# Aqua_D_CTRL.net
KiCad netlist of a schematic drawn in EAGLE
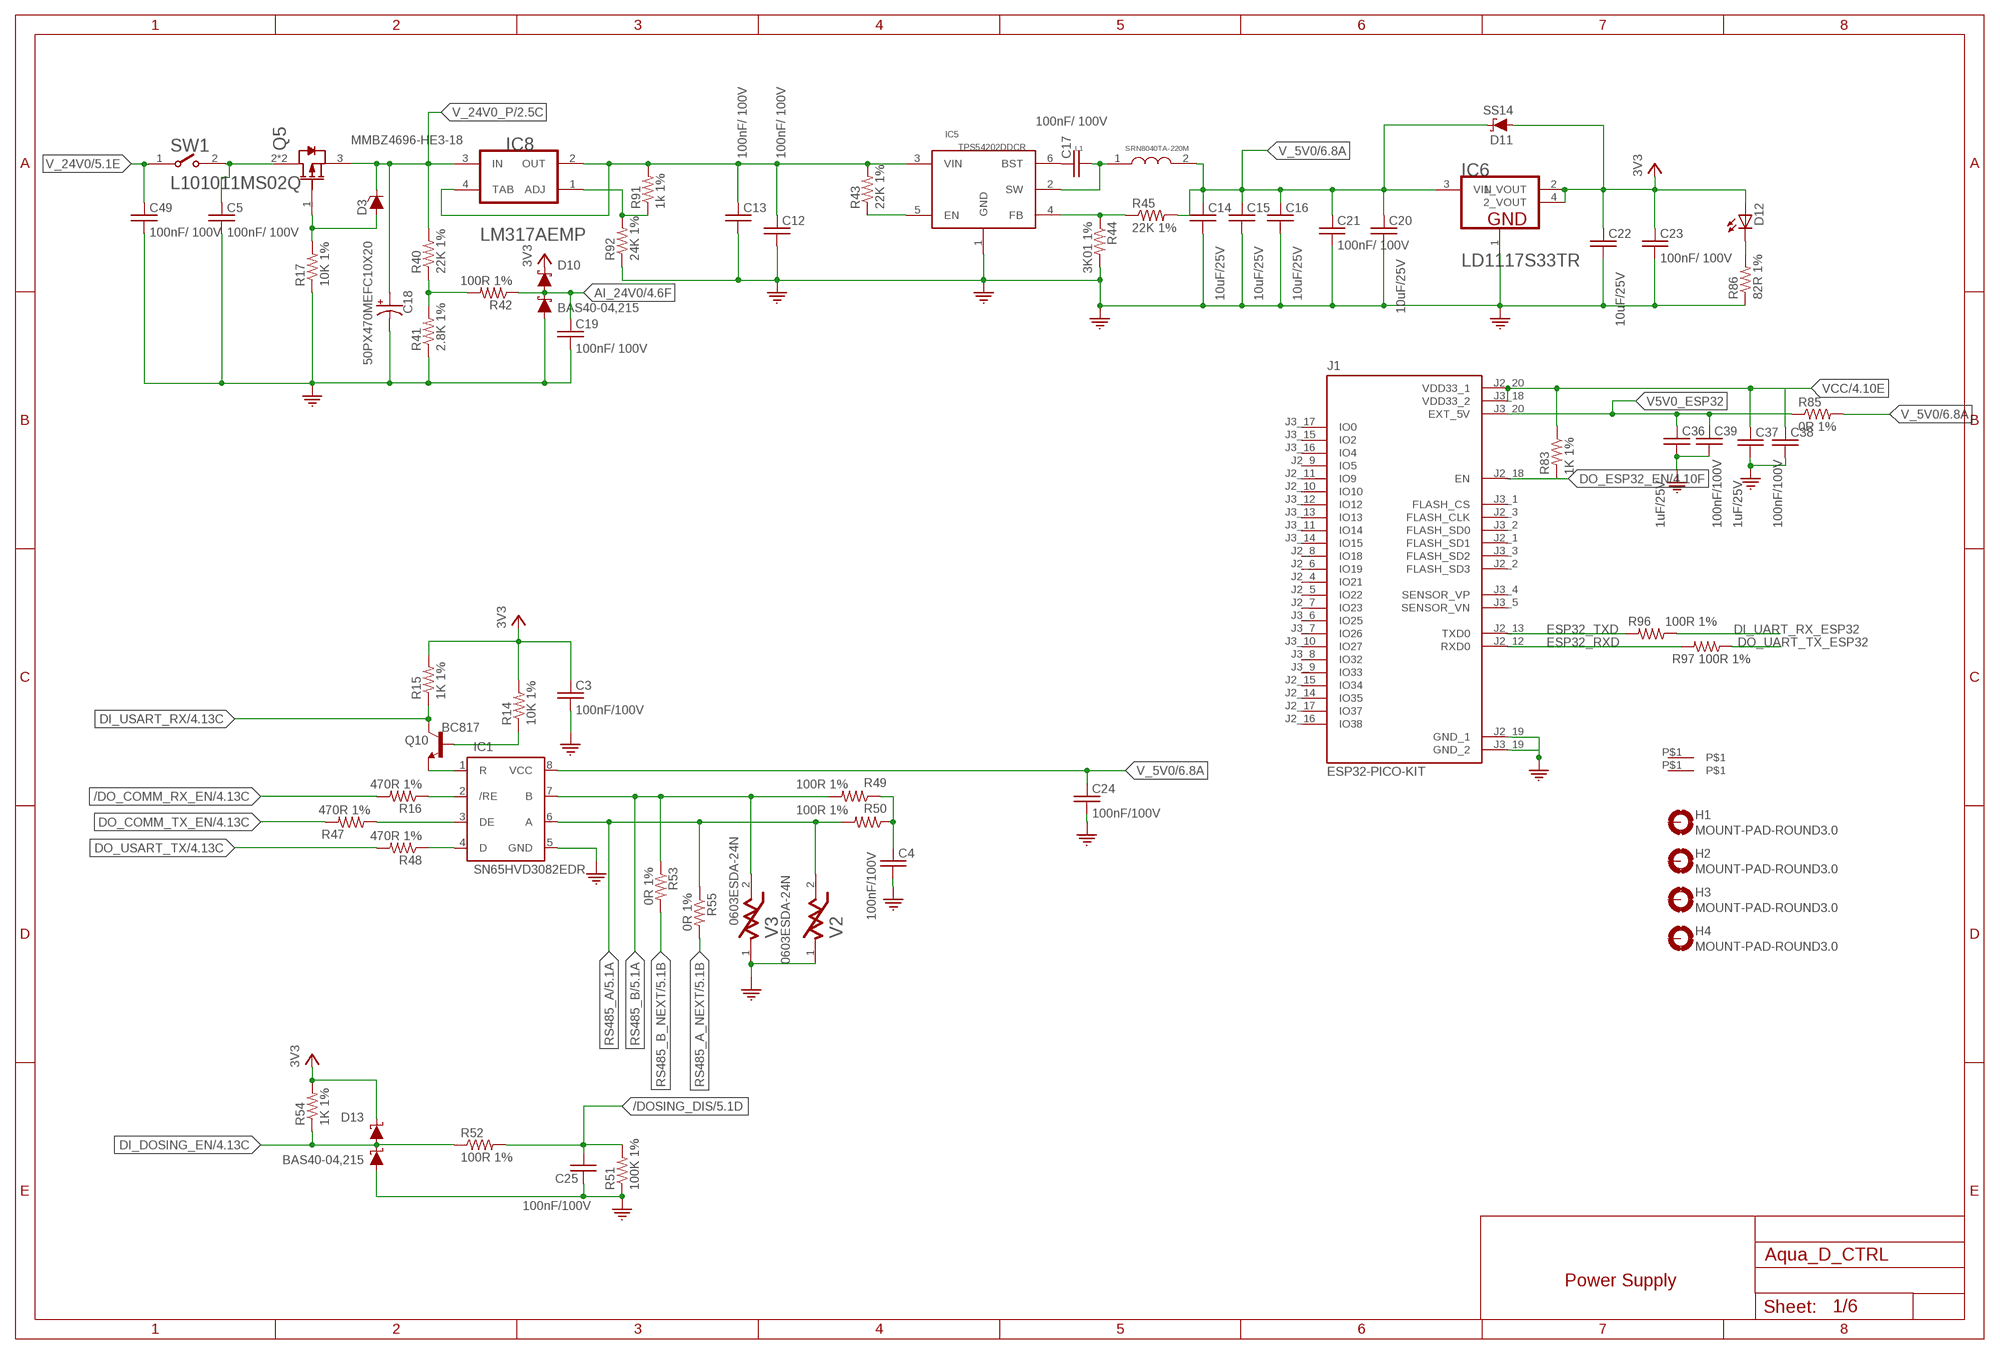
[diagram p0: schematic, sheet 1]
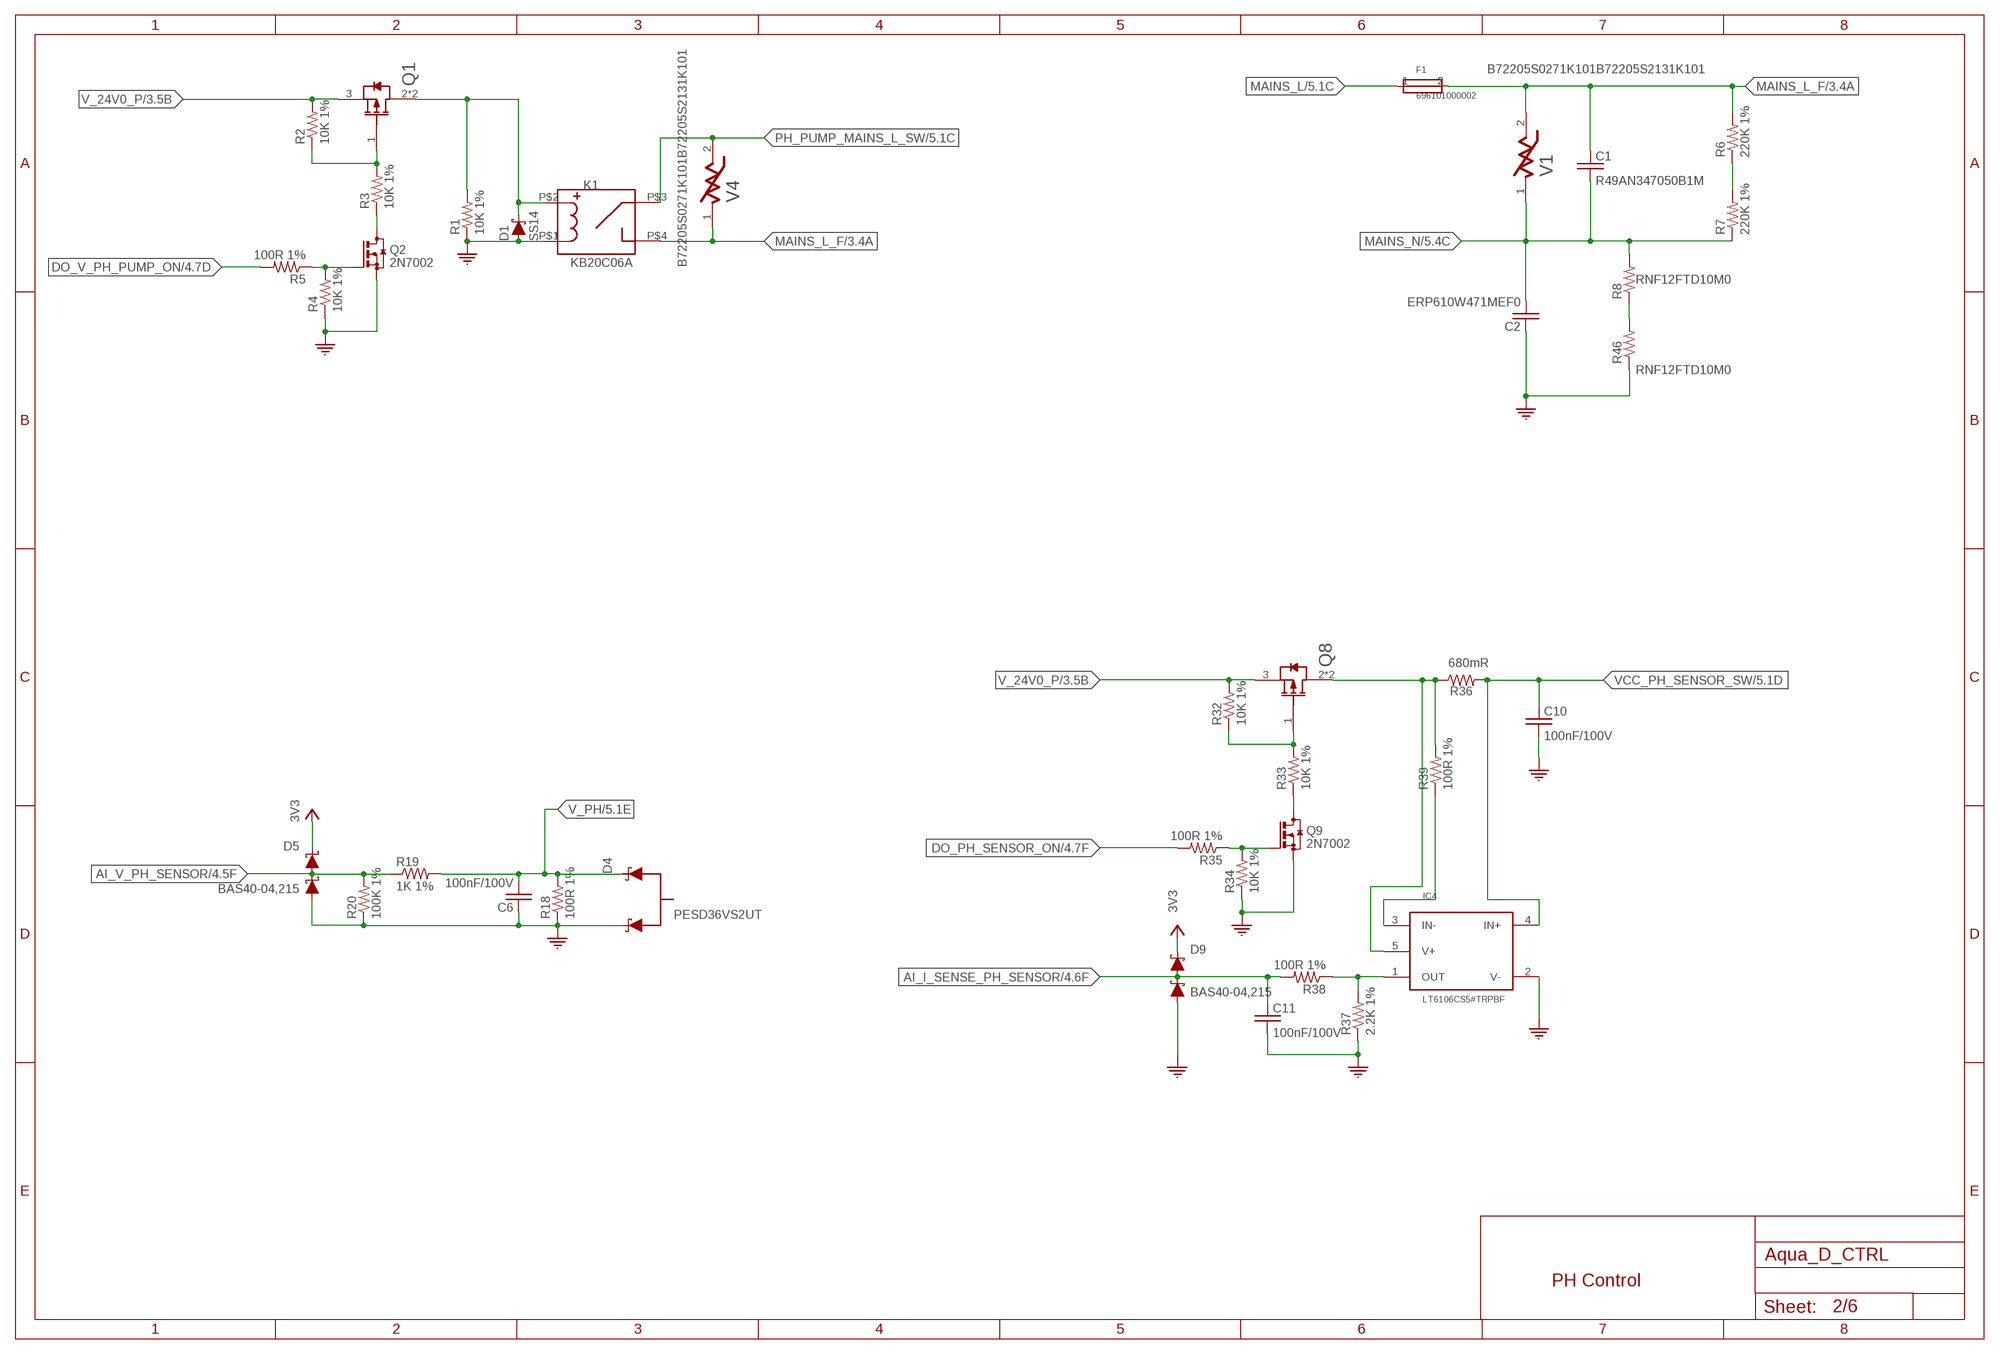
[diagram p1: schematic, sheet 2]
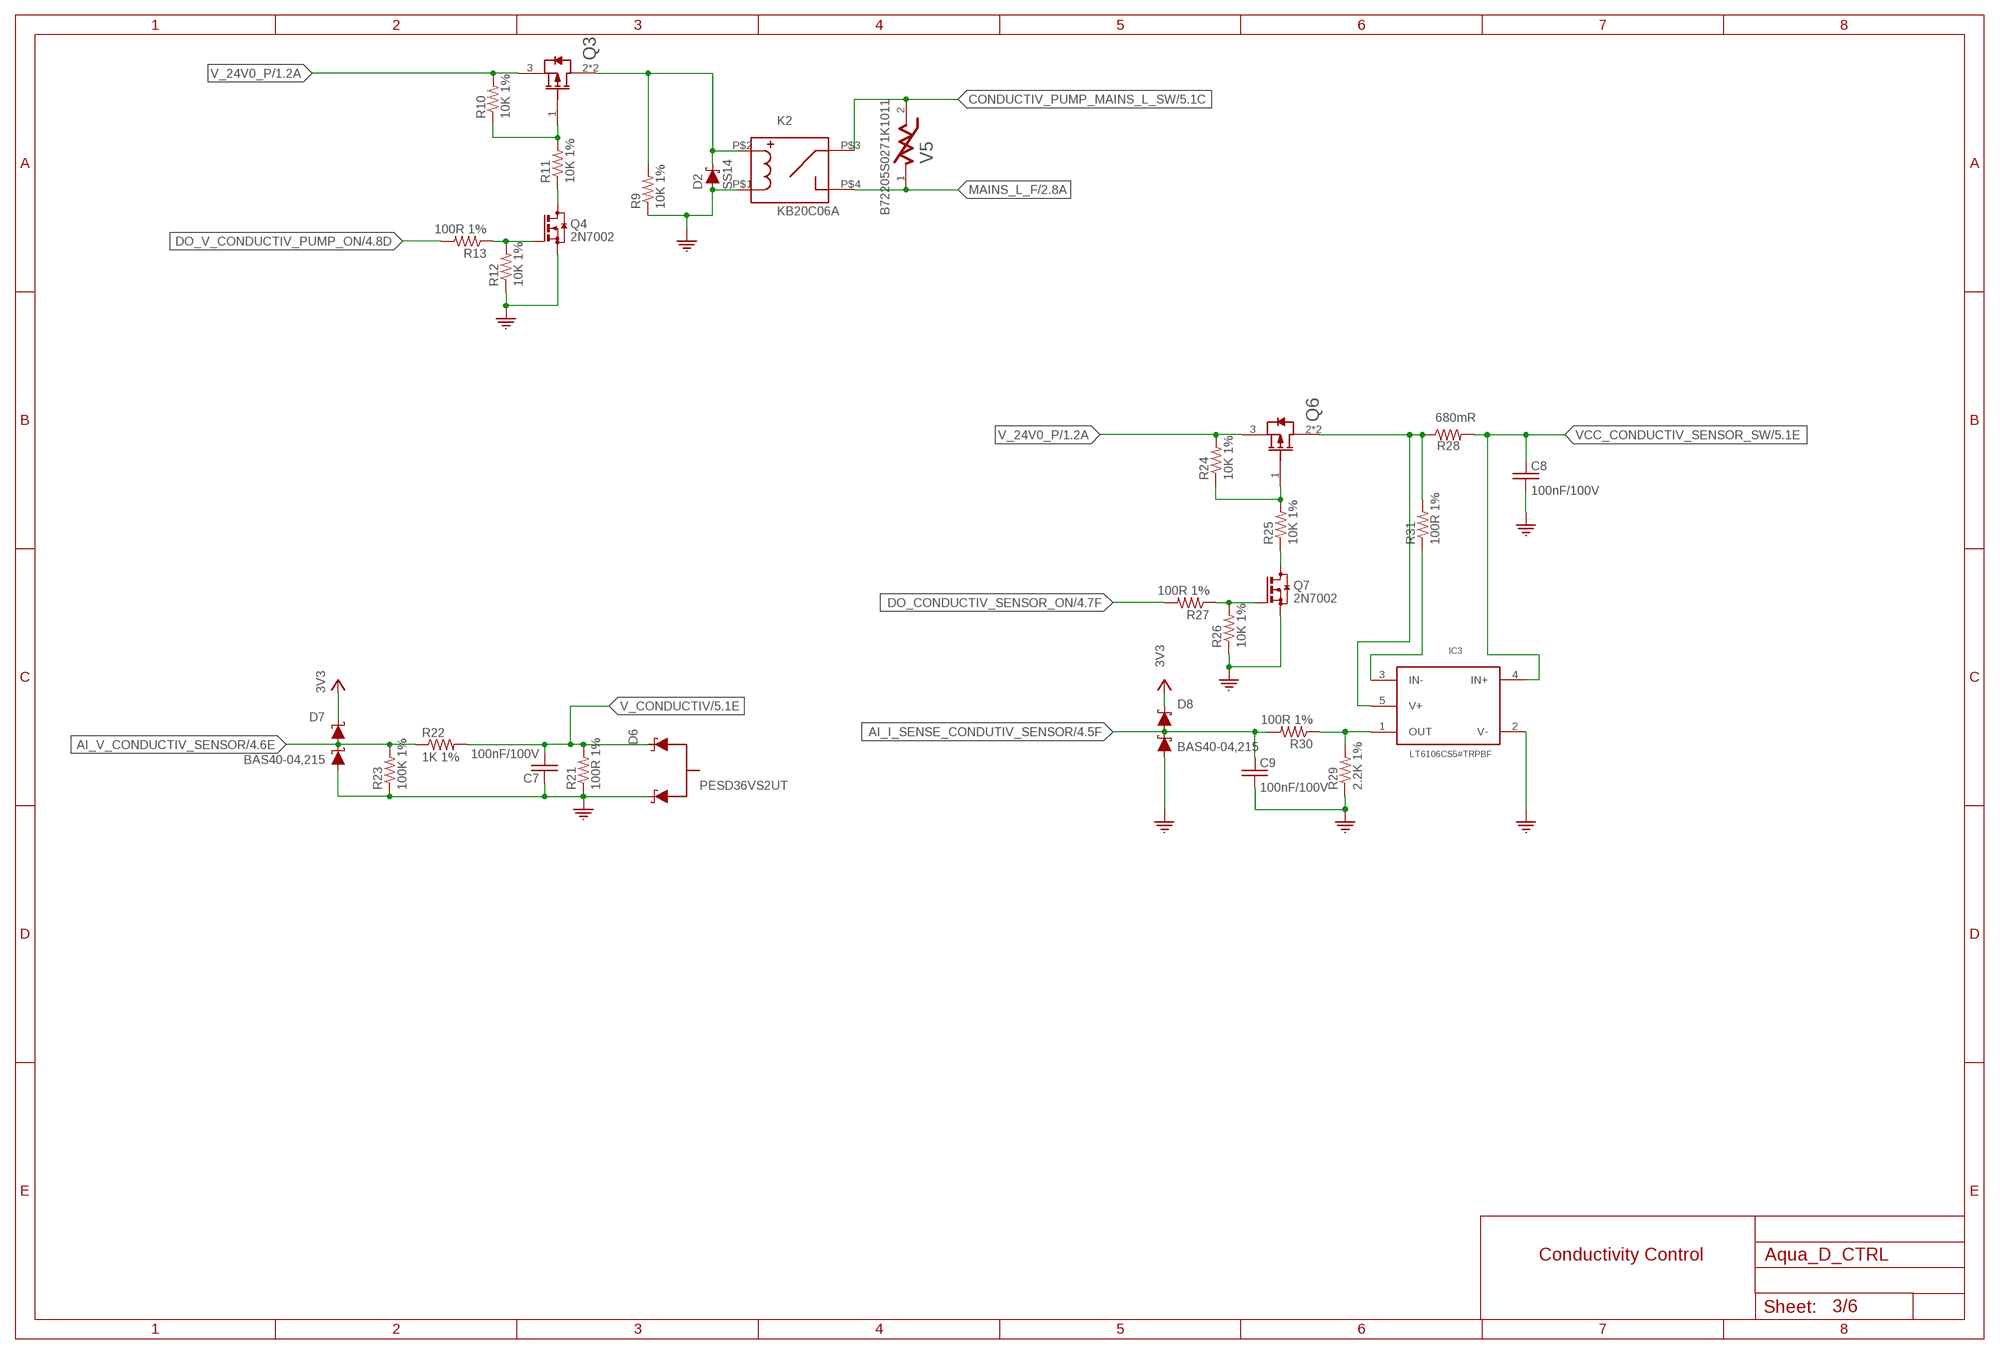
[diagram p2: schematic, sheet 3]
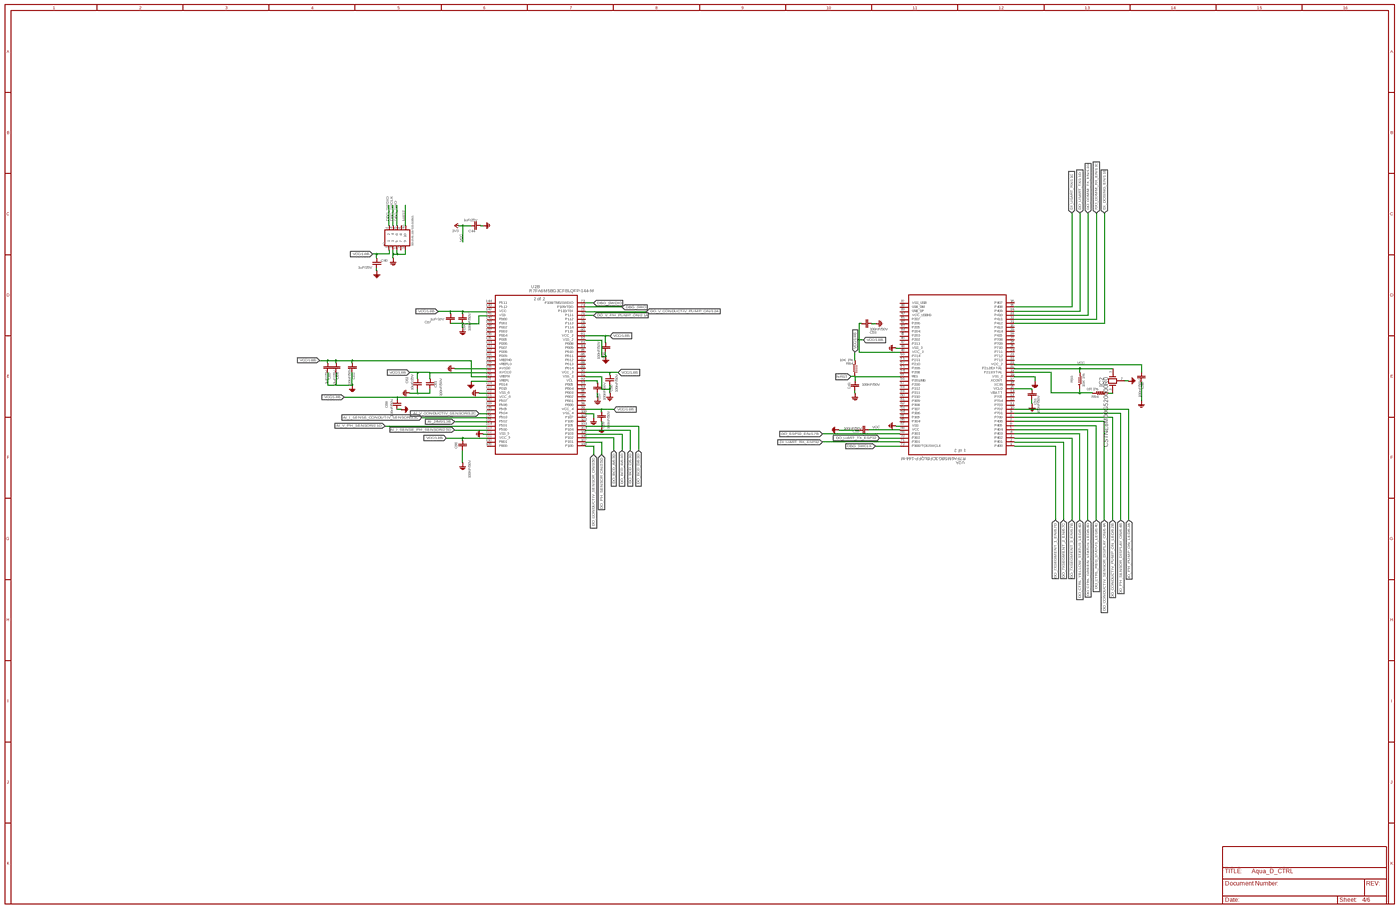
[diagram p3: schematic, sheet 4, overview]
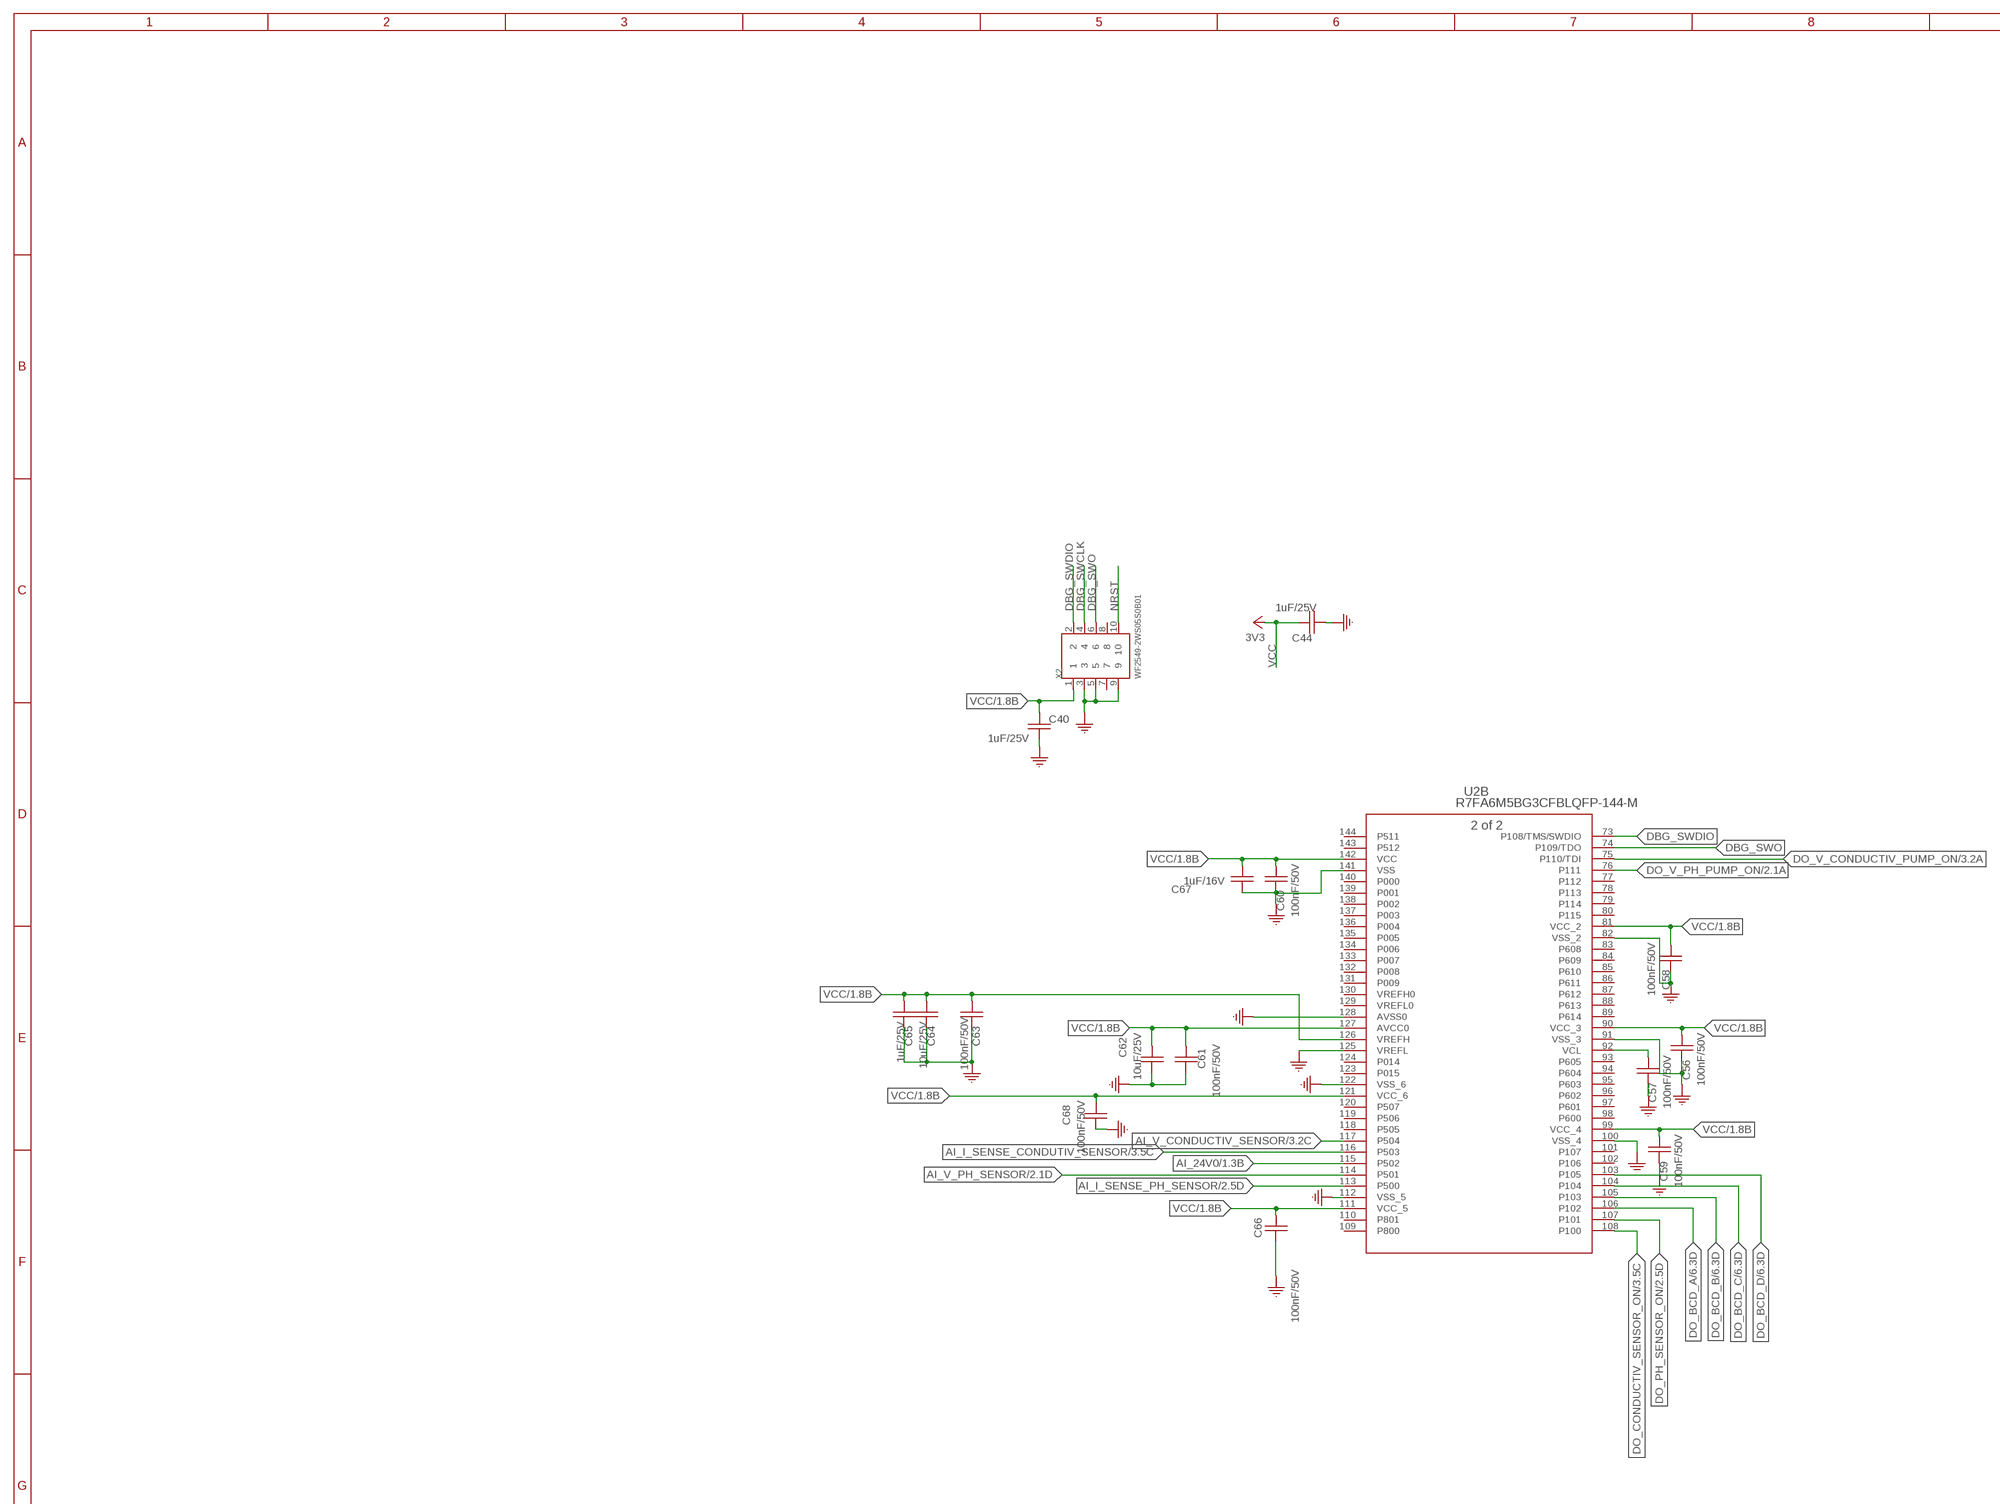
[diagram p4: schematic, sheet 4, part 1 of 4]
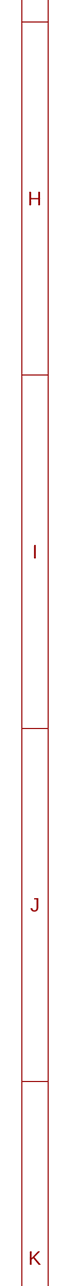
[diagram p5: schematic, sheet 4, part 2 of 4]
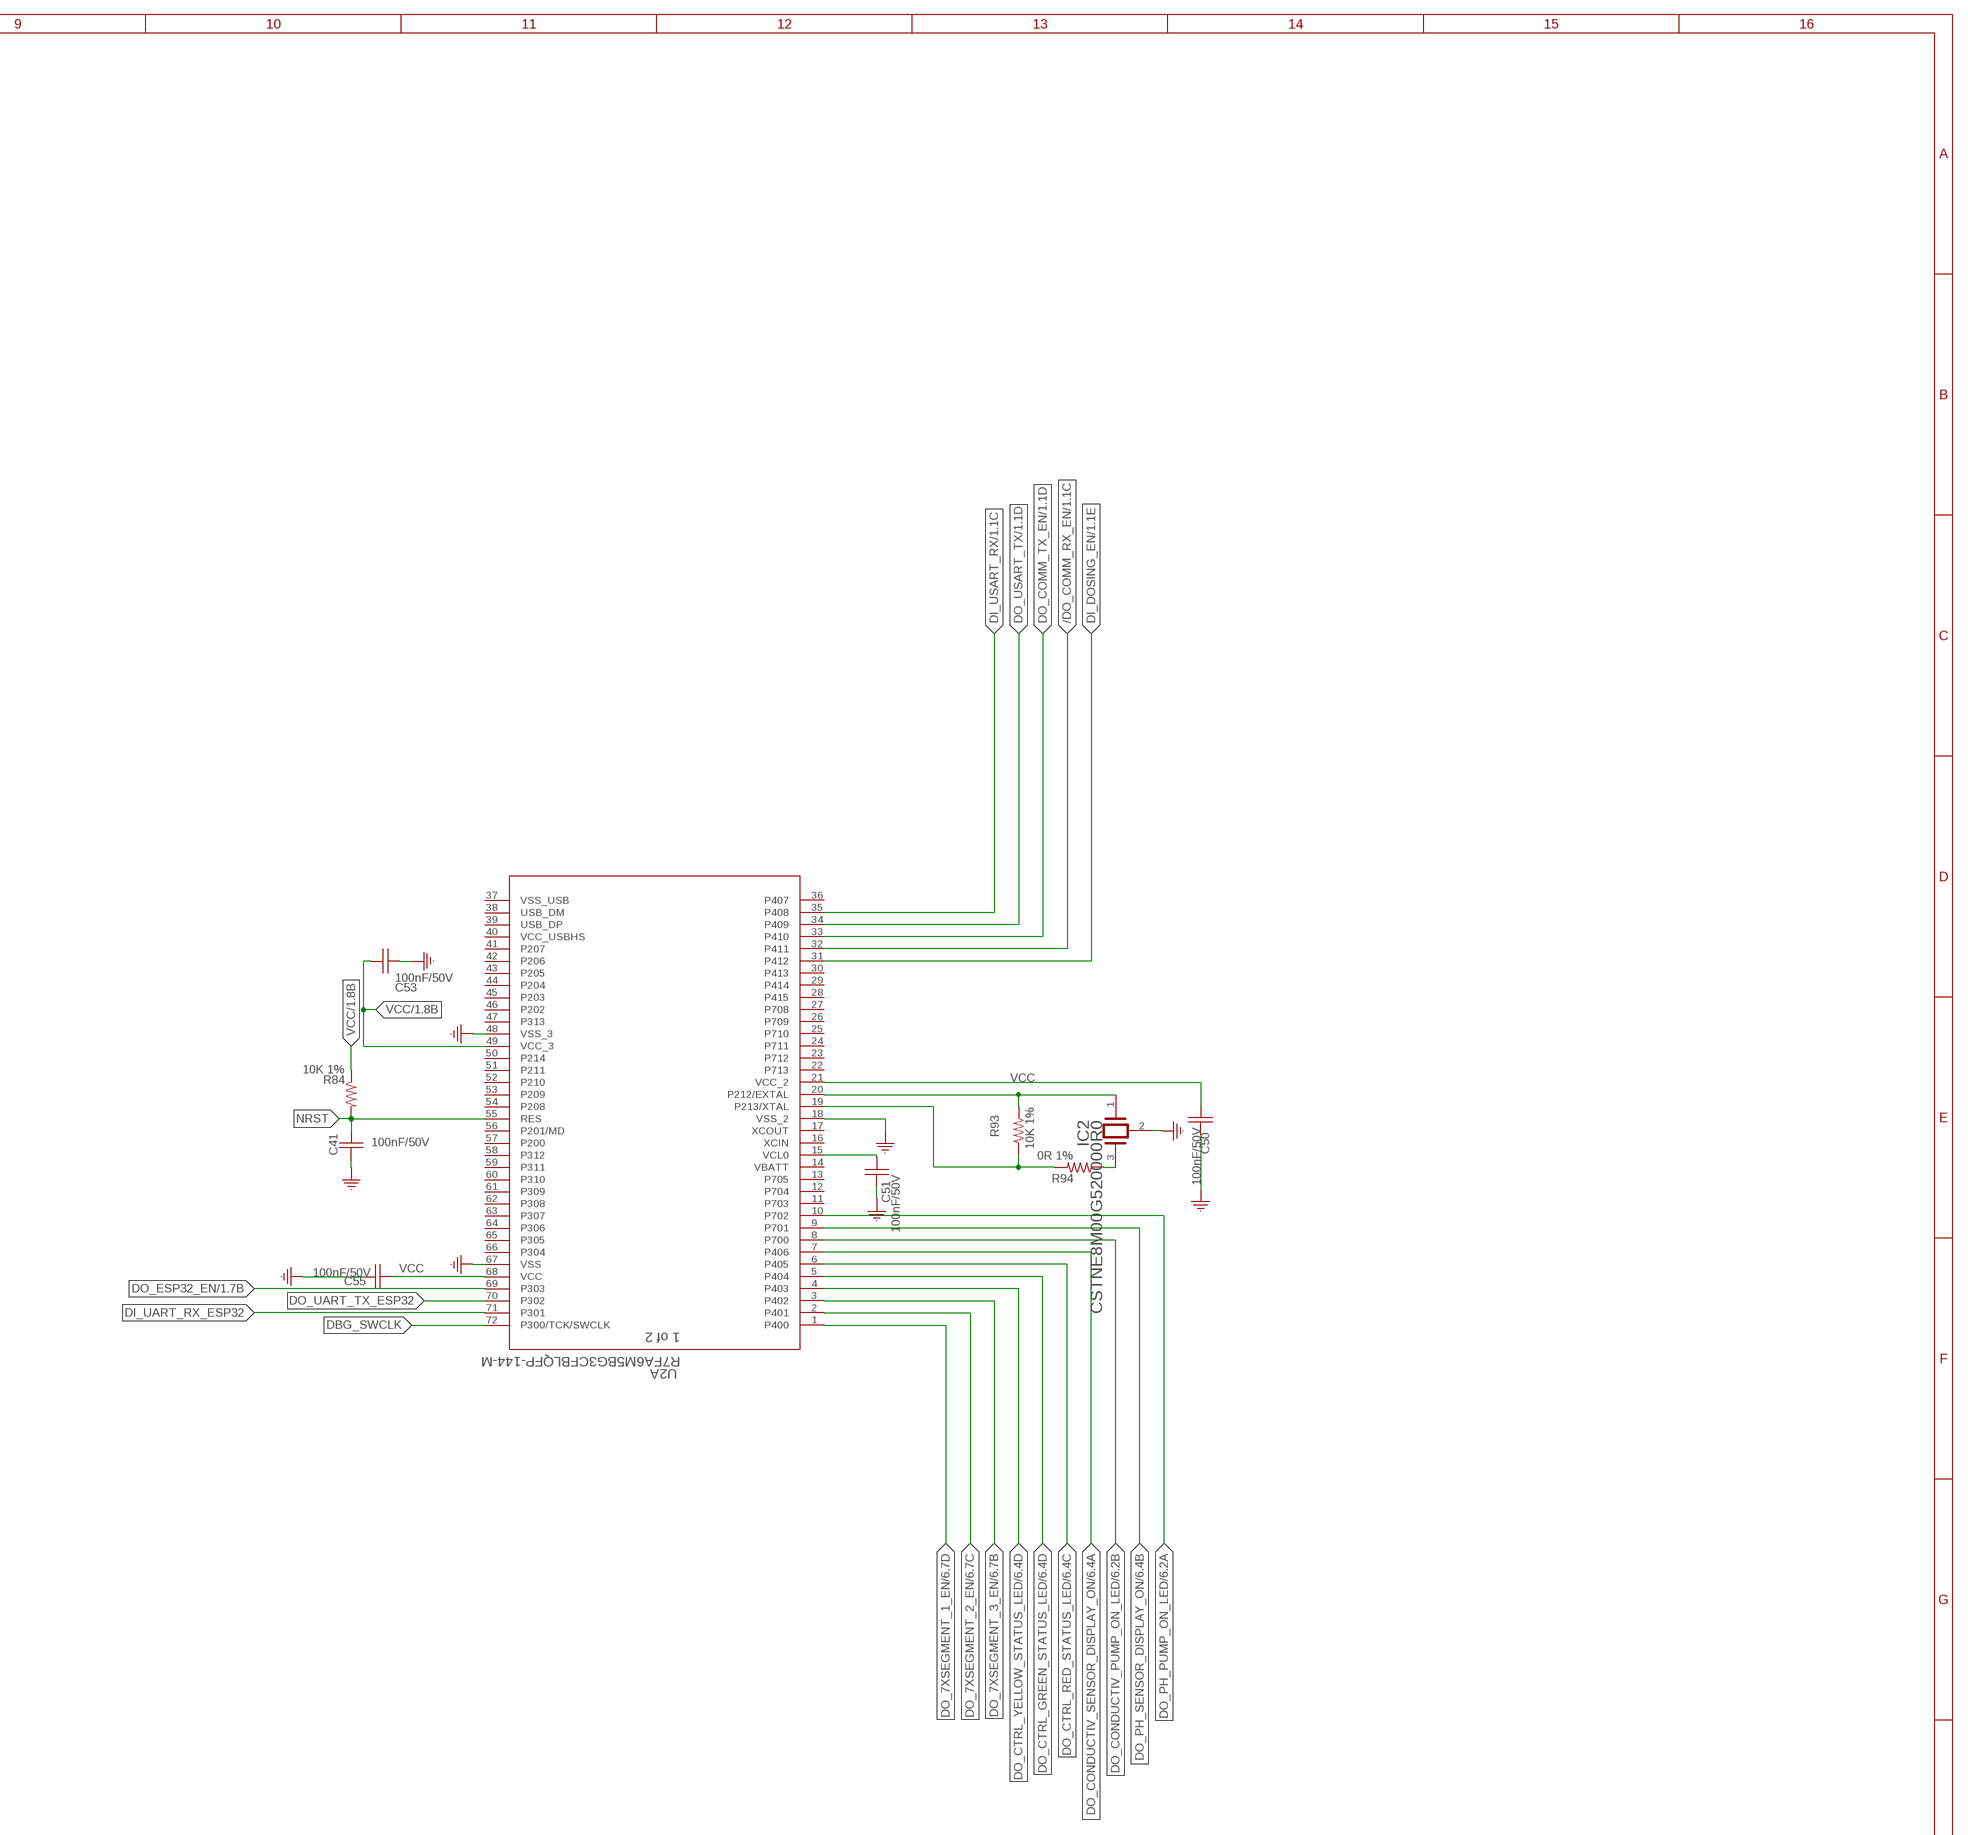
[diagram p6: schematic, sheet 4, part 3 of 4]
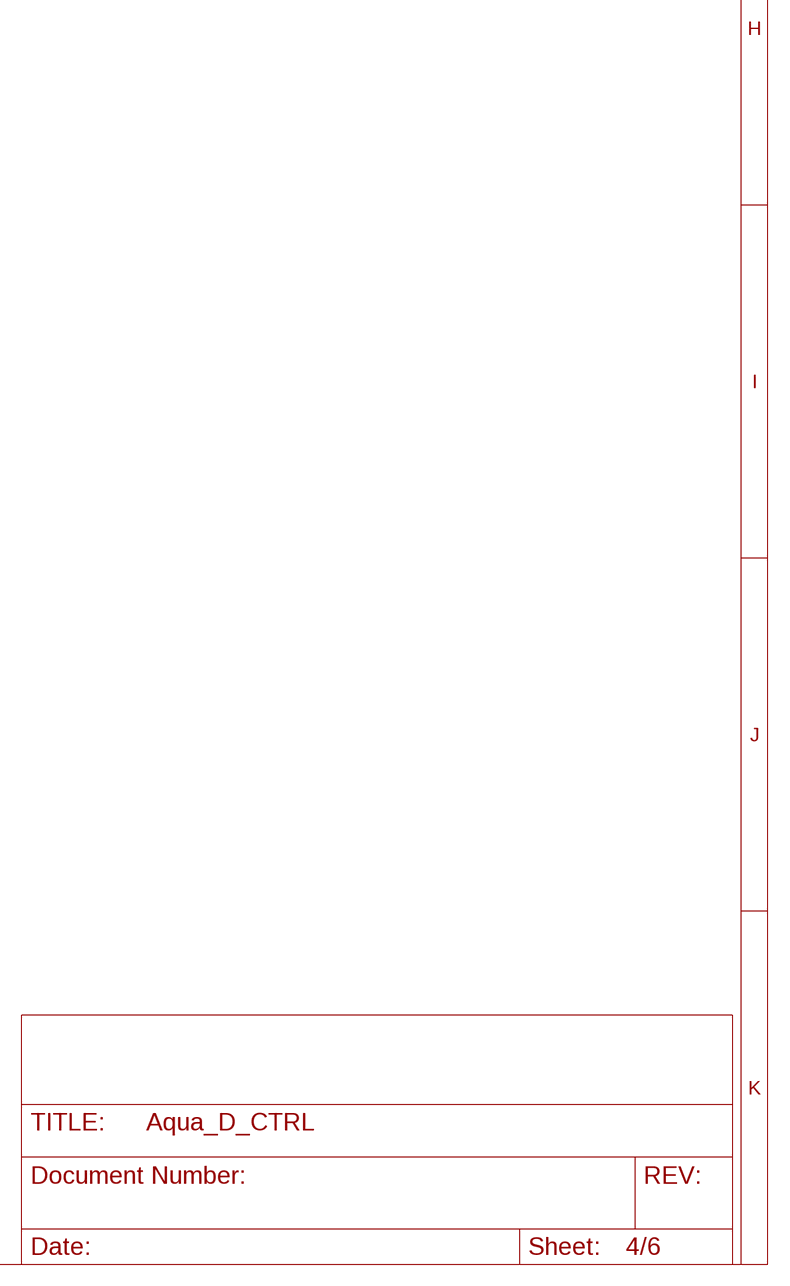
[diagram p7: schematic, sheet 4, part 4 of 4]
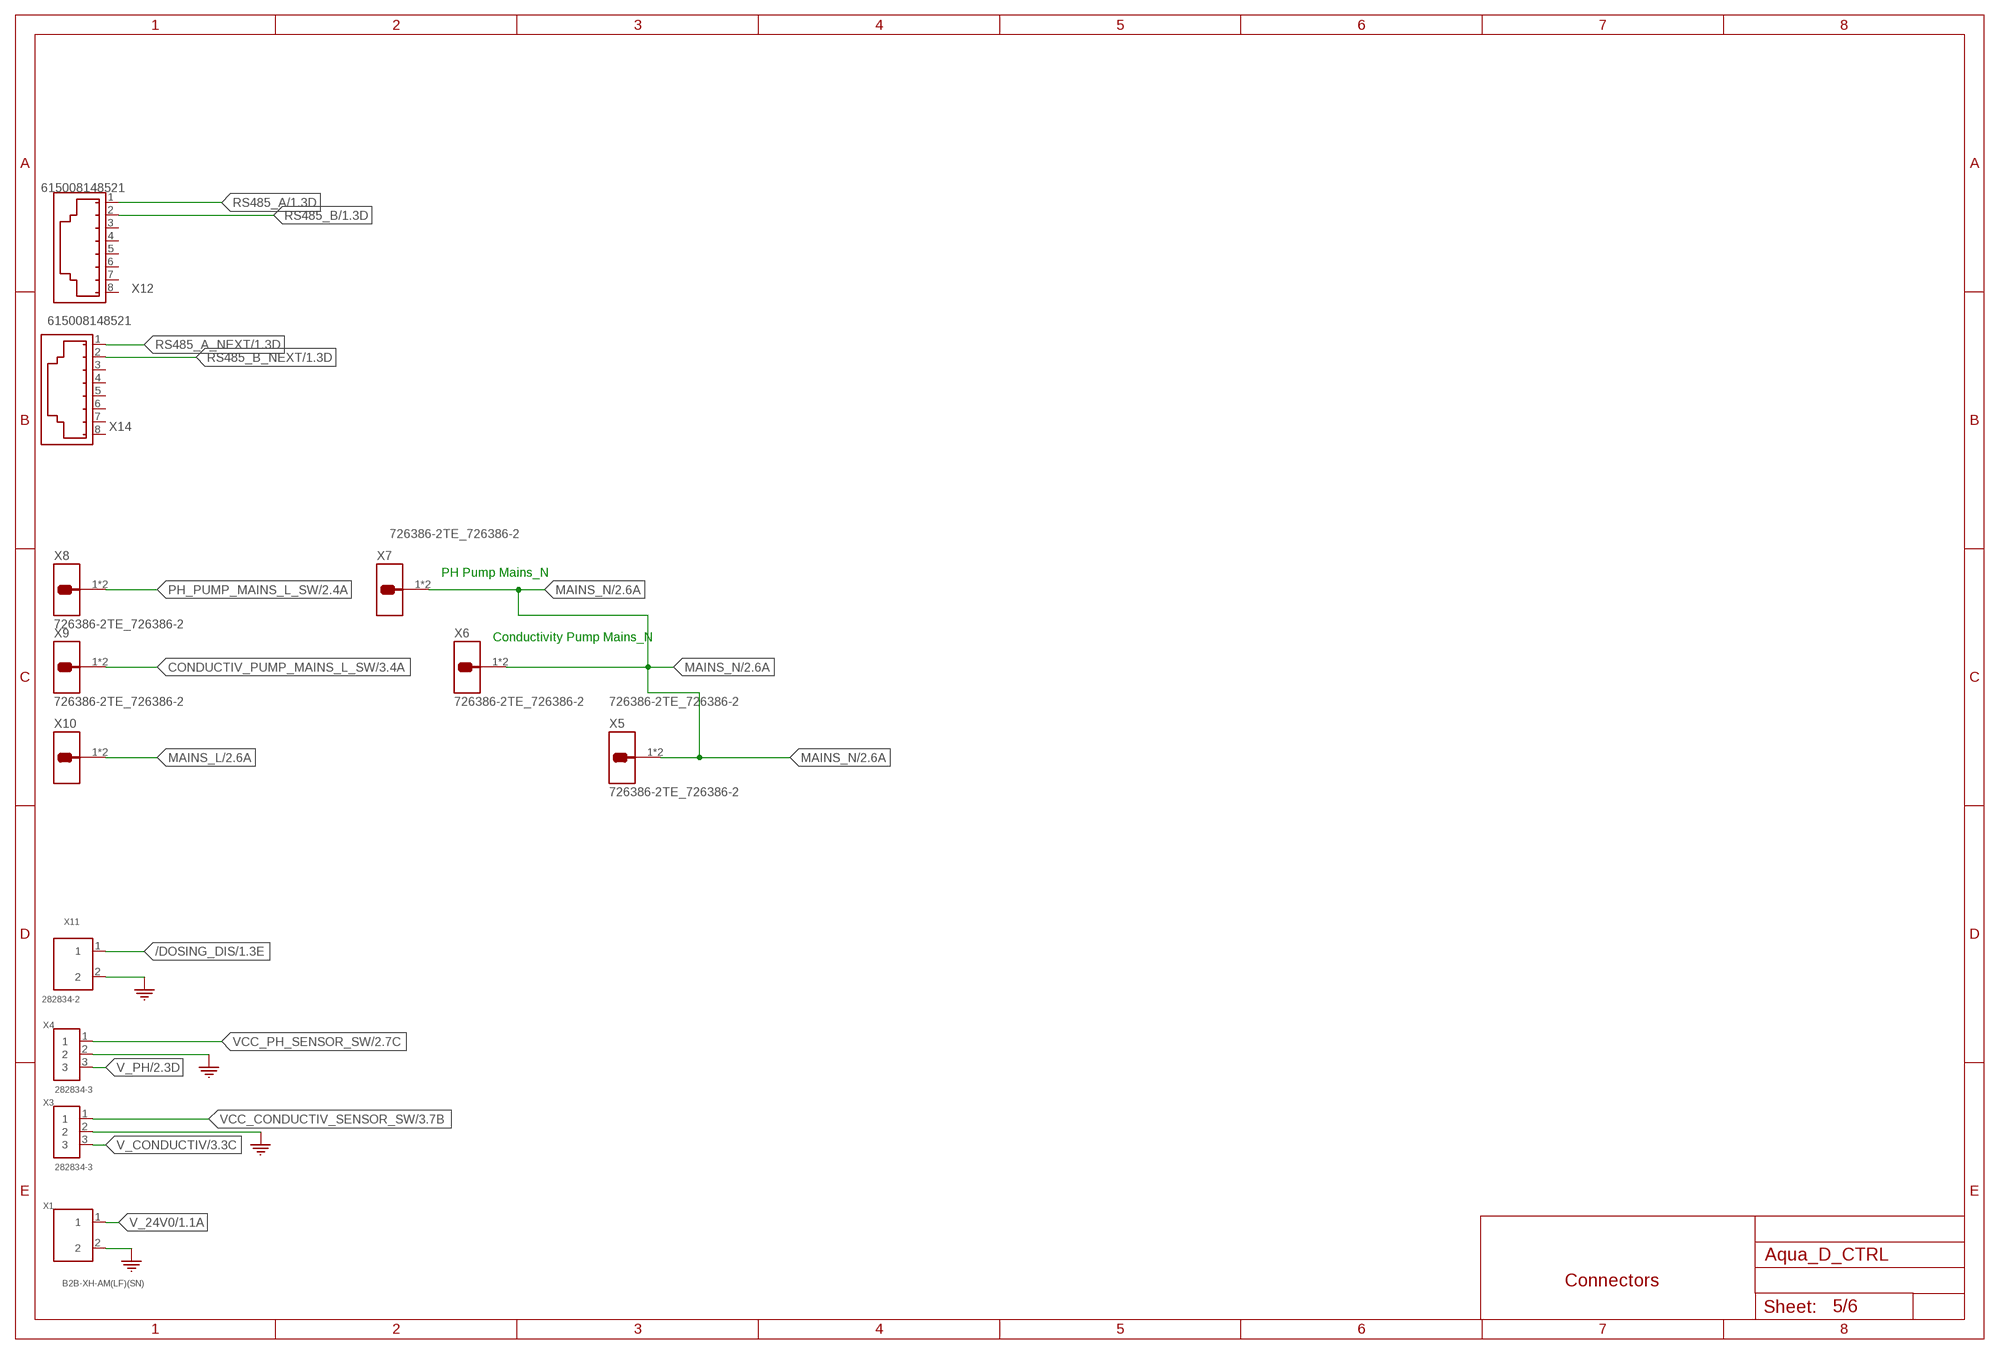
[diagram p8: schematic, sheet 5]
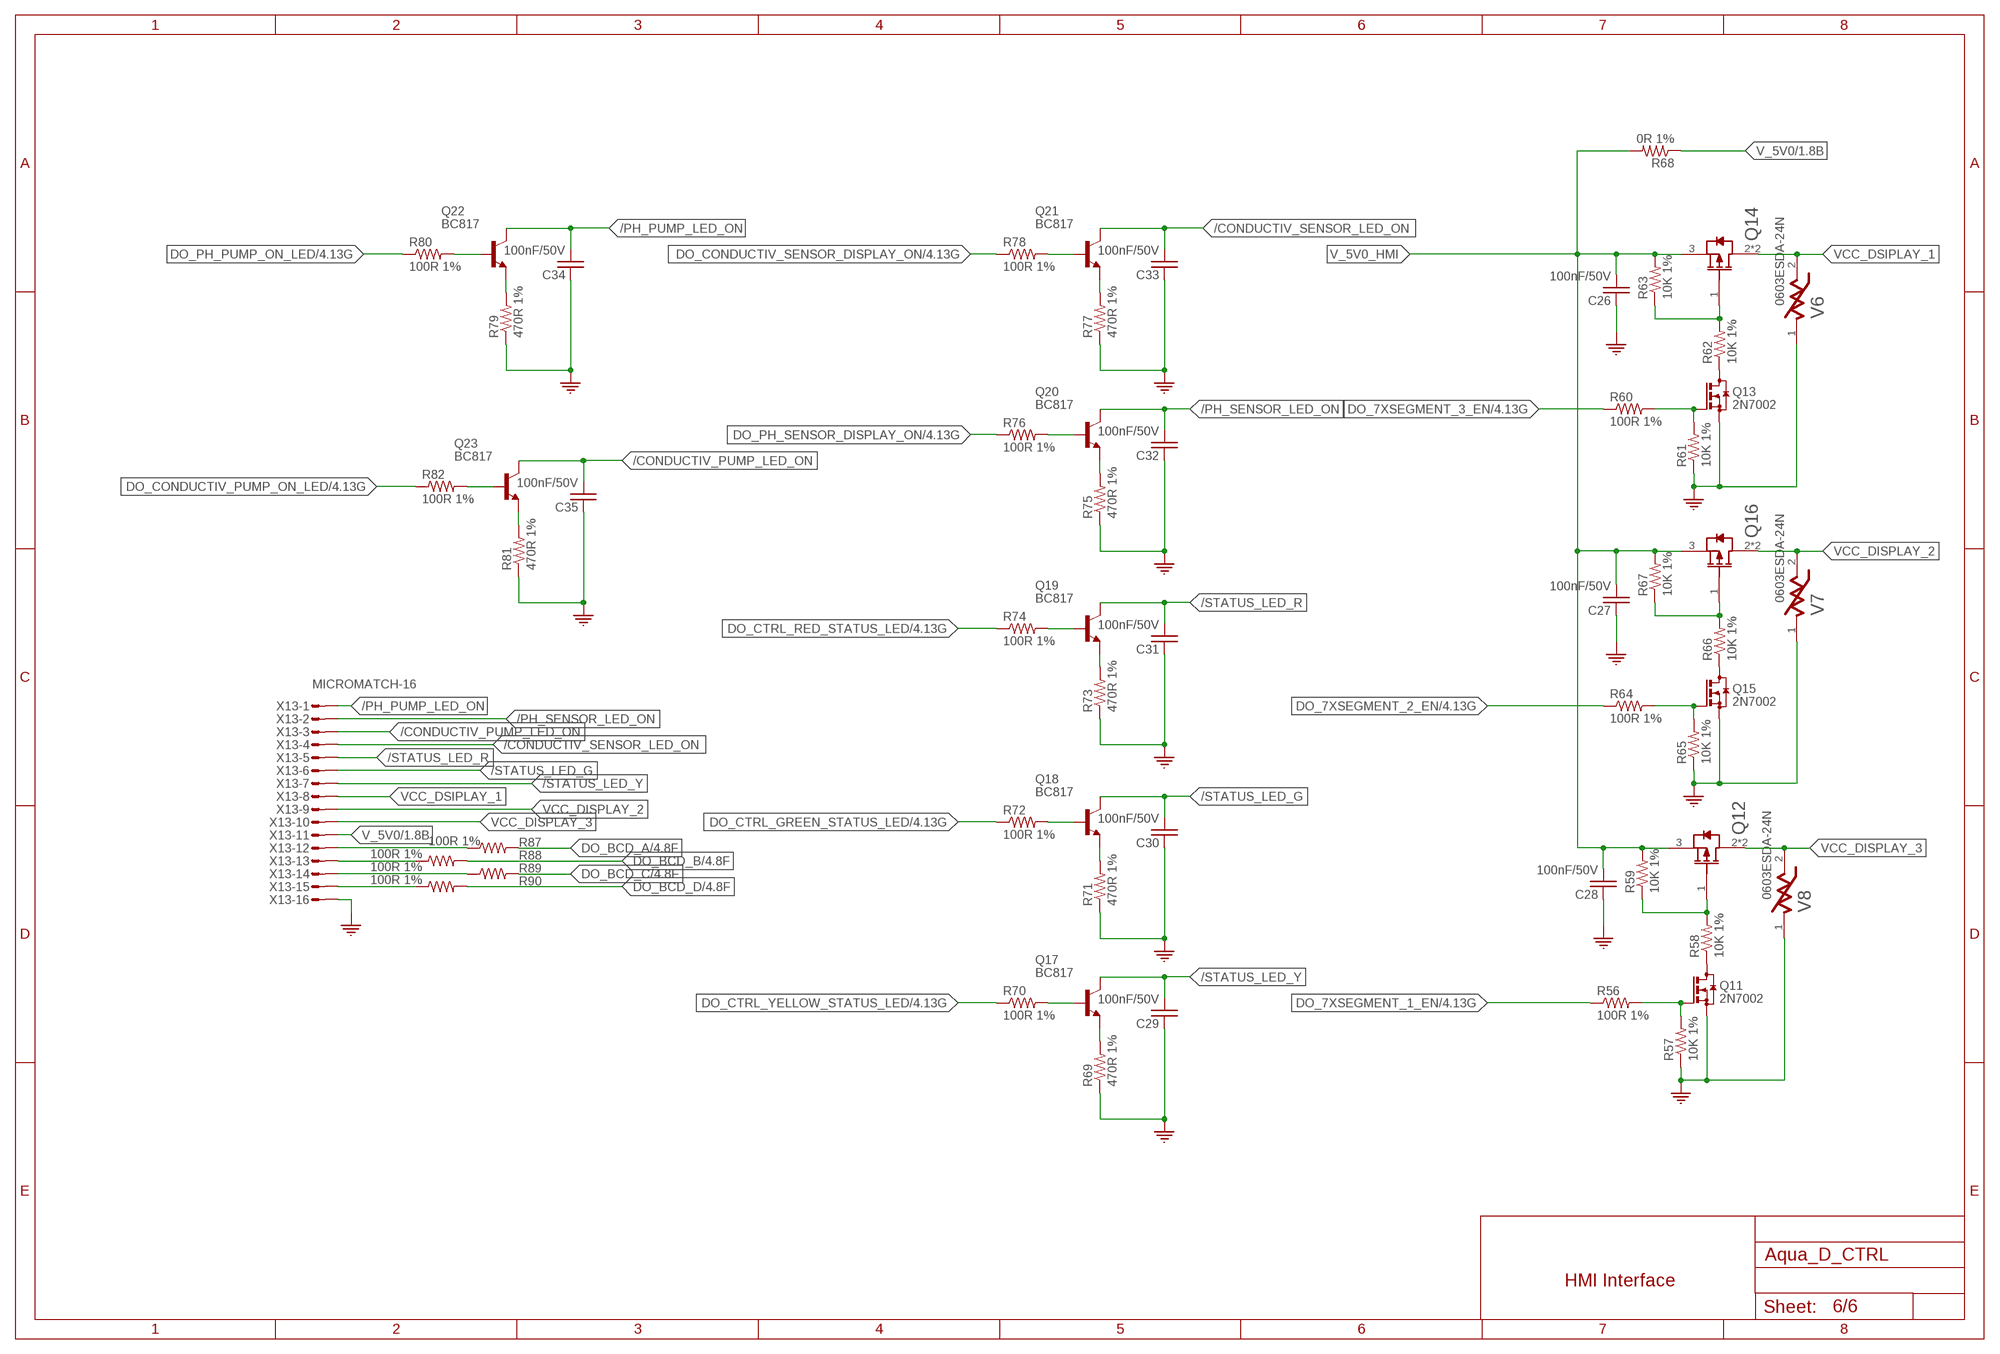
[diagram p9: schematic, sheet 6]

(export (version "E")
  (design (tool "Eeschema 10.0.6"))
  (components
    (comp (ref "C40")
      (value "1uF/25V")
      (footprint "eagle-import:0603")
      (libsource (lib "eagle-import") (part "C_0603"))
    )
    (comp (ref "C41")
      (value "100nF/50V")
      (footprint "eagle-import:0603")
      (libsource (lib "eagle-import") (part "C_0603"))
    )
    (comp (ref "C44")
      (value "1uF/25V")
      (footprint "eagle-import:0603")
      (libsource (lib "eagle-import") (part "C_0603"))
    )
    (comp (ref "C50")
      (value "100nF/50V")
      (footprint "eagle-import:0603")
      (libsource (lib "eagle-import") (part "C_0603"))
    )
    (comp (ref "C51")
      (value "100nF/50V")
      (footprint "eagle-import:0603")
      (libsource (lib "eagle-import") (part "C_0603"))
    )
    (comp (ref "C53")
      (value "100nF/50V")
      (footprint "eagle-import:0603")
      (libsource (lib "eagle-import") (part "C_0603"))
    )
    (comp (ref "C55")
      (value "100nF/50V")
      (footprint "eagle-import:0603")
      (libsource (lib "eagle-import") (part "C_0603"))
    )
    (comp (ref "C56")
      (value "100nF/50V")
      (footprint "eagle-import:0603")
      (libsource (lib "eagle-import") (part "C_0603"))
    )
    (comp (ref "C57")
      (value "100nF/50V")
      (footprint "eagle-import:0603")
      (libsource (lib "eagle-import") (part "C_0603"))
    )
    (comp (ref "C58")
      (value "100nF/50V")
      (footprint "eagle-import:0603")
      (libsource (lib "eagle-import") (part "C_0603"))
    )
    (comp (ref "C59")
      (value "100nF/50V")
      (footprint "eagle-import:0603")
      (libsource (lib "eagle-import") (part "C_0603"))
    )
    (comp (ref "C60")
      (value "100nF/50V")
      (footprint "eagle-import:0603")
      (libsource (lib "eagle-import") (part "C_0603"))
    )
    (comp (ref "C61")
      (value "100nF/50V")
      (footprint "eagle-import:0603")
      (libsource (lib "eagle-import") (part "C_0603"))
    )
    (comp (ref "C62")
      (value "10uF/25V")
      (footprint "eagle-import:0603")
      (libsource (lib "eagle-import") (part "C_0603"))
    )
    (comp (ref "C63")
      (value "100nF/50V")
      (footprint "eagle-import:0603")
      (libsource (lib "eagle-import") (part "C_0603"))
    )
    (comp (ref "C64")
      (value "10uF/25V")
      (footprint "eagle-import:0603")
      (libsource (lib "eagle-import") (part "C_0603"))
    )
    (comp (ref "C65")
      (value "1uF/25V")
      (footprint "eagle-import:0603")
      (libsource (lib "eagle-import") (part "C_0603"))
    )
    (comp (ref "C66")
      (value "100nF/50V")
      (footprint "eagle-import:0603")
      (libsource (lib "eagle-import") (part "C_0603"))
    )
    (comp (ref "C67")
      (value "1uF/16V")
      (footprint "eagle-import:0603")
      (libsource (lib "eagle-import") (part "C_0603"))
    )
    (comp (ref "C68")
      (value "100nF/50V")
      (footprint "eagle-import:0603")
      (libsource (lib "eagle-import") (part "C_0603"))
    )
    (comp (ref "IC2")
      (value "CSTNE8M00G520000R0")
      (footprint "eagle-import:CSTNE8M00G520000R0")
      (fields (field (name "MFR") "Murata"))
      (libsource (lib "eagle-import") (part "CSTNE8M00G520000R0"))
    )
    (comp (ref "R84")
      (value "10K 1%")
      (footprint "eagle-import:R0603")
      (libsource (lib "eagle-import") (part "Labops_Lib_AH_R_0603"))
    )
    (comp (ref "R93")
      (value "10K 1%")
      (footprint "eagle-import:R0603")
      (libsource (lib "eagle-import") (part "Labops_Lib_AH_R_0603"))
    )
    (comp (ref "R94")
      (value "0R 1%")
      (footprint "eagle-import:R0603")
      (libsource (lib "eagle-import") (part "Labops_Lib_AH_R_0603"))
    )
    (comp (ref "U2")
      (value "R7FA6M5BG3CFBLQFP-144-M")
      (footprint "eagle-import:LQFP-144-M")
      (fields (field (name "MFR") "Renesas"))
      (libsource (lib "eagle-import") (part "R7FA6M5BG3CFBLQFP-144-M"))
    )
    (comp (ref "X2")
      (value "WF2549-2WS05S0B01")
      (footprint "eagle-import:X10_100MIL_2XROW_VERT")
      (fields (field (name "MFR") "WCON"))
      (libsource (lib "eagle-import") (part "WF2549-2WS05S0B01"))
    )
    (comp (ref "C7")
      (value "100nF/100V")
      (footprint "eagle-import:0603")
      (libsource (lib "eagle-import") (part "C_0603"))
    )
    (comp (ref "C8")
      (value "100nF/100V")
      (footprint "eagle-import:0603")
      (fields (field (name "PART_VALUE") "100nF/100V"))
      (libsource (lib "eagle-import") (part "C_0603"))
    )
    (comp (ref "C9")
      (value "100nF/100V")
      (footprint "eagle-import:0603")
      (fields (field (name "PART_VALUE") "100nF/100V"))
      (libsource (lib "eagle-import") (part "C_0603"))
    )
    (comp (ref "D2")
      (value "SS14")
      (footprint "eagle-import:SMA")
      (fields (field (name "MFR") "MCC"))
      (libsource (lib "eagle-import") (part "SS14"))
    )
    (comp (ref "D6")
      (value "PESD36VS2UT")
      (footprint "eagle-import:SOT23-3")
      (fields (field (name "MFR") "NXP"))
      (libsource (lib "eagle-import") (part "PESD36VS2UT"))
    )
    (comp (ref "D7")
      (value "BAS40-04,215")
      (footprint "eagle-import:SOT23-3")
      (fields (field (name "MFR") "NXP"))
      (libsource (lib "eagle-import") (part "BAS40-04,215"))
    )
    (comp (ref "D8")
      (value "BAS40-04,215")
      (footprint "eagle-import:SOT23-3")
      (fields (field (name "MFR") "NXP"))
      (libsource (lib "eagle-import") (part "BAS40-04,215"))
    )
    (comp (ref "IC3")
      (value "LT6106CS5#TRPBF")
      (footprint "eagle-import:SOT-23-5")
      (fields (field (name "MFR") "Analog Devices"))
      (libsource (lib "eagle-import") (part "LT6106CS5#TRPBF"))
    )
    (comp (ref "K2")
      (value "KB20C06A")
      (footprint "eagle-import:RELAY_KYOTO_KF0604D")
      (fields (field (name "MFR") "Kyotto"))
      (libsource (lib "eagle-import") (part "KB20C06A"))
    )
    (comp (ref "Q3")
      (value "DMP6185SEQ-13")
      (footprint "eagle-import:SOT223")
      (fields (field (name "MFR") "Diodes"))
      (libsource (lib "eagle-import") (part "DMP6185SEQ-13"))
    )
    (comp (ref "Q4")
      (value "2N7002")
      (footprint "eagle-import:SOT23")
      (fields (field (name "MFR") "Diodes, Guangdong Hotetech,NXP"))
      (libsource (lib "eagle-import") (part "2N7002"))
    )
    (comp (ref "Q6")
      (value "DMP6185SEQ-13")
      (footprint "eagle-import:SOT223")
      (fields (field (name "MFR") "Diodes"))
      (libsource (lib "eagle-import") (part "DMP6185SEQ-13"))
    )
    (comp (ref "Q7")
      (value "2N7002")
      (footprint "eagle-import:SOT23")
      (fields (field (name "MFR") "Diodes, Guangdong Hotetech,NXP"))
      (libsource (lib "eagle-import") (part "2N7002"))
    )
    (comp (ref "R9")
      (value "10K 1%")
      (footprint "eagle-import:0603")
      (libsource (lib "eagle-import") (part "R_0603"))
    )
    (comp (ref "R10")
      (value "10K 1%")
      (footprint "eagle-import:0603")
      (libsource (lib "eagle-import") (part "R_0603"))
    )
    (comp (ref "R11")
      (value "10K 1%")
      (footprint "eagle-import:0603")
      (libsource (lib "eagle-import") (part "R_0603"))
    )
    (comp (ref "R12")
      (value "10K 1%")
      (footprint "eagle-import:0603")
      (libsource (lib "eagle-import") (part "R_0603"))
    )
    (comp (ref "R13")
      (value "100R 1%")
      (footprint "eagle-import:0603")
      (libsource (lib "eagle-import") (part "R_0603"))
    )
    (comp (ref "R21")
      (value "100R 1%")
      (footprint "eagle-import:R1206")
      (libsource (lib "eagle-import") (part "R_1206"))
    )
    (comp (ref "R22")
      (value "1K 1%")
      (footprint "eagle-import:R0603")
      (libsource (lib "eagle-import") (part "Labops_Lib_AH_R_0603"))
    )
    (comp (ref "R23")
      (value "100K 1%")
      (footprint "eagle-import:R0603")
      (libsource (lib "eagle-import") (part "Labops_Lib_AH_R_0603"))
    )
    (comp (ref "R24")
      (value "10K 1%")
      (footprint "eagle-import:0603")
      (libsource (lib "eagle-import") (part "R_0603"))
    )
    (comp (ref "R25")
      (value "10K 1%")
      (footprint "eagle-import:0603")
      (libsource (lib "eagle-import") (part "R_0603"))
    )
    (comp (ref "R26")
      (value "10K 1%")
      (footprint "eagle-import:0603")
      (libsource (lib "eagle-import") (part "R_0603"))
    )
    (comp (ref "R27")
      (value "100R 1%")
      (footprint "eagle-import:0603")
      (libsource (lib "eagle-import") (part "R_0603"))
    )
    (comp (ref "R28")
      (value "R_2010")
      (footprint "eagle-import:R2010")
      (fields (field (name "MFN") "RL73K2HR68JTE") (field (name "PART_VALUE") "680mR"))
      (libsource (lib "eagle-import") (part "R_2010"))
    )
    (comp (ref "R29")
      (value "2.2K 1%")
      (footprint "eagle-import:0603")
      (libsource (lib "eagle-import") (part "R_0603"))
    )
    (comp (ref "R30")
      (value "100R 1%")
      (footprint "eagle-import:0603")
      (libsource (lib "eagle-import") (part "R_0603"))
    )
    (comp (ref "R31")
      (value "100R 1%")
      (footprint "eagle-import:0603")
      (libsource (lib "eagle-import") (part "R_0603"))
    )
    (comp (ref "V5")
      (value "B72205S0271K1011")
      (footprint "eagle-import:EPCOS_B72205S0271K101_MODIFIED")
      (libsource (lib "eagle-import") (part "B72205S0271K1011"))
    )
    (comp (ref "C26")
      (value "100nF/50V")
      (footprint "eagle-import:0603")
      (libsource (lib "eagle-import") (part "C_0603"))
    )
    (comp (ref "C27")
      (value "100nF/50V")
      (footprint "eagle-import:0603")
      (libsource (lib "eagle-import") (part "C_0603"))
    )
    (comp (ref "C28")
      (value "100nF/50V")
      (footprint "eagle-import:0603")
      (libsource (lib "eagle-import") (part "C_0603"))
    )
    (comp (ref "C29")
      (value "100nF/50V")
      (footprint "eagle-import:0603")
      (libsource (lib "eagle-import") (part "C_0603"))
    )
    (comp (ref "C30")
      (value "100nF/50V")
      (footprint "eagle-import:0603")
      (libsource (lib "eagle-import") (part "C_0603"))
    )
    (comp (ref "C31")
      (value "100nF/50V")
      (footprint "eagle-import:0603")
      (libsource (lib "eagle-import") (part "C_0603"))
    )
    (comp (ref "C32")
      (value "100nF/50V")
      (footprint "eagle-import:0603")
      (libsource (lib "eagle-import") (part "C_0603"))
    )
    (comp (ref "C33")
      (value "100nF/50V")
      (footprint "eagle-import:0603")
      (libsource (lib "eagle-import") (part "C_0603"))
    )
    (comp (ref "C34")
      (value "100nF/50V")
      (footprint "eagle-import:0603")
      (libsource (lib "eagle-import") (part "C_0603"))
    )
    (comp (ref "C35")
      (value "100nF/50V")
      (footprint "eagle-import:0603")
      (libsource (lib "eagle-import") (part "C_0603"))
    )
    (comp (ref "Q11")
      (value "2N7002")
      (footprint "eagle-import:SOT23")
      (fields (field (name "MFR") "Diodes, Guangdong Hotetech,NXP"))
      (libsource (lib "eagle-import") (part "2N7002"))
    )
    (comp (ref "Q12")
      (value "DMP6185SEQ-13")
      (footprint "eagle-import:SOT223")
      (fields (field (name "MFR") "Diodes"))
      (libsource (lib "eagle-import") (part "DMP6185SEQ-13"))
    )
    (comp (ref "Q13")
      (value "2N7002")
      (footprint "eagle-import:SOT23")
      (fields (field (name "MFR") "Diodes, Guangdong Hotetech,NXP"))
      (libsource (lib "eagle-import") (part "2N7002"))
    )
    (comp (ref "Q14")
      (value "DMP6185SEQ-13")
      (footprint "eagle-import:SOT223")
      (fields (field (name "MFR") "Diodes"))
      (libsource (lib "eagle-import") (part "DMP6185SEQ-13"))
    )
    (comp (ref "Q15")
      (value "2N7002")
      (footprint "eagle-import:SOT23")
      (fields (field (name "MFR") "Diodes, Guangdong Hotetech,NXP"))
      (libsource (lib "eagle-import") (part "2N7002"))
    )
    (comp (ref "Q16")
      (value "DMP6185SEQ-13")
      (footprint "eagle-import:SOT223")
      (fields (field (name "MFR") "Diodes"))
      (libsource (lib "eagle-import") (part "DMP6185SEQ-13"))
    )
    (comp (ref "Q17")
      (value "BC817")
      (footprint "eagle-import:SOT23")
      (fields (field (name "MFR") "NXP"))
      (libsource (lib "eagle-import") (part "BC817"))
    )
    (comp (ref "Q18")
      (value "BC817")
      (footprint "eagle-import:SOT23")
      (fields (field (name "MFR") "NXP"))
      (libsource (lib "eagle-import") (part "BC817"))
    )
    (comp (ref "Q19")
      (value "BC817")
      (footprint "eagle-import:SOT23")
      (fields (field (name "MFR") "NXP"))
      (libsource (lib "eagle-import") (part "BC817"))
    )
    (comp (ref "Q20")
      (value "BC817")
      (footprint "eagle-import:SOT23")
      (fields (field (name "MFR") "NXP"))
      (libsource (lib "eagle-import") (part "BC817"))
    )
    (comp (ref "Q21")
      (value "BC817")
      (footprint "eagle-import:SOT23")
      (fields (field (name "MFR") "NXP"))
      (libsource (lib "eagle-import") (part "BC817"))
    )
    (comp (ref "Q22")
      (value "BC817")
      (footprint "eagle-import:SOT23")
      (fields (field (name "MFR") "NXP"))
      (libsource (lib "eagle-import") (part "BC817"))
    )
    (comp (ref "Q23")
      (value "BC817")
      (footprint "eagle-import:SOT23")
      (fields (field (name "MFR") "NXP"))
      (libsource (lib "eagle-import") (part "BC817"))
    )
    (comp (ref "R56")
      (value "100R 1%")
      (footprint "eagle-import:R0603")
      (libsource (lib "eagle-import") (part "Labops_Lib_AH_R_0603"))
    )
    (comp (ref "R57")
      (value "10K 1%")
      (footprint "eagle-import:R0603")
      (libsource (lib "eagle-import") (part "Labops_Lib_AH_R_0603"))
    )
    (comp (ref "R58")
      (value "10K 1%")
      (footprint "eagle-import:R0603")
      (libsource (lib "eagle-import") (part "Labops_Lib_AH_R_0603"))
    )
    (comp (ref "R59")
      (value "10K 1%")
      (footprint "eagle-import:R0603")
      (libsource (lib "eagle-import") (part "Labops_Lib_AH_R_0603"))
    )
    (comp (ref "R60")
      (value "100R 1%")
      (footprint "eagle-import:R0603")
      (libsource (lib "eagle-import") (part "Labops_Lib_AH_R_0603"))
    )
    (comp (ref "R61")
      (value "10K 1%")
      (footprint "eagle-import:R0603")
      (libsource (lib "eagle-import") (part "Labops_Lib_AH_R_0603"))
    )
    (comp (ref "R62")
      (value "10K 1%")
      (footprint "eagle-import:R0603")
      (libsource (lib "eagle-import") (part "Labops_Lib_AH_R_0603"))
    )
    (comp (ref "R63")
      (value "10K 1%")
      (footprint "eagle-import:R0603")
      (libsource (lib "eagle-import") (part "Labops_Lib_AH_R_0603"))
    )
    (comp (ref "R64")
      (value "100R 1%")
      (footprint "eagle-import:R0603")
      (libsource (lib "eagle-import") (part "Labops_Lib_AH_R_0603"))
    )
    (comp (ref "R65")
      (value "10K 1%")
      (footprint "eagle-import:R0603")
      (libsource (lib "eagle-import") (part "Labops_Lib_AH_R_0603"))
    )
    (comp (ref "R66")
      (value "10K 1%")
      (footprint "eagle-import:R0603")
      (libsource (lib "eagle-import") (part "Labops_Lib_AH_R_0603"))
    )
    (comp (ref "R67")
      (value "10K 1%")
      (footprint "eagle-import:R0603")
      (libsource (lib "eagle-import") (part "Labops_Lib_AH_R_0603"))
    )
    (comp (ref "R68")
      (value "0R 1%")
      (footprint "eagle-import:R0603")
      (libsource (lib "eagle-import") (part "Labops_Lib_AH_R_0603"))
    )
    (comp (ref "R69")
      (value "470R 1%")
      (footprint "eagle-import:R0603")
      (libsource (lib "eagle-import") (part "Labops_Lib_AH_R_0603"))
    )
    (comp (ref "R70")
      (value "100R 1%")
      (footprint "eagle-import:R0603")
      (libsource (lib "eagle-import") (part "Labops_Lib_AH_R_0603"))
    )
    (comp (ref "R71")
      (value "470R 1%")
      (footprint "eagle-import:R0603")
      (libsource (lib "eagle-import") (part "Labops_Lib_AH_R_0603"))
    )
    (comp (ref "R72")
      (value "100R 1%")
      (footprint "eagle-import:R0603")
      (libsource (lib "eagle-import") (part "Labops_Lib_AH_R_0603"))
    )
    (comp (ref "R73")
      (value "470R 1%")
      (footprint "eagle-import:R0603")
      (libsource (lib "eagle-import") (part "Labops_Lib_AH_R_0603"))
    )
    (comp (ref "R74")
      (value "100R 1%")
      (footprint "eagle-import:R0603")
      (libsource (lib "eagle-import") (part "Labops_Lib_AH_R_0603"))
    )
    (comp (ref "R75")
      (value "470R 1%")
      (footprint "eagle-import:R0603")
      (libsource (lib "eagle-import") (part "Labops_Lib_AH_R_0603"))
    )
    (comp (ref "R76")
      (value "100R 1%")
      (footprint "eagle-import:R0603")
      (libsource (lib "eagle-import") (part "Labops_Lib_AH_R_0603"))
    )
    (comp (ref "R77")
      (value "470R 1%")
      (footprint "eagle-import:R0603")
      (libsource (lib "eagle-import") (part "Labops_Lib_AH_R_0603"))
    )
    (comp (ref "R78")
      (value "100R 1%")
      (footprint "eagle-import:R0603")
      (libsource (lib "eagle-import") (part "Labops_Lib_AH_R_0603"))
    )
    (comp (ref "R79")
      (value "470R 1%")
      (footprint "eagle-import:R0603")
      (libsource (lib "eagle-import") (part "Labops_Lib_AH_R_0603"))
    )
    (comp (ref "R80")
      (value "100R 1%")
      (footprint "eagle-import:R0603")
      (libsource (lib "eagle-import") (part "Labops_Lib_AH_R_0603"))
    )
    (comp (ref "R81")
      (value "470R 1%")
      (footprint "eagle-import:R0603")
      (libsource (lib "eagle-import") (part "Labops_Lib_AH_R_0603"))
    )
    (comp (ref "R82")
      (value "100R 1%")
      (footprint "eagle-import:R0603")
      (libsource (lib "eagle-import") (part "Labops_Lib_AH_R_0603"))
    )
    (comp (ref "R87")
      (value "100R 1%")
      (footprint "eagle-import:R0603")
      (libsource (lib "eagle-import") (part "Labops_Lib_AH_R_0603"))
    )
    (comp (ref "R88")
      (value "100R 1%")
      (footprint "eagle-import:R0603")
      (libsource (lib "eagle-import") (part "Labops_Lib_AH_R_0603"))
    )
    (comp (ref "R89")
      (value "100R 1%")
      (footprint "eagle-import:R0603")
      (libsource (lib "eagle-import") (part "Labops_Lib_AH_R_0603"))
    )
    (comp (ref "R90")
      (value "100R 1%")
      (footprint "eagle-import:R0603")
      (libsource (lib "eagle-import") (part "Labops_Lib_AH_R_0603"))
    )
    (comp (ref "V6")
      (value "0603ESDA-24N")
      (footprint "eagle-import:0603")
      (fields (field (name "MFR") "BORN"))
      (libsource (lib "eagle-import") (part "0603ESDA-24N"))
    )
    (comp (ref "V7")
      (value "0603ESDA-24N")
      (footprint "eagle-import:0603")
      (fields (field (name "MFR") "BORN"))
      (libsource (lib "eagle-import") (part "0603ESDA-24N"))
    )
    (comp (ref "V8")
      (value "0603ESDA-24N")
      (footprint "eagle-import:0603")
      (fields (field (name "MFR") "BORN"))
      (libsource (lib "eagle-import") (part "0603ESDA-24N"))
    )
    (comp (ref "X13")
      (value "MICROMATCH-16")
      (footprint "eagle-import:MICROMATCH-16")
      (fields (field (name "MF") "FARNELL") (field (name "MPN") "8-215464-6"))
      (libsource (lib "eagle-import") (part "MICROMATCH-16"))
    )
    (comp (ref "C1")
      (value "R49AN347050B1M")
      (footprint "eagle-import:R49AN347050B1M")
      (fields (field (name "MFR") "Kemet"))
      (libsource (lib "eagle-import") (part "R49AN347050B1M"))
    )
    (comp (ref "C2")
      (value "ERP610W471MEF0")
      (footprint "eagle-import:CAP-P12.5-H15-W4-D1")
      (fields (field (name "MFR") "Kemet"))
      (libsource (lib "eagle-import") (part "ERP610W471MEF0"))
    )
    (comp (ref "C6")
      (value "100nF/100V")
      (footprint "eagle-import:0603")
      (libsource (lib "eagle-import") (part "C_0603"))
    )
    (comp (ref "C10")
      (value "100nF/100V")
      (footprint "eagle-import:0603")
      (fields (field (name "PART_VALUE") "100nF/100V"))
      (libsource (lib "eagle-import") (part "C_0603"))
    )
    (comp (ref "C11")
      (value "100nF/100V")
      (footprint "eagle-import:0603")
      (fields (field (name "PART_VALUE") "100nF/100V"))
      (libsource (lib "eagle-import") (part "C_0603"))
    )
    (comp (ref "D1")
      (value "SS14")
      (footprint "eagle-import:SMA")
      (fields (field (name "MFR") "MCC"))
      (libsource (lib "eagle-import") (part "SS14"))
    )
    (comp (ref "D4")
      (value "PESD36VS2UT")
      (footprint "eagle-import:SOT23-3")
      (fields (field (name "MFR") "NXP"))
      (libsource (lib "eagle-import") (part "PESD36VS2UT"))
    )
    (comp (ref "D5")
      (value "BAS40-04,215")
      (footprint "eagle-import:SOT23-3")
      (fields (field (name "MFR") "NXP"))
      (libsource (lib "eagle-import") (part "BAS40-04,215"))
    )
    (comp (ref "D9")
      (value "BAS40-04,215")
      (footprint "eagle-import:SOT23-3")
      (fields (field (name "MFR") "NXP"))
      (libsource (lib "eagle-import") (part "BAS40-04,215"))
    )
    (comp (ref "F1")
      (value "696101000002")
      (footprint "eagle-import:FUSE_RM22.6")
      (fields (field (name "MFR") "Wurth Elektronik"))
      (libsource (lib "eagle-import") (part "696101000002"))
    )
    (comp (ref "IC4")
      (value "LT6106CS5#TRPBF")
      (footprint "eagle-import:SOT-23-5")
      (fields (field (name "MFR") "Analog Devices"))
      (libsource (lib "eagle-import") (part "LT6106CS5#TRPBF"))
    )
    (comp (ref "K1")
      (value "KB20C06A")
      (footprint "eagle-import:RELAY_KYOTO_KF0604D")
      (fields (field (name "MFR") "Kyotto"))
      (libsource (lib "eagle-import") (part "KB20C06A"))
    )
    (comp (ref "Q1")
      (value "DMP6185SEQ-13")
      (footprint "eagle-import:SOT223")
      (fields (field (name "MFR") "Diodes"))
      (libsource (lib "eagle-import") (part "DMP6185SEQ-13"))
    )
    (comp (ref "Q2")
      (value "2N7002")
      (footprint "eagle-import:SOT23")
      (fields (field (name "MFR") "Diodes, Guangdong Hotetech,NXP"))
      (libsource (lib "eagle-import") (part "2N7002"))
    )
    (comp (ref "Q8")
      (value "DMP6185SEQ-13")
      (footprint "eagle-import:SOT223")
      (fields (field (name "MFR") "Diodes"))
      (libsource (lib "eagle-import") (part "DMP6185SEQ-13"))
    )
    (comp (ref "Q9")
      (value "2N7002")
      (footprint "eagle-import:SOT23")
      (fields (field (name "MFR") "Diodes, Guangdong Hotetech,NXP"))
      (libsource (lib "eagle-import") (part "2N7002"))
    )
    (comp (ref "R1")
      (value "10K 1%")
      (footprint "eagle-import:0603")
      (libsource (lib "eagle-import") (part "R_0603"))
    )
    (comp (ref "R2")
      (value "10K 1%")
      (footprint "eagle-import:0603")
      (libsource (lib "eagle-import") (part "R_0603"))
    )
    (comp (ref "R3")
      (value "10K 1%")
      (footprint "eagle-import:0603")
      (libsource (lib "eagle-import") (part "R_0603"))
    )
    (comp (ref "R4")
      (value "10K 1%")
      (footprint "eagle-import:0603")
      (libsource (lib "eagle-import") (part "R_0603"))
    )
    (comp (ref "R5")
      (value "100R 1%")
      (footprint "eagle-import:0603")
      (libsource (lib "eagle-import") (part "R_0603"))
    )
    (comp (ref "R6")
      (value "220K 1%")
      (footprint "eagle-import:R2010")
      (libsource (lib "eagle-import") (part "R_2010"))
    )
    (comp (ref "R7")
      (value "220K 1%")
      (footprint "eagle-import:R2010")
      (libsource (lib "eagle-import") (part "R_2010"))
    )
    (comp (ref "R8")
      (value "RNF12FTD10M0")
      (footprint "eagle-import:RES-RM12.5-VR37")
      (fields (field (name "MFR") "Stackpole Electronics Inc"))
      (libsource (lib "eagle-import") (part "RNF12FTD10M0"))
    )
    (comp (ref "R18")
      (value "100R 1%")
      (footprint "eagle-import:R1206")
      (libsource (lib "eagle-import") (part "R_1206"))
    )
    (comp (ref "R19")
      (value "1K 1%")
      (footprint "eagle-import:R0603")
      (libsource (lib "eagle-import") (part "Labops_Lib_AH_R_0603"))
    )
    (comp (ref "R20")
      (value "100K 1%")
      (footprint "eagle-import:R0603")
      (libsource (lib "eagle-import") (part "Labops_Lib_AH_R_0603"))
    )
    (comp (ref "R32")
      (value "10K 1%")
      (footprint "eagle-import:0603")
      (libsource (lib "eagle-import") (part "R_0603"))
    )
    (comp (ref "R33")
      (value "10K 1%")
      (footprint "eagle-import:0603")
      (libsource (lib "eagle-import") (part "R_0603"))
    )
    (comp (ref "R34")
      (value "10K 1%")
      (footprint "eagle-import:0603")
      (libsource (lib "eagle-import") (part "R_0603"))
    )
    (comp (ref "R35")
      (value "100R 1%")
      (footprint "eagle-import:0603")
      (libsource (lib "eagle-import") (part "R_0603"))
    )
    (comp (ref "R36")
      (value "R_2010")
      (footprint "eagle-import:R2010")
      (fields (field (name "MFN") "RL73K2HR68JTE") (field (name "PART_VALUE") "680mR"))
      (libsource (lib "eagle-import") (part "R_2010"))
    )
    (comp (ref "R37")
      (value "2.2K 1%")
      (footprint "eagle-import:0603")
      (libsource (lib "eagle-import") (part "R_0603"))
    )
    (comp (ref "R38")
      (value "100R 1%")
      (footprint "eagle-import:0603")
      (libsource (lib "eagle-import") (part "R_0603"))
    )
    (comp (ref "R39")
      (value "100R 1%")
      (footprint "eagle-import:0603")
      (libsource (lib "eagle-import") (part "R_0603"))
    )
    (comp (ref "R46")
      (value "RNF12FTD10M0")
      (footprint "eagle-import:RES-RM12.5-VR37")
      (fields (field (name "MFR") "Stackpole Electronics Inc"))
      (libsource (lib "eagle-import") (part "RNF12FTD10M0"))
    )
    (comp (ref "V1")
      (value "B72205S0271K101B72205S2131K101")
      (footprint "eagle-import:EPCOS_B72205S0271K101_0")
      (fields (field (name "MFR") "EPCOS"))
      (libsource (lib "eagle-import") (part "B72205S0271K101B72205S2131K101"))
    )
    (comp (ref "V4")
      (value "B72205S0271K101B72205S2131K101")
      (footprint "eagle-import:EPCOS_B72205S0271K101_0")
      (fields (field (name "MFR") "EPCOS"))
      (libsource (lib "eagle-import") (part "B72205S0271K101B72205S2131K101"))
    )
    (comp (ref "X1")
      (value "B2B-XH-AM(LF)(SN)")
      (footprint "eagle-import:B2B-XH-AM(LF)(SN)")
      (fields (field (name "MFR") "JST"))
      (libsource (lib "eagle-import") (part "B2B-XH-AM(LF)(SN)"))
    )
    (comp (ref "X3")
      (value "282834-3")
      (footprint "eagle-import:TE_282834-3_0")
      (fields (field (name "MFR") "TE"))
      (libsource (lib "eagle-import") (part "282834-3"))
    )
    (comp (ref "X4")
      (value "282834-3")
      (footprint "eagle-import:TE_282834-3_0")
      (fields (field (name "MFR") "TE"))
      (libsource (lib "eagle-import") (part "282834-3"))
    )
    (comp (ref "X5")
      (value "726386-2TE_726386-2")
      (footprint "eagle-import:TE_726386-2")
      (fields
        (field (name "DIGIKEY_PART_NUMBER") "A114371-ND")
        (field (name "MF") "TE")
        (field (name "MOUSER_PART_NUMBER") "571-726386-2")
      )
      (libsource (lib "eagle-import") (part "726386-2TE_726386-2"))
    )
    (comp (ref "X6")
      (value "726386-2TE_726386-2")
      (footprint "eagle-import:TE_726386-2")
      (fields
        (field (name "DIGIKEY_PART_NUMBER") "A114371-ND")
        (field (name "MF") "TE")
        (field (name "MOUSER_PART_NUMBER") "571-726386-2")
      )
      (libsource (lib "eagle-import") (part "726386-2TE_726386-2"))
    )
    (comp (ref "X7")
      (value "726386-2TE_726386-2")
      (footprint "eagle-import:TE_726386-2")
      (fields
        (field (name "DIGIKEY_PART_NUMBER") "A114371-ND")
        (field (name "MF") "TE")
        (field (name "MOUSER_PART_NUMBER") "571-726386-2")
      )
      (libsource (lib "eagle-import") (part "726386-2TE_726386-2"))
    )
    (comp (ref "X8")
      (value "726386-2TE_726386-2")
      (footprint "eagle-import:TE_726386-2")
      (fields
        (field (name "DIGIKEY_PART_NUMBER") "A114371-ND")
        (field (name "MF") "TE")
        (field (name "MOUSER_PART_NUMBER") "571-726386-2")
      )
      (libsource (lib "eagle-import") (part "726386-2TE_726386-2"))
    )
    (comp (ref "X9")
      (value "726386-2TE_726386-2")
      (footprint "eagle-import:TE_726386-2")
      (fields
        (field (name "DIGIKEY_PART_NUMBER") "A114371-ND")
        (field (name "MF") "TE")
        (field (name "MOUSER_PART_NUMBER") "571-726386-2")
      )
      (libsource (lib "eagle-import") (part "726386-2TE_726386-2"))
    )
    (comp (ref "X10")
      (value "726386-2TE_726386-2")
      (footprint "eagle-import:TE_726386-2")
      (fields
        (field (name "DIGIKEY_PART_NUMBER") "A114371-ND")
        (field (name "MF") "TE")
        (field (name "MOUSER_PART_NUMBER") "571-726386-2")
      )
      (libsource (lib "eagle-import") (part "726386-2TE_726386-2"))
    )
    (comp (ref "X11")
      (value "282834-2")
      (footprint "eagle-import:TE_282834-2_0")
      (fields (field (name "MFR") "TE"))
      (libsource (lib "eagle-import") (part "282834-2"))
    )
    (comp (ref "X12")
      (value "615008148521")
      (footprint "eagle-import:615008148521")
      (fields (field (name "MFR") "Wurth Elektronik"))
      (libsource (lib "eagle-import") (part "615008148521"))
    )
    (comp (ref "X14")
      (value "615008148521")
      (footprint "eagle-import:615008148521")
      (fields (field (name "MFR") "Wurth Elektronik"))
      (libsource (lib "eagle-import") (part "615008148521"))
    )
    (comp (ref "C3")
      (value "100nF/100V")
      (footprint "eagle-import:0603")
      (libsource (lib "eagle-import") (part "C_0603"))
    )
    (comp (ref "C4")
      (value "100nF/100V")
      (footprint "eagle-import:0603")
      (libsource (lib "eagle-import") (part "C_0603"))
    )
    (comp (ref "C5")
      (value "100nF/ 100V")
      (footprint "eagle-import:0603")
      (libsource (lib "eagle-import") (part "C_0603"))
    )
    (comp (ref "C12")
      (value "100nF/ 100V")
      (footprint "eagle-import:0603")
      (libsource (lib "eagle-import") (part "C_0603"))
    )
    (comp (ref "C13")
      (value "100nF/ 100V")
      (footprint "eagle-import:0603")
      (libsource (lib "eagle-import") (part "C_0603"))
    )
    (comp (ref "C14")
      (value "10uF/25V")
      (footprint "eagle-import:0603")
      (libsource (lib "eagle-import") (part "C_0603"))
    )
    (comp (ref "C15")
      (value "10uF/25V")
      (footprint "eagle-import:0603")
      (libsource (lib "eagle-import") (part "C_0603"))
    )
    (comp (ref "C16")
      (value "10uF/25V")
      (footprint "eagle-import:0603")
      (libsource (lib "eagle-import") (part "C_0603"))
    )
    (comp (ref "C17")
      (value "100nF/ 100V")
      (footprint "eagle-import:0603")
      (libsource (lib "eagle-import") (part "C_0603"))
    )
    (comp (ref "C18")
      (value "50PX470MEFC10X20")
      (footprint "eagle-import:CAPACITOR-ELKO-RM5-10X16")
      (fields (field (name "MFR") "Rubicon"))
      (libsource (lib "eagle-import") (part "50PX470MEFC10X20"))
    )
    (comp (ref "C19")
      (value "100nF/ 100V")
      (footprint "eagle-import:0603")
      (libsource (lib "eagle-import") (part "C_0603"))
    )
    (comp (ref "C20")
      (value "10uF/25V")
      (footprint "eagle-import:0603")
      (libsource (lib "eagle-import") (part "C_0603"))
    )
    (comp (ref "C21")
      (value "100nF/ 100V")
      (footprint "eagle-import:0603")
      (libsource (lib "eagle-import") (part "C_0603"))
    )
    (comp (ref "C22")
      (value "10uF/25V")
      (footprint "eagle-import:0603")
      (libsource (lib "eagle-import") (part "C_0603"))
    )
    (comp (ref "C23")
      (value "100nF/ 100V")
      (footprint "eagle-import:0603")
      (libsource (lib "eagle-import") (part "C_0603"))
    )
    (comp (ref "C24")
      (value "100nF/100V")
      (footprint "eagle-import:0603")
      (libsource (lib "eagle-import") (part "C_0603"))
    )
    (comp (ref "C25")
      (value "100nF/100V")
      (footprint "eagle-import:0603")
      (libsource (lib "eagle-import") (part "C_0603"))
    )
    (comp (ref "C36")
      (value "1uF/25V")
      (footprint "eagle-import:0603")
      (libsource (lib "eagle-import") (part "C_0603"))
    )
    (comp (ref "C37")
      (value "1uF/25V")
      (footprint "eagle-import:0603")
      (libsource (lib "eagle-import") (part "C_0603"))
    )
    (comp (ref "C38")
      (value "100nF/100V")
      (footprint "eagle-import:0603")
      (libsource (lib "eagle-import") (part "C_0603"))
    )
    (comp (ref "C39")
      (value "100nF/100V")
      (footprint "eagle-import:0603")
      (libsource (lib "eagle-import") (part "C_0603"))
    )
    (comp (ref "C49")
      (value "100nF/ 100V")
      (footprint "eagle-import:0603")
      (libsource (lib "eagle-import") (part "C_0603"))
    )
    (comp (ref "D3")
      (value "MMBZ4696-HE3-18")
      (footprint "eagle-import:SOT23-3")
      (fields (field (name "MFR") "Vishay"))
      (libsource (lib "eagle-import") (part "MMBZ4696-HE3-18"))
    )
    (comp (ref "D10")
      (value "BAS40-04,215")
      (footprint "eagle-import:SOT23-3")
      (fields (field (name "MFR") "NXP"))
      (libsource (lib "eagle-import") (part "BAS40-04,215"))
    )
    (comp (ref "D11")
      (value "SS14")
      (footprint "eagle-import:SMA")
      (fields (field (name "MFR") "MCC"))
      (libsource (lib "eagle-import") (part "SS14"))
    )
    (comp (ref "D12")
      (value "26-21/GPC-F3138B/CA")
      (footprint "eagle-import:SMD1206-LED")
      (fields (field (name "MFR") "Everlight"))
      (libsource (lib "eagle-import") (part "26-21/GPC-F3138B/CA"))
    )
    (comp (ref "D13")
      (value "BAS40-04,215")
      (footprint "eagle-import:SOT23-3")
      (fields (field (name "MFR") "NXP"))
      (libsource (lib "eagle-import") (part "BAS40-04,215"))
    )
    (comp (ref "FID1")
      (value "FIDUCIAL")
      (footprint "eagle-import:FIDUCIAL")
      (libsource (lib "eagle-import") (part "FIDUCIAL"))
    )
    (comp (ref "FID2")
      (value "FIDUCIAL")
      (footprint "eagle-import:FIDUCIAL")
      (libsource (lib "eagle-import") (part "FIDUCIAL"))
    )
    (comp (ref "H1")
      (value "MOUNT-PAD-ROUND3.0")
      (footprint "eagle-import:3,0-PAD")
      (libsource (lib "eagle-import") (part "MOUNT-PAD-ROUND3.0"))
    )
    (comp (ref "H2")
      (value "MOUNT-PAD-ROUND3.0")
      (footprint "eagle-import:3,0-PAD")
      (libsource (lib "eagle-import") (part "MOUNT-PAD-ROUND3.0"))
    )
    (comp (ref "H3")
      (value "MOUNT-PAD-ROUND3.0")
      (footprint "eagle-import:3,0-PAD")
      (libsource (lib "eagle-import") (part "MOUNT-PAD-ROUND3.0"))
    )
    (comp (ref "H4")
      (value "MOUNT-PAD-ROUND3.0")
      (footprint "eagle-import:3,0-PAD")
      (libsource (lib "eagle-import") (part "MOUNT-PAD-ROUND3.0"))
    )
    (comp (ref "IC1")
      (value "SN65HVD3082EDR")
      (footprint "eagle-import:SOIC8")
      (fields (field (name "MFR") "TI,3Peak"))
      (libsource (lib "eagle-import") (part "SN65HVD3082EDR"))
    )
    (comp (ref "IC5")
      (value "TPS54202DDCR")
      (footprint "eagle-import:SOT23-6")
      (fields (field (name "MFR") "Texas Instruments"))
      (libsource (lib "eagle-import") (part "TPS54202DDCR"))
    )
    (comp (ref "IC6")
      (value "LD1117S33TR")
      (footprint "eagle-import:SOT223_LD1117S33TR")
      (fields (field (name "MFR") "STmicro, Diodes, TI,"))
      (libsource (lib "eagle-import") (part "LD1117S33TR"))
    )
    (comp (ref "IC8")
      (value "LM317AEMP")
      (footprint "eagle-import:SOT223_LM317AEMP")
      (libsource (lib "eagle-import") (part "LM317AEMP"))
    )
    (comp (ref "J1")
      (value "ESP32-PICO-KIT")
      (footprint "eagle-import:XCVR_ESP32-PICO-KIT")
      (fields (field (name "MFR") "Espressif Systems"))
      (libsource (lib "eagle-import") (part "ESP32-PICO-KIT"))
    )
    (comp (ref "L1")
      (value "SRN8040TA-220M")
      (footprint "eagle-import:SRN8040TA-220M")
      (fields (field (name "MFR") "Bourns"))
      (libsource (lib "eagle-import") (part "SRN8040TA-220M"))
    )
    (comp (ref "Q5")
      (value "DMP6185SEQ-13")
      (footprint "eagle-import:SOT223")
      (fields (field (name "MFR") "Diodes"))
      (libsource (lib "eagle-import") (part "DMP6185SEQ-13"))
    )
    (comp (ref "Q10")
      (value "BC817")
      (footprint "eagle-import:SOT23")
      (fields (field (name "MFR") "NXP"))
      (libsource (lib "eagle-import") (part "BC817"))
    )
    (comp (ref "R14")
      (value "10K 1%")
      (footprint "eagle-import:R0603")
      (libsource (lib "eagle-import") (part "Labops_Lib_AH_R_0603"))
    )
    (comp (ref "R15")
      (value "1K 1%")
      (footprint "eagle-import:R0603")
      (libsource (lib "eagle-import") (part "Labops_Lib_AH_R_0603"))
    )
    (comp (ref "R16")
      (value "470R 1%")
      (footprint "eagle-import:R0603")
      (libsource (lib "eagle-import") (part "Labops_Lib_AH_R_0603"))
    )
    (comp (ref "R17")
      (value "10K 1%")
      (footprint "eagle-import:R0603")
      (libsource (lib "eagle-import") (part "Labops_Lib_AH_R_0603"))
    )
    (comp (ref "R40")
      (value "22K 1%")
      (footprint "eagle-import:R0603")
      (libsource (lib "eagle-import") (part "Labops_Lib_AH_R_0603"))
    )
    (comp (ref "R41")
      (value "2.8K 1%")
      (footprint "eagle-import:R0603")
      (libsource (lib "eagle-import") (part "Labops_Lib_AH_R_0603"))
    )
    (comp (ref "R42")
      (value "100R 1%")
      (footprint "eagle-import:R0603")
      (libsource (lib "eagle-import") (part "Labops_Lib_AH_R_0603"))
    )
    (comp (ref "R43")
      (value "22K 1%")
      (footprint "eagle-import:R0603")
      (libsource (lib "eagle-import") (part "Labops_Lib_AH_R_0603"))
    )
    (comp (ref "R44")
      (value "3K01 1%")
      (footprint "eagle-import:R0603")
      (libsource (lib "eagle-import") (part "Labops_Lib_AH_R_0603"))
    )
    (comp (ref "R45")
      (value "22K 1%")
      (footprint "eagle-import:R0603")
      (libsource (lib "eagle-import") (part "Labops_Lib_AH_R_0603"))
    )
    (comp (ref "R47")
      (value "470R 1%")
      (footprint "eagle-import:R0603")
      (libsource (lib "eagle-import") (part "Labops_Lib_AH_R_0603"))
    )
    (comp (ref "R48")
      (value "470R 1%")
      (footprint "eagle-import:R0603")
      (libsource (lib "eagle-import") (part "Labops_Lib_AH_R_0603"))
    )
    (comp (ref "R49")
      (value "100R 1%")
      (footprint "eagle-import:R0603")
      (libsource (lib "eagle-import") (part "Labops_Lib_AH_R_0603"))
    )
    (comp (ref "R50")
      (value "100R 1%")
      (footprint "eagle-import:R0603")
      (libsource (lib "eagle-import") (part "Labops_Lib_AH_R_0603"))
    )
    (comp (ref "R51")
      (value "100K 1%")
      (footprint "eagle-import:R1206")
      (libsource (lib "eagle-import") (part "R_1206"))
    )
    (comp (ref "R52")
      (value "100R 1%")
      (footprint "eagle-import:R0603")
      (libsource (lib "eagle-import") (part "Labops_Lib_AH_R_0603"))
    )
    (comp (ref "R53")
      (value "0R 1%")
      (footprint "eagle-import:R0603")
      (libsource (lib "eagle-import") (part "Labops_Lib_AH_R_0603"))
    )
    (comp (ref "R54")
      (value "1K 1%")
      (footprint "eagle-import:R1206")
      (libsource (lib "eagle-import") (part "R_1206"))
    )
    (comp (ref "R55")
      (value "0R 1%")
      (footprint "eagle-import:R0603")
      (libsource (lib "eagle-import") (part "Labops_Lib_AH_R_0603"))
    )
    (comp (ref "R83")
      (value "1K 1%")
      (footprint "eagle-import:R0603")
      (libsource (lib "eagle-import") (part "Labops_Lib_AH_R_0603"))
    )
    (comp (ref "R85")
      (value "0R 1%")
      (footprint "eagle-import:R1206")
      (libsource (lib "eagle-import") (part "R_1206"))
    )
    (comp (ref "R86")
      (value "82R 1%")
      (footprint "eagle-import:R1206")
      (libsource (lib "eagle-import") (part "R_1206"))
    )
    (comp (ref "R91")
      (value "1k 1%")
      (footprint "eagle-import:R0603")
      (libsource (lib "eagle-import") (part "Labops_Lib_AH_R_0603"))
    )
    (comp (ref "R92")
      (value "24K 1%")
      (footprint "eagle-import:R0603")
      (libsource (lib "eagle-import") (part "Labops_Lib_AH_R_0603"))
    )
    (comp (ref "R96")
      (value "100R 1%")
      (footprint "eagle-import:R0603")
      (libsource (lib "eagle-import") (part "Labops_Lib_AH_R_0603"))
    )
    (comp (ref "R97")
      (value "100R 1%")
      (footprint "eagle-import:R0603")
      (libsource (lib "eagle-import") (part "Labops_Lib_AH_R_0603"))
    )
    (comp (ref "SW1")
      (value "L101011MS02Q")
      (footprint "eagle-import:L101011MS02Q")
      (fields (field (name "MFR") "C&K"))
      (libsource (lib "eagle-import") (part "L101011MS02Q"))
    )
    (comp (ref "V2")
      (value "0603ESDA-24N")
      (footprint "eagle-import:0603")
      (fields (field (name "MFR") "BORN"))
      (libsource (lib "eagle-import") (part "0603ESDA-24N"))
    )
    (comp (ref "V3")
      (value "0603ESDA-24N")
      (footprint "eagle-import:0603")
      (fields (field (name "MFR") "BORN"))
      (libsource (lib "eagle-import") (part "0603ESDA-24N"))
    )
  )
  (nets
    (net (code "1") (name "AI_24V0") (class "Default")
      (node (ref "C19") (pin "1") (pinfunction "1_1") (pintype "passive"))
      (node (ref "D10") (pin "3") (pinfunction "C1_A2_3") (pintype "passive"))
      (node (ref "R42") (pin "1") (pinfunction "1_1") (pintype "passive"))
      (node (ref "U2") (pin "115") (pinfunction "P502_115") (pintype "bidirectional"))
    )
    (net (code "2") (name "AI_I_SENSE_CONDUTIV_SENSOR") (class "Default")
      (node (ref "C9") (pin "1") (pinfunction "1_1") (pintype "passive"))
      (node (ref "D8") (pin "3") (pinfunction "C1_A2_3") (pintype "passive"))
      (node (ref "R30") (pin "2") (pinfunction "2_2") (pintype "passive"))
      (node (ref "U2") (pin "116") (pinfunction "P503_116") (pintype "bidirectional"))
    )
    (net (code "3") (name "AI_I_SENSE_PH_SENSOR") (class "Default")
      (node (ref "C11") (pin "1") (pinfunction "1_1") (pintype "passive"))
      (node (ref "D9") (pin "3") (pinfunction "C1_A2_3") (pintype "passive"))
      (node (ref "R38") (pin "2") (pinfunction "2_2") (pintype "passive"))
      (node (ref "U2") (pin "113") (pinfunction "P500_113") (pintype "bidirectional"))
    )
    (net (code "4") (name "AI_V_CONDUCTIV_SENSOR") (class "Default")
      (node (ref "D7") (pin "3") (pinfunction "C1_A2_3") (pintype "passive"))
      (node (ref "R22") (pin "1") (pinfunction "1_1") (pintype "passive"))
      (node (ref "R23") (pin "2") (pinfunction "2_2") (pintype "passive"))
      (node (ref "U2") (pin "117") (pinfunction "P504_117") (pintype "bidirectional"))
    )
    (net (code "5") (name "AI_V_PH_SENSOR") (class "Default")
      (node (ref "D5") (pin "3") (pinfunction "C1_A2_3") (pintype "passive"))
      (node (ref "R19") (pin "1") (pinfunction "1_1") (pintype "passive"))
      (node (ref "R20") (pin "2") (pinfunction "2_2") (pintype "passive"))
      (node (ref "U2") (pin "114") (pinfunction "P501_114") (pintype "bidirectional"))
    )
    (net (code "6") (name "CONDUCTIV_PUMP_MAINS_L_SW") (class "Default")
      (node (ref "K2") (pin "P$3") (pinfunction "3_P$3") (pintype "passive"))
      (node (ref "V5") (pin "2") (pinfunction "2_2") (pintype "passive"))
      (node (ref "X9") (pin "1") (pinfunction "1_1") (pintype "passive"))
      (node (ref "X9") (pin "1-2") (pinfunction "1_1-2") (pintype "passive"))
    )
    (net (code "7") (name "DBG_SWCLK") (class "Default")
      (node (ref "U2") (pin "72") (pinfunction "P300/TCK/SWCLK_72") (pintype "bidirectional"))
      (node (ref "X2") (pin "4") (pinfunction "4_4") (pintype "bidirectional"))
    )
    (net (code "8") (name "DBG_SWDIO") (class "Default")
      (node (ref "U2") (pin "73") (pinfunction "P108/TMS/SWDIO_73") (pintype "bidirectional"))
      (node (ref "X2") (pin "2") (pinfunction "2_2") (pintype "bidirectional"))
    )
    (net (code "9") (name "DBG_SWO") (class "Default")
      (node (ref "U2") (pin "74") (pinfunction "P109/TDO_74") (pintype "bidirectional"))
      (node (ref "X2") (pin "6") (pinfunction "6_6") (pintype "bidirectional"))
    )
    (net (code "10") (name "DI_DOSING_EN") (class "Default")
      (node (ref "D13") (pin "3") (pinfunction "C1_A2_3") (pintype "passive"))
      (node (ref "R52") (pin "1") (pinfunction "1_1") (pintype "passive"))
      (node (ref "R54") (pin "1") (pinfunction "1_1") (pintype "passive"))
      (node (ref "U2") (pin "31") (pinfunction "P412_31") (pintype "bidirectional"))
    )
    (net (code "11") (name "DI_UART_RX_ESP32") (class "Default")
      (node (ref "R96") (pin "1") (pinfunction "1_1") (pintype "passive"))
      (node (ref "U2") (pin "71") (pinfunction "P301_71") (pintype "bidirectional"))
    )
    (net (code "12") (name "DI_USART_RX") (class "Default")
      (node (ref "Q10") (pin "3") (pinfunction "C_3") (pintype "passive"))
      (node (ref "R15") (pin "1") (pinfunction "1_1") (pintype "passive"))
      (node (ref "U2") (pin "35") (pinfunction "P408_35") (pintype "bidirectional"))
    )
    (net (code "13") (name "DO_7XSEGMENT_1_EN") (class "Default")
      (node (ref "R56") (pin "1") (pinfunction "1_1") (pintype "passive"))
      (node (ref "U2") (pin "1") (pinfunction "P400_1") (pintype "bidirectional"))
    )
    (net (code "14") (name "DO_7XSEGMENT_2_EN") (class "Default")
      (node (ref "R64") (pin "1") (pinfunction "1_1") (pintype "passive"))
      (node (ref "U2") (pin "2") (pinfunction "P401_2") (pintype "bidirectional"))
    )
    (net (code "15") (name "DO_7XSEGMENT_3_EN") (class "Default")
      (node (ref "R60") (pin "1") (pinfunction "1_1") (pintype "passive"))
      (node (ref "U2") (pin "3") (pinfunction "P402_3") (pintype "bidirectional"))
    )
    (net (code "16") (name "DO_BCD_A") (class "Default")
      (node (ref "R87") (pin "2") (pinfunction "2_2") (pintype "passive"))
      (node (ref "U2") (pin "106") (pinfunction "P102_106") (pintype "bidirectional"))
    )
    (net (code "17") (name "DO_BCD_B") (class "Default")
      (node (ref "R88") (pin "2") (pinfunction "2_2") (pintype "passive"))
      (node (ref "U2") (pin "105") (pinfunction "P103_105") (pintype "bidirectional"))
    )
    (net (code "18") (name "DO_BCD_C") (class "Default")
      (node (ref "R89") (pin "2") (pinfunction "2_2") (pintype "passive"))
      (node (ref "U2") (pin "104") (pinfunction "P104_104") (pintype "bidirectional"))
    )
    (net (code "19") (name "DO_BCD_D") (class "Default")
      (node (ref "R90") (pin "2") (pinfunction "2_2") (pintype "passive"))
      (node (ref "U2") (pin "103") (pinfunction "P105_103") (pintype "bidirectional"))
    )
    (net (code "20") (name "DO_COMM_TX_EN") (class "Default")
      (node (ref "R47") (pin "2") (pinfunction "2_2") (pintype "passive"))
      (node (ref "U2") (pin "33") (pinfunction "P410_33") (pintype "bidirectional"))
    )
    (net (code "21") (name "DO_CONDUCTIV_PUMP_ON_LED") (class "Default")
      (node (ref "R82") (pin "1") (pinfunction "1_1") (pintype "passive"))
      (node (ref "U2") (pin "8") (pinfunction "P700_8") (pintype "bidirectional"))
    )
    (net (code "22") (name "DO_CONDUCTIV_SENSOR_DISPLAY_ON") (class "Default")
      (node (ref "R78") (pin "1") (pinfunction "1_1") (pintype "passive"))
      (node (ref "U2") (pin "7") (pinfunction "P406_7") (pintype "bidirectional"))
    )
    (net (code "23") (name "DO_CONDUCTIV_SENSOR_ON") (class "Default")
      (node (ref "R27") (pin "2") (pinfunction "2_2") (pintype "passive"))
      (node (ref "U2") (pin "108") (pinfunction "P100_108") (pintype "bidirectional"))
    )
    (net (code "24") (name "DO_CTRL_GREEN_STATUS_LED") (class "Default")
      (node (ref "R72") (pin "1") (pinfunction "1_1") (pintype "passive"))
      (node (ref "U2") (pin "5") (pinfunction "P404_5") (pintype "bidirectional"))
    )
    (net (code "25") (name "DO_CTRL_RED_STATUS_LED") (class "Default")
      (node (ref "R74") (pin "1") (pinfunction "1_1") (pintype "passive"))
      (node (ref "U2") (pin "6") (pinfunction "P405_6") (pintype "bidirectional"))
    )
    (net (code "26") (name "DO_CTRL_YELLOW_STATUS_LED") (class "Default")
      (node (ref "R70") (pin "1") (pinfunction "1_1") (pintype "passive"))
      (node (ref "U2") (pin "4") (pinfunction "P403_4") (pintype "bidirectional"))
    )
    (net (code "27") (name "DO_ESP32_EN") (class "Default")
      (node (ref "J1") (pin "J2_18") (pinfunction "EN_J2_18") (pintype "input"))
      (node (ref "R83") (pin "2") (pinfunction "2_2") (pintype "passive"))
      (node (ref "U2") (pin "69") (pinfunction "P303_69") (pintype "bidirectional"))
    )
    (net (code "28") (name "DO_PH_PUMP_ON_LED") (class "Default")
      (node (ref "R80") (pin "1") (pinfunction "1_1") (pintype "passive"))
      (node (ref "U2") (pin "10") (pinfunction "P702_10") (pintype "bidirectional"))
    )
    (net (code "29") (name "DO_PH_SENSOR_DISPLAY_ON") (class "Default")
      (node (ref "R76") (pin "1") (pinfunction "1_1") (pintype "passive"))
      (node (ref "U2") (pin "9") (pinfunction "P701_9") (pintype "bidirectional"))
    )
    (net (code "30") (name "DO_PH_SENSOR_ON") (class "Default")
      (node (ref "R35") (pin "2") (pinfunction "2_2") (pintype "passive"))
      (node (ref "U2") (pin "107") (pinfunction "P101_107") (pintype "bidirectional"))
    )
    (net (code "31") (name "DO_UART_TX_ESP32") (class "Default")
      (node (ref "R97") (pin "1") (pinfunction "1_1") (pintype "passive"))
      (node (ref "U2") (pin "70") (pinfunction "P302_70") (pintype "bidirectional"))
    )
    (net (code "32") (name "DO_USART_TX") (class "Default")
      (node (ref "R48") (pin "2") (pinfunction "2_2") (pintype "passive"))
      (node (ref "U2") (pin "34") (pinfunction "P409_34") (pintype "bidirectional"))
    )
    (net (code "33") (name "DO_V_CONDUCTIV_PUMP_ON") (class "Default")
      (node (ref "R13") (pin "2") (pinfunction "2_2") (pintype "passive"))
      (node (ref "U2") (pin "75") (pinfunction "P110/TDI_75") (pintype "bidirectional"))
    )
    (net (code "34") (name "DO_V_PH_PUMP_ON") (class "Default")
      (node (ref "R5") (pin "2") (pinfunction "2_2") (pintype "passive"))
      (node (ref "U2") (pin "76") (pinfunction "P111_76") (pintype "bidirectional"))
    )
    (net (code "35") (name "ESP32_RXD") (class "Default")
      (node (ref "J1") (pin "J2_12") (pinfunction "RXD0_J2_12") (pintype "bidirectional"))
      (node (ref "R97") (pin "2") (pinfunction "2_2") (pintype "passive"))
    )
    (net (code "36") (name "ESP32_TXD") (class "Default")
      (node (ref "J1") (pin "J2_13") (pinfunction "TXD0_J2_13") (pintype "bidirectional"))
      (node (ref "R96") (pin "2") (pinfunction "2_2") (pintype "passive"))
    )
    (net (code "37") (name "GND") (class "Default")
      (node (ref "C10") (pin "2") (pinfunction "2_2") (pintype "passive"))
      (node (ref "C11") (pin "2") (pinfunction "2_2") (pintype "passive"))
      (node (ref "C12") (pin "2") (pinfunction "2_2") (pintype "passive"))
      (node (ref "C13") (pin "2") (pinfunction "2_2") (pintype "passive"))
      (node (ref "C14") (pin "2") (pinfunction "2_2") (pintype "passive"))
      (node (ref "C15") (pin "2") (pinfunction "2_2") (pintype "passive"))
      (node (ref "C16") (pin "2") (pinfunction "2_2") (pintype "passive"))
      (node (ref "C18") (pin "2") (pinfunction "-_2") (pintype "passive"))
      (node (ref "C19") (pin "2") (pinfunction "2_2") (pintype "passive"))
      (node (ref "C2") (pin "P$1") (pinfunction "1_P$1") (pintype "passive"))
      (node (ref "C20") (pin "2") (pinfunction "2_2") (pintype "passive"))
      (node (ref "C21") (pin "2") (pinfunction "2_2") (pintype "passive"))
      (node (ref "C22") (pin "2") (pinfunction "2_2") (pintype "passive"))
      (node (ref "C23") (pin "2") (pinfunction "2_2") (pintype "passive"))
      (node (ref "C24") (pin "2") (pinfunction "2_2") (pintype "passive"))
      (node (ref "C25") (pin "1") (pinfunction "1_1") (pintype "passive"))
      (node (ref "C26") (pin "1") (pinfunction "1_1") (pintype "passive"))
      (node (ref "C27") (pin "1") (pinfunction "1_1") (pintype "passive"))
      (node (ref "C28") (pin "1") (pinfunction "1_1") (pintype "passive"))
      (node (ref "C29") (pin "1") (pinfunction "1_1") (pintype "passive"))
      (node (ref "C3") (pin "2") (pinfunction "2_2") (pintype "passive"))
      (node (ref "C30") (pin "1") (pinfunction "1_1") (pintype "passive"))
      (node (ref "C31") (pin "1") (pinfunction "1_1") (pintype "passive"))
      (node (ref "C32") (pin "1") (pinfunction "1_1") (pintype "passive"))
      (node (ref "C33") (pin "1") (pinfunction "1_1") (pintype "passive"))
      (node (ref "C34") (pin "1") (pinfunction "1_1") (pintype "passive"))
      (node (ref "C35") (pin "1") (pinfunction "1_1") (pintype "passive"))
      (node (ref "C36") (pin "2") (pinfunction "2_2") (pintype "passive"))
      (node (ref "C37") (pin "2") (pinfunction "2_2") (pintype "passive"))
      (node (ref "C38") (pin "2") (pinfunction "2_2") (pintype "passive"))
      (node (ref "C39") (pin "2") (pinfunction "2_2") (pintype "passive"))
      (node (ref "C4") (pin "2") (pinfunction "2_2") (pintype "passive"))
      (node (ref "C40") (pin "2") (pinfunction "2_2") (pintype "passive"))
      (node (ref "C41") (pin "2") (pinfunction "2_2") (pintype "passive"))
      (node (ref "C44") (pin "2") (pinfunction "2_2") (pintype "passive"))
      (node (ref "C49") (pin "2") (pinfunction "2_2") (pintype "passive"))
      (node (ref "C5") (pin "2") (pinfunction "2_2") (pintype "passive"))
      (node (ref "C50") (pin "1") (pinfunction "1_1") (pintype "passive"))
      (node (ref "C51") (pin "1") (pinfunction "1_1") (pintype "passive"))
      (node (ref "C53") (pin "1") (pinfunction "1_1") (pintype "passive"))
      (node (ref "C55") (pin "1") (pinfunction "1_1") (pintype "passive"))
      (node (ref "C56") (pin "1") (pinfunction "1_1") (pintype "passive"))
      (node (ref "C57") (pin "1") (pinfunction "1_1") (pintype "passive"))
      (node (ref "C58") (pin "1") (pinfunction "1_1") (pintype "passive"))
      (node (ref "C59") (pin "1") (pinfunction "1_1") (pintype "passive"))
      (node (ref "C6") (pin "1") (pinfunction "1_1") (pintype "passive"))
      (node (ref "C60") (pin "1") (pinfunction "1_1") (pintype "passive"))
      (node (ref "C61") (pin "1") (pinfunction "1_1") (pintype "passive"))
      (node (ref "C62") (pin "1") (pinfunction "1_1") (pintype "passive"))
      (node (ref "C63") (pin "1") (pinfunction "1_1") (pintype "passive"))
      (node (ref "C64") (pin "1") (pinfunction "1_1") (pintype "passive"))
      (node (ref "C65") (pin "1") (pinfunction "1_1") (pintype "passive"))
      (node (ref "C66") (pin "1") (pinfunction "1_1") (pintype "passive"))
      (node (ref "C67") (pin "1") (pinfunction "1_1") (pintype "passive"))
      (node (ref "C68") (pin "1") (pinfunction "1_1") (pintype "passive"))
      (node (ref "C7") (pin "1") (pinfunction "1_1") (pintype "passive"))
      (node (ref "C8") (pin "2") (pinfunction "2_2") (pintype "passive"))
      (node (ref "C9") (pin "2") (pinfunction "2_2") (pintype "passive"))
      (node (ref "D1") (pin "2") (pinfunction "A_2") (pintype "passive"))
      (node (ref "D10") (pin "1") (pinfunction "A1_1") (pintype "passive"))
      (node (ref "D13") (pin "1") (pinfunction "A1_1") (pintype "passive"))
      (node (ref "D2") (pin "2") (pinfunction "A_2") (pintype "passive"))
      (node (ref "D4") (pin "1") (pinfunction "C1_1") (pintype "passive"))
      (node (ref "D5") (pin "1") (pinfunction "A1_1") (pintype "passive"))
      (node (ref "D6") (pin "1") (pinfunction "C1_1") (pintype "passive"))
      (node (ref "D7") (pin "1") (pinfunction "A1_1") (pintype "passive"))
      (node (ref "D8") (pin "1") (pinfunction "A1_1") (pintype "passive"))
      (node (ref "D9") (pin "1") (pinfunction "A1_1") (pintype "passive"))
      (node (ref "IC1") (pin "5") (pinfunction "GND_5") (pintype "bidirectional"))
      (node (ref "IC2") (pin "2") (pinfunction "GND_2") (pintype "power_in"))
      (node (ref "IC3") (pin "2") (pinfunction "V-_2") (pintype "bidirectional"))
      (node (ref "IC4") (pin "2") (pinfunction "V-_2") (pintype "bidirectional"))
      (node (ref "IC5") (pin "1") (pinfunction "GND_1") (pintype "bidirectional"))
      (node (ref "IC6") (pin "1") (pinfunction "GND_1") (pintype "power_in"))
      (node (ref "J1") (pin "J2_19") (pinfunction "GND_1_J2_19") (pintype "power_in"))
      (node (ref "J1") (pin "J3_19") (pinfunction "GND_2_J3_19") (pintype "power_in"))
      (node (ref "K1") (pin "P$1") (pinfunction "1_P$1") (pintype "passive"))
      (node (ref "K2") (pin "P$1") (pinfunction "1_P$1") (pintype "passive"))
      (node (ref "Q11") (pin "2") (pinfunction "S_2") (pintype "passive"))
      (node (ref "Q13") (pin "2") (pinfunction "S_2") (pintype "passive"))
      (node (ref "Q15") (pin "2") (pinfunction "S_2") (pintype "passive"))
      (node (ref "Q2") (pin "2") (pinfunction "S_2") (pintype "passive"))
      (node (ref "Q4") (pin "2") (pinfunction "S_2") (pintype "passive"))
      (node (ref "Q7") (pin "2") (pinfunction "S_2") (pintype "passive"))
      (node (ref "Q9") (pin "2") (pinfunction "S_2") (pintype "passive"))
      (node (ref "R1") (pin "1") (pinfunction "1_1") (pintype "passive"))
      (node (ref "R12") (pin "1") (pinfunction "1_1") (pintype "passive"))
      (node (ref "R17") (pin "1") (pinfunction "1_1") (pintype "passive"))
      (node (ref "R18") (pin "1") (pinfunction "1_1") (pintype "passive"))
      (node (ref "R20") (pin "1") (pinfunction "1_1") (pintype "passive"))
      (node (ref "R21") (pin "1") (pinfunction "1_1") (pintype "passive"))
      (node (ref "R23") (pin "1") (pinfunction "1_1") (pintype "passive"))
      (node (ref "R26") (pin "1") (pinfunction "1_1") (pintype "passive"))
      (node (ref "R29") (pin "1") (pinfunction "1_1") (pintype "passive"))
      (node (ref "R34") (pin "1") (pinfunction "1_1") (pintype "passive"))
      (node (ref "R37") (pin "1") (pinfunction "1_1") (pintype "passive"))
      (node (ref "R4") (pin "1") (pinfunction "1_1") (pintype "passive"))
      (node (ref "R41") (pin "1") (pinfunction "1_1") (pintype "passive"))
      (node (ref "R44") (pin "2") (pinfunction "2_2") (pintype "passive"))
      (node (ref "R46") (pin "1") (pinfunction "1_1") (pintype "passive"))
      (node (ref "R51") (pin "1") (pinfunction "1_1") (pintype "passive"))
      (node (ref "R57") (pin "1") (pinfunction "1_1") (pintype "passive"))
      (node (ref "R61") (pin "1") (pinfunction "1_1") (pintype "passive"))
      (node (ref "R65") (pin "1") (pinfunction "1_1") (pintype "passive"))
      (node (ref "R69") (pin "1") (pinfunction "1_1") (pintype "passive"))
      (node (ref "R71") (pin "1") (pinfunction "1_1") (pintype "passive"))
      (node (ref "R73") (pin "1") (pinfunction "1_1") (pintype "passive"))
      (node (ref "R75") (pin "1") (pinfunction "1_1") (pintype "passive"))
      (node (ref "R77") (pin "1") (pinfunction "1_1") (pintype "passive"))
      (node (ref "R79") (pin "1") (pinfunction "1_1") (pintype "passive"))
      (node (ref "R81") (pin "1") (pinfunction "1_1") (pintype "passive"))
      (node (ref "R86") (pin "1") (pinfunction "1_1") (pintype "passive"))
      (node (ref "R9") (pin "1") (pinfunction "1_1") (pintype "passive"))
      (node (ref "R92") (pin "1") (pinfunction "1_1") (pintype "passive"))
      (node (ref "U2") (pin "100") (pinfunction "VSS_4_100") (pintype "power_in"))
      (node (ref "U2") (pin "112") (pinfunction "VSS_5_112") (pintype "power_in"))
      (node (ref "U2") (pin "122") (pinfunction "VSS_6_122") (pintype "power_in"))
      (node (ref "U2") (pin "125") (pinfunction "VREFL_125") (pintype "power_in"))
      (node (ref "U2") (pin "128") (pinfunction "AVSS0_128") (pintype "power_in"))
      (node (ref "U2") (pin "141") (pinfunction "VSS_141") (pintype "power_in"))
      (node (ref "U2") (pin "18") (pinfunction "VSS_2_18") (pintype "power_in"))
      (node (ref "U2") (pin "48") (pinfunction "VSS_3_48") (pintype "power_in"))
      (node (ref "U2") (pin "67") (pinfunction "VSS_67") (pintype "power_in"))
      (node (ref "U2") (pin "82") (pinfunction "VSS_2_82") (pintype "power_in"))
      (node (ref "U2") (pin "91") (pinfunction "VSS_3_91") (pintype "power_in"))
      (node (ref "V2") (pin "1") (pinfunction "1_1") (pintype "passive"))
      (node (ref "V3") (pin "1") (pinfunction "1_1") (pintype "passive"))
      (node (ref "V6") (pin "1") (pinfunction "1_1") (pintype "passive"))
      (node (ref "V7") (pin "1") (pinfunction "1_1") (pintype "passive"))
      (node (ref "V8") (pin "1") (pinfunction "1_1") (pintype "passive"))
      (node (ref "X1") (pin "2") (pinfunction "2_2") (pintype "bidirectional"))
      (node (ref "X11") (pin "2") (pinfunction "2_2") (pintype "bidirectional"))
      (node (ref "X13") (pin "16") (pinfunction "S_16") (pintype "passive"))
      (node (ref "X2") (pin "3") (pinfunction "3_3") (pintype "bidirectional"))
      (node (ref "X2") (pin "5") (pinfunction "5_5") (pintype "bidirectional"))
      (node (ref "X2") (pin "9") (pinfunction "9_9") (pintype "bidirectional"))
      (node (ref "X3") (pin "2") (pinfunction "2_2") (pintype "bidirectional"))
      (node (ref "X4") (pin "2") (pinfunction "2_2") (pintype "bidirectional"))
    )
    (net (code "38") (name "MAINS_L") (class "Default")
      (node (ref "F1") (pin "1") (pinfunction "P$1_1") (pintype "bidirectional"))
      (node (ref "X10") (pin "1") (pinfunction "1_1") (pintype "passive"))
      (node (ref "X10") (pin "1-2") (pinfunction "1_1-2") (pintype "passive"))
    )
    (net (code "39") (name "MAINS_L_F") (class "Default")
      (node (ref "C1") (pin "1") (pinfunction "1_1") (pintype "passive"))
      (node (ref "F1") (pin "2") (pinfunction "P$2_2") (pintype "bidirectional"))
      (node (ref "K1") (pin "P$4") (pinfunction "4_P$4") (pintype "passive"))
      (node (ref "K2") (pin "P$4") (pinfunction "4_P$4") (pintype "passive"))
      (node (ref "R6") (pin "2") (pinfunction "2_2") (pintype "passive"))
      (node (ref "V1") (pin "2") (pinfunction "2_2") (pintype "passive"))
      (node (ref "V4") (pin "1") (pinfunction "1_1") (pintype "passive"))
      (node (ref "V5") (pin "1") (pinfunction "1_1") (pintype "passive"))
    )
    (net (code "40") (name "MAINS_N") (class "Default")
      (node (ref "C1") (pin "2") (pinfunction "2_2") (pintype "passive"))
      (node (ref "C2") (pin "P$2") (pinfunction "2_P$2") (pintype "passive"))
      (node (ref "R7") (pin "1") (pinfunction "1_1") (pintype "passive"))
      (node (ref "R8") (pin "2") (pinfunction "2_2") (pintype "passive"))
      (node (ref "V1") (pin "1") (pinfunction "1_1") (pintype "passive"))
      (node (ref "X5") (pin "1") (pinfunction "1_1") (pintype "passive"))
      (node (ref "X5") (pin "1-2") (pinfunction "1_1-2") (pintype "passive"))
      (node (ref "X6") (pin "1") (pinfunction "1_1") (pintype "passive"))
      (node (ref "X6") (pin "1-2") (pinfunction "1_1-2") (pintype "passive"))
      (node (ref "X7") (pin "1") (pinfunction "1_1") (pintype "passive"))
      (node (ref "X7") (pin "1-2") (pinfunction "1_1-2") (pintype "passive"))
    )
    (net (code "41") (name "NRST") (class "Default")
      (node (ref "C41") (pin "1") (pinfunction "1_1") (pintype "passive"))
      (node (ref "R84") (pin "2") (pinfunction "2_2") (pintype "passive"))
      (node (ref "U2") (pin "55") (pinfunction "RES_55") (pintype "passive"))
      (node (ref "X2") (pin "10") (pinfunction "10_10") (pintype "bidirectional"))
    )
    (net (code "42") (name "Net-(C4-Pad1)") (class "Default")
      (node (ref "C4") (pin "1") (pinfunction "1_1") (pintype "passive"))
      (node (ref "R49") (pin "1") (pinfunction "1_1") (pintype "passive"))
      (node (ref "R50") (pin "1") (pinfunction "1_1") (pintype "passive"))
    )
    (net (code "43") (name "Net-(C5-Pad1)") (class "Default")
      (node (ref "C5") (pin "1") (pinfunction "1_1") (pintype "passive"))
      (node (ref "Q5") (pin "2") (pinfunction "DRAIN_2") (pintype "passive"))
      (node (ref "Q5") (pin "4") (pinfunction "DRAIN_4") (pintype "passive"))
      (node (ref "SW1") (pin "2") (pinfunction "2_2") (pintype "passive"))
    )
    (net (code "44") (name "Net-(D1-C)") (class "Default")
      (node (ref "D1") (pin "1") (pinfunction "C_1") (pintype "passive"))
      (node (ref "K1") (pin "P$2") (pinfunction "2_P$2") (pintype "passive"))
      (node (ref "Q1") (pin "2") (pinfunction "DRAIN_2") (pintype "passive"))
      (node (ref "Q1") (pin "4") (pinfunction "DRAIN_4") (pintype "passive"))
      (node (ref "R1") (pin "2") (pinfunction "2_2") (pintype "passive"))
    )
    (net (code "45") (name "Net-(D2-C)") (class "Default")
      (node (ref "D2") (pin "1") (pinfunction "C_1") (pintype "passive"))
      (node (ref "K2") (pin "P$2") (pinfunction "2_P$2") (pintype "passive"))
      (node (ref "Q3") (pin "2") (pinfunction "DRAIN_2") (pintype "passive"))
      (node (ref "Q3") (pin "4") (pinfunction "DRAIN_4") (pintype "passive"))
      (node (ref "R9") (pin "2") (pinfunction "2_2") (pintype "passive"))
    )
    (net (code "46") (name "Net-(D3-A)") (class "Default")
      (node (ref "D3") (pin "1") (pinfunction "A_1") (pintype "passive"))
      (node (ref "Q5") (pin "1") (pinfunction "GATE_1") (pintype "passive"))
      (node (ref "R17") (pin "2") (pinfunction "2_2") (pintype "passive"))
    )
    (net (code "47") (name "Net-(D12-C)") (class "Default")
      (node (ref "D12") (pin "2") (pinfunction "C_2") (pintype "passive"))
      (node (ref "R86") (pin "2") (pinfunction "2_2") (pintype "passive"))
    )
    (net (code "48") (name "Net-(IC1-D)") (class "Default")
      (node (ref "IC1") (pin "4") (pinfunction "D_4") (pintype "bidirectional"))
      (node (ref "R48") (pin "1") (pinfunction "1_1") (pintype "passive"))
    )
    (net (code "49") (name "Net-(IC1-DE)") (class "Default")
      (node (ref "IC1") (pin "3") (pinfunction "DE_3") (pintype "bidirectional"))
      (node (ref "R47") (pin "1") (pinfunction "1_1") (pintype "passive"))
    )
    (net (code "50") (name "Net-(IC1-R)") (class "Default")
      (node (ref "IC1") (pin "1") (pinfunction "R_1") (pintype "bidirectional"))
      (node (ref "Q10") (pin "2") (pinfunction "E_2") (pintype "passive"))
    )
    (net (code "51") (name "Net-(IC1-{slash}RE)") (class "Default")
      (node (ref "IC1") (pin "2") (pinfunction "/RE_2") (pintype "bidirectional"))
      (node (ref "R16") (pin "1") (pinfunction "1_1") (pintype "passive"))
    )
    (net (code "52") (name "Net-(IC2-INPUT)") (class "Default")
      (node (ref "IC2") (pin "1") (pinfunction "INPUT_1") (pintype "passive"))
      (node (ref "R93") (pin "2") (pinfunction "2_2") (pintype "passive"))
      (node (ref "U2") (pin "20") (pinfunction "P212/EXTAL_20") (pintype "bidirectional"))
    )
    (net (code "53") (name "Net-(IC2-OUTPUT)") (class "Default")
      (node (ref "IC2") (pin "3") (pinfunction "OUTPUT_3") (pintype "passive"))
      (node (ref "R94") (pin "1") (pinfunction "1_1") (pintype "passive"))
    )
    (net (code "54") (name "Net-(IC3-IN-)") (class "Default")
      (node (ref "IC3") (pin "3") (pinfunction "IN-_3") (pintype "bidirectional"))
      (node (ref "R31") (pin "1") (pinfunction "1_1") (pintype "passive"))
    )
    (net (code "55") (name "Net-(IC3-OUT)") (class "Default")
      (node (ref "IC3") (pin "1") (pinfunction "OUT_1") (pintype "bidirectional"))
      (node (ref "R29") (pin "2") (pinfunction "2_2") (pintype "passive"))
      (node (ref "R30") (pin "1") (pinfunction "1_1") (pintype "passive"))
    )
    (net (code "56") (name "Net-(IC3-V+)") (class "Default")
      (node (ref "IC3") (pin "5") (pinfunction "V+_5") (pintype "bidirectional"))
      (node (ref "Q6") (pin "2") (pinfunction "DRAIN_2") (pintype "passive"))
      (node (ref "Q6") (pin "4") (pinfunction "DRAIN_4") (pintype "passive"))
      (node (ref "R28") (pin "1") (pinfunction "1_1") (pintype "passive"))
      (node (ref "R31") (pin "2") (pinfunction "2_2") (pintype "passive"))
    )
    (net (code "57") (name "Net-(IC4-IN-)") (class "Default")
      (node (ref "IC4") (pin "3") (pinfunction "IN-_3") (pintype "bidirectional"))
      (node (ref "R39") (pin "1") (pinfunction "1_1") (pintype "passive"))
    )
    (net (code "58") (name "Net-(IC4-OUT)") (class "Default")
      (node (ref "IC4") (pin "1") (pinfunction "OUT_1") (pintype "bidirectional"))
      (node (ref "R37") (pin "2") (pinfunction "2_2") (pintype "passive"))
      (node (ref "R38") (pin "1") (pinfunction "1_1") (pintype "passive"))
    )
    (net (code "59") (name "Net-(IC4-V+)") (class "Default")
      (node (ref "IC4") (pin "5") (pinfunction "V+_5") (pintype "bidirectional"))
      (node (ref "Q8") (pin "2") (pinfunction "DRAIN_2") (pintype "passive"))
      (node (ref "Q8") (pin "4") (pinfunction "DRAIN_4") (pintype "passive"))
      (node (ref "R36") (pin "1") (pinfunction "1_1") (pintype "passive"))
      (node (ref "R39") (pin "2") (pinfunction "2_2") (pintype "passive"))
    )
    (net (code "60") (name "Net-(IC5-BST)") (class "Default")
      (node (ref "C17") (pin "1") (pinfunction "1_1") (pintype "passive"))
      (node (ref "IC5") (pin "6") (pinfunction "BST_6") (pintype "bidirectional"))
    )
    (net (code "61") (name "Net-(IC5-EN)") (class "Default")
      (node (ref "IC5") (pin "5") (pinfunction "EN_5") (pintype "bidirectional"))
      (node (ref "R43") (pin "1") (pinfunction "1_1") (pintype "passive"))
    )
    (net (code "62") (name "Net-(IC5-FB)") (class "Default")
      (node (ref "IC5") (pin "4") (pinfunction "FB_4") (pintype "bidirectional"))
      (node (ref "R44") (pin "1") (pinfunction "1_1") (pintype "passive"))
      (node (ref "R45") (pin "1") (pinfunction "1_1") (pintype "passive"))
    )
    (net (code "63") (name "Net-(IC5-SW)") (class "Default")
      (node (ref "C17") (pin "2") (pinfunction "2_2") (pintype "passive"))
      (node (ref "IC5") (pin "2") (pinfunction "SW_2") (pintype "bidirectional"))
      (node (ref "L1") (pin "1") (pinfunction "P$1_1") (pintype "bidirectional"))
    )
    (net (code "64") (name "Net-(IC5-VIN)") (class "Default")
      (node (ref "C12") (pin "1") (pinfunction "1_1") (pintype "passive"))
      (node (ref "C13") (pin "1") (pinfunction "1_1") (pintype "passive"))
      (node (ref "IC5") (pin "3") (pinfunction "VIN_3") (pintype "bidirectional"))
      (node (ref "IC8") (pin "2") (pinfunction "OUT_2") (pintype "power_in"))
      (node (ref "IC8") (pin "4") (pinfunction "TAB_4") (pintype "power_in"))
      (node (ref "R43") (pin "2") (pinfunction "2_2") (pintype "passive"))
      (node (ref "R91") (pin "2") (pinfunction "2_2") (pintype "passive"))
    )
    (net (code "65") (name "Net-(IC8-ADJ)") (class "Default")
      (node (ref "IC8") (pin "1") (pinfunction "ADJ_1") (pintype "input"))
      (node (ref "R91") (pin "1") (pinfunction "1_1") (pintype "passive"))
      (node (ref "R92") (pin "2") (pinfunction "2_2") (pintype "passive"))
    )
    (net (code "66") (name "Net-(Q1-GATE)") (class "Default")
      (node (ref "Q1") (pin "1") (pinfunction "GATE_1") (pintype "passive"))
      (node (ref "R2") (pin "1") (pinfunction "1_1") (pintype "passive"))
      (node (ref "R3") (pin "2") (pinfunction "2_2") (pintype "passive"))
    )
    (net (code "67") (name "Net-(Q2-D)") (class "Default")
      (node (ref "Q2") (pin "3") (pinfunction "D_3") (pintype "passive"))
      (node (ref "R3") (pin "1") (pinfunction "1_1") (pintype "passive"))
    )
    (net (code "68") (name "Net-(Q2-G)") (class "Default")
      (node (ref "Q2") (pin "1") (pinfunction "G_1") (pintype "passive"))
      (node (ref "R4") (pin "2") (pinfunction "2_2") (pintype "passive"))
      (node (ref "R5") (pin "1") (pinfunction "1_1") (pintype "passive"))
    )
    (net (code "69") (name "Net-(Q3-GATE)") (class "Default")
      (node (ref "Q3") (pin "1") (pinfunction "GATE_1") (pintype "passive"))
      (node (ref "R10") (pin "1") (pinfunction "1_1") (pintype "passive"))
      (node (ref "R11") (pin "2") (pinfunction "2_2") (pintype "passive"))
    )
    (net (code "70") (name "Net-(Q4-D)") (class "Default")
      (node (ref "Q4") (pin "3") (pinfunction "D_3") (pintype "passive"))
      (node (ref "R11") (pin "1") (pinfunction "1_1") (pintype "passive"))
    )
    (net (code "71") (name "Net-(Q4-G)") (class "Default")
      (node (ref "Q4") (pin "1") (pinfunction "G_1") (pintype "passive"))
      (node (ref "R12") (pin "2") (pinfunction "2_2") (pintype "passive"))
      (node (ref "R13") (pin "1") (pinfunction "1_1") (pintype "passive"))
    )
    (net (code "72") (name "Net-(Q6-GATE)") (class "Default")
      (node (ref "Q6") (pin "1") (pinfunction "GATE_1") (pintype "passive"))
      (node (ref "R24") (pin "1") (pinfunction "1_1") (pintype "passive"))
      (node (ref "R25") (pin "2") (pinfunction "2_2") (pintype "passive"))
    )
    (net (code "73") (name "Net-(Q7-D)") (class "Default")
      (node (ref "Q7") (pin "3") (pinfunction "D_3") (pintype "passive"))
      (node (ref "R25") (pin "1") (pinfunction "1_1") (pintype "passive"))
    )
    (net (code "74") (name "Net-(Q7-G)") (class "Default")
      (node (ref "Q7") (pin "1") (pinfunction "G_1") (pintype "passive"))
      (node (ref "R26") (pin "2") (pinfunction "2_2") (pintype "passive"))
      (node (ref "R27") (pin "1") (pinfunction "1_1") (pintype "passive"))
    )
    (net (code "75") (name "Net-(Q8-GATE)") (class "Default")
      (node (ref "Q8") (pin "1") (pinfunction "GATE_1") (pintype "passive"))
      (node (ref "R32") (pin "1") (pinfunction "1_1") (pintype "passive"))
      (node (ref "R33") (pin "2") (pinfunction "2_2") (pintype "passive"))
    )
    (net (code "76") (name "Net-(Q9-D)") (class "Default")
      (node (ref "Q9") (pin "3") (pinfunction "D_3") (pintype "passive"))
      (node (ref "R33") (pin "1") (pinfunction "1_1") (pintype "passive"))
    )
    (net (code "77") (name "Net-(Q9-G)") (class "Default")
      (node (ref "Q9") (pin "1") (pinfunction "G_1") (pintype "passive"))
      (node (ref "R34") (pin "2") (pinfunction "2_2") (pintype "passive"))
      (node (ref "R35") (pin "1") (pinfunction "1_1") (pintype "passive"))
    )
    (net (code "78") (name "Net-(Q10-B)") (class "Default")
      (node (ref "Q10") (pin "1") (pinfunction "B_1") (pintype "passive"))
      (node (ref "R14") (pin "1") (pinfunction "1_1") (pintype "passive"))
    )
    (net (code "79") (name "Net-(Q11-D)") (class "Default")
      (node (ref "Q11") (pin "3") (pinfunction "D_3") (pintype "passive"))
      (node (ref "R58") (pin "1") (pinfunction "1_1") (pintype "passive"))
    )
    (net (code "80") (name "Net-(Q11-G)") (class "Default")
      (node (ref "Q11") (pin "1") (pinfunction "G_1") (pintype "passive"))
      (node (ref "R56") (pin "2") (pinfunction "2_2") (pintype "passive"))
      (node (ref "R57") (pin "2") (pinfunction "2_2") (pintype "passive"))
    )
    (net (code "81") (name "Net-(Q12-GATE)") (class "Default")
      (node (ref "Q12") (pin "1") (pinfunction "GATE_1") (pintype "passive"))
      (node (ref "R58") (pin "2") (pinfunction "2_2") (pintype "passive"))
      (node (ref "R59") (pin "1") (pinfunction "1_1") (pintype "passive"))
    )
    (net (code "82") (name "Net-(Q13-D)") (class "Default")
      (node (ref "Q13") (pin "3") (pinfunction "D_3") (pintype "passive"))
      (node (ref "R62") (pin "1") (pinfunction "1_1") (pintype "passive"))
    )
    (net (code "83") (name "Net-(Q13-G)") (class "Default")
      (node (ref "Q13") (pin "1") (pinfunction "G_1") (pintype "passive"))
      (node (ref "R60") (pin "2") (pinfunction "2_2") (pintype "passive"))
      (node (ref "R61") (pin "2") (pinfunction "2_2") (pintype "passive"))
    )
    (net (code "84") (name "Net-(Q14-GATE)") (class "Default")
      (node (ref "Q14") (pin "1") (pinfunction "GATE_1") (pintype "passive"))
      (node (ref "R62") (pin "2") (pinfunction "2_2") (pintype "passive"))
      (node (ref "R63") (pin "1") (pinfunction "1_1") (pintype "passive"))
    )
    (net (code "85") (name "Net-(Q15-D)") (class "Default")
      (node (ref "Q15") (pin "3") (pinfunction "D_3") (pintype "passive"))
      (node (ref "R66") (pin "1") (pinfunction "1_1") (pintype "passive"))
    )
    (net (code "86") (name "Net-(Q15-G)") (class "Default")
      (node (ref "Q15") (pin "1") (pinfunction "G_1") (pintype "passive"))
      (node (ref "R64") (pin "2") (pinfunction "2_2") (pintype "passive"))
      (node (ref "R65") (pin "2") (pinfunction "2_2") (pintype "passive"))
    )
    (net (code "87") (name "Net-(Q16-GATE)") (class "Default")
      (node (ref "Q16") (pin "1") (pinfunction "GATE_1") (pintype "passive"))
      (node (ref "R66") (pin "2") (pinfunction "2_2") (pintype "passive"))
      (node (ref "R67") (pin "1") (pinfunction "1_1") (pintype "passive"))
    )
    (net (code "88") (name "Net-(Q17-B)") (class "Default")
      (node (ref "Q17") (pin "1") (pinfunction "B_1") (pintype "passive"))
      (node (ref "R70") (pin "2") (pinfunction "2_2") (pintype "passive"))
    )
    (net (code "89") (name "Net-(Q17-E)") (class "Default")
      (node (ref "Q17") (pin "2") (pinfunction "E_2") (pintype "passive"))
      (node (ref "R69") (pin "2") (pinfunction "2_2") (pintype "passive"))
    )
    (net (code "90") (name "Net-(Q18-B)") (class "Default")
      (node (ref "Q18") (pin "1") (pinfunction "B_1") (pintype "passive"))
      (node (ref "R72") (pin "2") (pinfunction "2_2") (pintype "passive"))
    )
    (net (code "91") (name "Net-(Q18-E)") (class "Default")
      (node (ref "Q18") (pin "2") (pinfunction "E_2") (pintype "passive"))
      (node (ref "R71") (pin "2") (pinfunction "2_2") (pintype "passive"))
    )
    (net (code "92") (name "Net-(Q19-B)") (class "Default")
      (node (ref "Q19") (pin "1") (pinfunction "B_1") (pintype "passive"))
      (node (ref "R74") (pin "2") (pinfunction "2_2") (pintype "passive"))
    )
    (net (code "93") (name "Net-(Q19-E)") (class "Default")
      (node (ref "Q19") (pin "2") (pinfunction "E_2") (pintype "passive"))
      (node (ref "R73") (pin "2") (pinfunction "2_2") (pintype "passive"))
    )
    (net (code "94") (name "Net-(Q20-B)") (class "Default")
      (node (ref "Q20") (pin "1") (pinfunction "B_1") (pintype "passive"))
      (node (ref "R76") (pin "2") (pinfunction "2_2") (pintype "passive"))
    )
    (net (code "95") (name "Net-(Q20-E)") (class "Default")
      (node (ref "Q20") (pin "2") (pinfunction "E_2") (pintype "passive"))
      (node (ref "R75") (pin "2") (pinfunction "2_2") (pintype "passive"))
    )
    (net (code "96") (name "Net-(Q21-B)") (class "Default")
      (node (ref "Q21") (pin "1") (pinfunction "B_1") (pintype "passive"))
      (node (ref "R78") (pin "2") (pinfunction "2_2") (pintype "passive"))
    )
    (net (code "97") (name "Net-(Q21-E)") (class "Default")
      (node (ref "Q21") (pin "2") (pinfunction "E_2") (pintype "passive"))
      (node (ref "R77") (pin "2") (pinfunction "2_2") (pintype "passive"))
    )
    (net (code "98") (name "Net-(Q22-B)") (class "Default")
      (node (ref "Q22") (pin "1") (pinfunction "B_1") (pintype "passive"))
      (node (ref "R80") (pin "2") (pinfunction "2_2") (pintype "passive"))
    )
    (net (code "99") (name "Net-(Q22-E)") (class "Default")
      (node (ref "Q22") (pin "2") (pinfunction "E_2") (pintype "passive"))
      (node (ref "R79") (pin "2") (pinfunction "2_2") (pintype "passive"))
    )
    (net (code "100") (name "Net-(Q23-B)") (class "Default")
      (node (ref "Q23") (pin "1") (pinfunction "B_1") (pintype "passive"))
      (node (ref "R82") (pin "2") (pinfunction "2_2") (pintype "passive"))
    )
    (net (code "101") (name "Net-(Q23-E)") (class "Default")
      (node (ref "Q23") (pin "2") (pinfunction "E_2") (pintype "passive"))
      (node (ref "R81") (pin "2") (pinfunction "2_2") (pintype "passive"))
    )
    (net (code "102") (name "Net-(R6-Pad1)") (class "Default")
      (node (ref "R6") (pin "1") (pinfunction "1_1") (pintype "passive"))
      (node (ref "R7") (pin "2") (pinfunction "2_2") (pintype "passive"))
    )
    (net (code "103") (name "Net-(R40-Pad1)") (class "Default")
      (node (ref "R40") (pin "1") (pinfunction "1_1") (pintype "passive"))
      (node (ref "R41") (pin "2") (pinfunction "2_2") (pintype "passive"))
      (node (ref "R42") (pin "2") (pinfunction "2_2") (pintype "passive"))
    )
    (net (code "104") (name "Net-(R46-Pad2)") (class "Default")
      (node (ref "R46") (pin "2") (pinfunction "2_2") (pintype "passive"))
      (node (ref "R8") (pin "1") (pinfunction "1_1") (pintype "passive"))
    )
    (net (code "105") (name "Net-(U2A-P213{slash}XTAL)") (class "Default")
      (node (ref "R93") (pin "1") (pinfunction "1_1") (pintype "passive"))
      (node (ref "R94") (pin "2") (pinfunction "2_2") (pintype "passive"))
      (node (ref "U2") (pin "19") (pinfunction "P213/XTAL_19") (pintype "bidirectional"))
    )
    (net (code "106") (name "Net-(U2A-VCL0)") (class "Default")
      (node (ref "C51") (pin "2") (pinfunction "2_2") (pintype "passive"))
      (node (ref "U2") (pin "15") (pinfunction "VCL0_15") (pintype "power_in"))
    )
    (net (code "107") (name "Net-(U2B-VCL)") (class "Default")
      (node (ref "C57") (pin "2") (pinfunction "2_2") (pintype "passive"))
      (node (ref "U2") (pin "92") (pinfunction "VCL_92") (pintype "power_in"))
    )
    (net (code "108") (name "Net-(X13D-S)") (class "Default")
      (node (ref "R87") (pin "1") (pinfunction "1_1") (pintype "passive"))
      (node (ref "X13") (pin "12") (pinfunction "S_12") (pintype "passive"))
    )
    (net (code "109") (name "Net-(X13E-S)") (class "Default")
      (node (ref "R88") (pin "1") (pinfunction "1_1") (pintype "passive"))
      (node (ref "X13") (pin "13") (pinfunction "S_13") (pintype "passive"))
    )
    (net (code "110") (name "Net-(X13F-S)") (class "Default")
      (node (ref "R89") (pin "1") (pinfunction "1_1") (pintype "passive"))
      (node (ref "X13") (pin "14") (pinfunction "S_14") (pintype "passive"))
    )
    (net (code "111") (name "Net-(X13G-S)") (class "Default")
      (node (ref "R90") (pin "1") (pinfunction "1_1") (pintype "passive"))
      (node (ref "X13") (pin "15") (pinfunction "S_15") (pintype "passive"))
    )
    (net (code "112") (name "PH_PUMP_MAINS_L_SW") (class "Default")
      (node (ref "K1") (pin "P$3") (pinfunction "3_P$3") (pintype "passive"))
      (node (ref "V4") (pin "2") (pinfunction "2_2") (pintype "passive"))
      (node (ref "X8") (pin "1") (pinfunction "1_1") (pintype "passive"))
      (node (ref "X8") (pin "1-2") (pinfunction "1_1-2") (pintype "passive"))
    )
    (net (code "113") (name "RS485_A") (class "Default")
      (node (ref "IC1") (pin "6") (pinfunction "A_6") (pintype "bidirectional"))
      (node (ref "R50") (pin "2") (pinfunction "2_2") (pintype "passive"))
      (node (ref "R55") (pin "1") (pinfunction "1_1") (pintype "passive"))
      (node (ref "V2") (pin "2") (pinfunction "2_2") (pintype "passive"))
      (node (ref "X12") (pin "1") (pinfunction "1_1") (pintype "passive"))
    )
    (net (code "114") (name "RS485_A_NEXT") (class "Default")
      (node (ref "R55") (pin "2") (pinfunction "2_2") (pintype "passive"))
      (node (ref "X14") (pin "1") (pinfunction "1_1") (pintype "passive"))
    )
    (net (code "115") (name "RS485_B") (class "Default")
      (node (ref "IC1") (pin "7") (pinfunction "B_7") (pintype "bidirectional"))
      (node (ref "R49") (pin "2") (pinfunction "2_2") (pintype "passive"))
      (node (ref "R53") (pin "1") (pinfunction "1_1") (pintype "passive"))
      (node (ref "V3") (pin "2") (pinfunction "2_2") (pintype "passive"))
      (node (ref "X12") (pin "2") (pinfunction "2_2") (pintype "passive"))
    )
    (net (code "116") (name "RS485_B_NEXT") (class "Default")
      (node (ref "R53") (pin "2") (pinfunction "2_2") (pintype "passive"))
      (node (ref "X14") (pin "2") (pinfunction "2_2") (pintype "passive"))
    )
    (net (code "117") (name "V5V0_ESP32") (class "Default")
      (node (ref "C36") (pin "1") (pinfunction "1_1") (pintype "passive"))
      (node (ref "C39") (pin "1") (pinfunction "1_1") (pintype "passive"))
      (node (ref "J1") (pin "J3_20") (pinfunction "EXT_5V_J3_20") (pintype "power_in"))
      (node (ref "R85") (pin "1") (pinfunction "1_1") (pintype "passive"))
    )
    (net (code "118") (name "VBATT") (class "Default")
      (node (ref "U2") (pin "14") (pinfunction "VBATT_14") (pintype "power_in"))
    )
    (net (code "119") (name "VCC") (class "Default")
      (node (ref "C22") (pin "1") (pinfunction "1_1") (pintype "passive"))
      (node (ref "C23") (pin "1") (pinfunction "1_1") (pintype "passive"))
      (node (ref "C3") (pin "1") (pinfunction "1_1") (pintype "passive"))
      (node (ref "C37") (pin "1") (pinfunction "1_1") (pintype "passive"))
      (node (ref "C38") (pin "1") (pinfunction "1_1") (pintype "passive"))
      (node (ref "C40") (pin "1") (pinfunction "1_1") (pintype "passive"))
      (node (ref "C44") (pin "1") (pinfunction "1_1") (pintype "passive"))
      (node (ref "C50") (pin "2") (pinfunction "2_2") (pintype "passive"))
      (node (ref "C53") (pin "2") (pinfunction "2_2") (pintype "passive"))
      (node (ref "C55") (pin "2") (pinfunction "2_2") (pintype "passive"))
      (node (ref "C56") (pin "2") (pinfunction "2_2") (pintype "passive"))
      (node (ref "C58") (pin "2") (pinfunction "2_2") (pintype "passive"))
      (node (ref "C59") (pin "2") (pinfunction "2_2") (pintype "passive"))
      (node (ref "C60") (pin "2") (pinfunction "2_2") (pintype "passive"))
      (node (ref "C61") (pin "2") (pinfunction "2_2") (pintype "passive"))
      (node (ref "C62") (pin "2") (pinfunction "2_2") (pintype "passive"))
      (node (ref "C63") (pin "2") (pinfunction "2_2") (pintype "passive"))
      (node (ref "C64") (pin "2") (pinfunction "2_2") (pintype "passive"))
      (node (ref "C65") (pin "2") (pinfunction "2_2") (pintype "passive"))
      (node (ref "C66") (pin "2") (pinfunction "2_2") (pintype "passive"))
      (node (ref "C67") (pin "2") (pinfunction "2_2") (pintype "passive"))
      (node (ref "C68") (pin "2") (pinfunction "2_2") (pintype "passive"))
      (node (ref "D10") (pin "2") (pinfunction "C2_2") (pintype "passive"))
      (node (ref "D11") (pin "2") (pinfunction "A_2") (pintype "passive"))
      (node (ref "D12") (pin "1") (pinfunction "A_1") (pintype "passive"))
      (node (ref "D13") (pin "2") (pinfunction "C2_2") (pintype "passive"))
      (node (ref "D5") (pin "2") (pinfunction "C2_2") (pintype "passive"))
      (node (ref "D7") (pin "2") (pinfunction "C2_2") (pintype "passive"))
      (node (ref "D8") (pin "2") (pinfunction "C2_2") (pintype "passive"))
      (node (ref "D9") (pin "2") (pinfunction "C2_2") (pintype "passive"))
      (node (ref "IC6") (pin "2") (pinfunction "1_VOUT_2") (pintype "power_in"))
      (node (ref "IC6") (pin "4") (pinfunction "2_VOUT_4") (pintype "power_in"))
      (node (ref "J1") (pin "J2_20") (pinfunction "VDD33_1_J2_20") (pintype "power_in"))
      (node (ref "J1") (pin "J3_18") (pinfunction "VDD33_2_J3_18") (pintype "power_in"))
      (node (ref "R14") (pin "2") (pinfunction "2_2") (pintype "passive"))
      (node (ref "R15") (pin "2") (pinfunction "2_2") (pintype "passive"))
      (node (ref "R54") (pin "2") (pinfunction "2_2") (pintype "passive"))
      (node (ref "R83") (pin "1") (pinfunction "1_1") (pintype "passive"))
      (node (ref "R84") (pin "1") (pinfunction "1_1") (pintype "passive"))
      (node (ref "U2") (pin "111") (pinfunction "VCC_5_111") (pintype "power_in"))
      (node (ref "U2") (pin "121") (pinfunction "VCC_6_121") (pintype "power_in"))
      (node (ref "U2") (pin "126") (pinfunction "VREFH_126") (pintype "power_in"))
      (node (ref "U2") (pin "127") (pinfunction "AVCC0_127") (pintype "power_in"))
      (node (ref "U2") (pin "142") (pinfunction "VCC_142") (pintype "power_in"))
      (node (ref "U2") (pin "21") (pinfunction "VCC_2_21") (pintype "power_in"))
      (node (ref "U2") (pin "49") (pinfunction "VCC_3_49") (pintype "power_in"))
      (node (ref "U2") (pin "68") (pinfunction "VCC_68") (pintype "power_in"))
      (node (ref "U2") (pin "81") (pinfunction "VCC_2_81") (pintype "power_in"))
      (node (ref "U2") (pin "90") (pinfunction "VCC_3_90") (pintype "power_in"))
      (node (ref "U2") (pin "99") (pinfunction "VCC_4_99") (pintype "power_in"))
      (node (ref "X2") (pin "1") (pinfunction "1_1") (pintype "bidirectional"))
    )
    (net (code "120") (name "VCC_CONDUCTIV_SENSOR_SW") (class "Default")
      (node (ref "C8") (pin "1") (pinfunction "1_1") (pintype "passive"))
      (node (ref "IC3") (pin "4") (pinfunction "IN+_4") (pintype "bidirectional"))
      (node (ref "R28") (pin "2") (pinfunction "2_2") (pintype "passive"))
      (node (ref "X3") (pin "1") (pinfunction "1_1") (pintype "bidirectional"))
    )
    (net (code "121") (name "VCC_DISPLAY_2") (class "Default")
      (node (ref "Q16") (pin "2") (pinfunction "DRAIN_2") (pintype "passive"))
      (node (ref "Q16") (pin "4") (pinfunction "DRAIN_4") (pintype "passive"))
      (node (ref "V7") (pin "2") (pinfunction "2_2") (pintype "passive"))
      (node (ref "X13") (pin "9") (pinfunction "S_9") (pintype "passive"))
    )
    (net (code "122") (name "VCC_DISPLAY_3") (class "Default")
      (node (ref "Q12") (pin "2") (pinfunction "DRAIN_2") (pintype "passive"))
      (node (ref "Q12") (pin "4") (pinfunction "DRAIN_4") (pintype "passive"))
      (node (ref "V8") (pin "2") (pinfunction "2_2") (pintype "passive"))
      (node (ref "X13") (pin "10") (pinfunction "S_10") (pintype "passive"))
    )
    (net (code "123") (name "VCC_DSIPLAY_1") (class "Default")
      (node (ref "Q14") (pin "2") (pinfunction "DRAIN_2") (pintype "passive"))
      (node (ref "Q14") (pin "4") (pinfunction "DRAIN_4") (pintype "passive"))
      (node (ref "V6") (pin "2") (pinfunction "2_2") (pintype "passive"))
      (node (ref "X13") (pin "8") (pinfunction "S_8") (pintype "passive"))
    )
    (net (code "124") (name "VCC_PH_SENSOR_SW") (class "Default")
      (node (ref "C10") (pin "1") (pinfunction "1_1") (pintype "passive"))
      (node (ref "IC4") (pin "4") (pinfunction "IN+_4") (pintype "bidirectional"))
      (node (ref "R36") (pin "2") (pinfunction "2_2") (pintype "passive"))
      (node (ref "X4") (pin "1") (pinfunction "1_1") (pintype "bidirectional"))
    )
    (net (code "125") (name "VCC_USBHS") (class "Default")
      (node (ref "U2") (pin "40") (pinfunction "VCC_USBHS_40") (pintype "power_in"))
    )
    (net (code "126") (name "VREFH0") (class "Default")
      (node (ref "U2") (pin "130") (pinfunction "VREFH0_130") (pintype "power_in"))
    )
    (net (code "127") (name "VREFL0") (class "Default")
      (node (ref "U2") (pin "129") (pinfunction "VREFL0_129") (pintype "power_in"))
    )
    (net (code "128") (name "VSS_USB") (class "Default")
      (node (ref "U2") (pin "37") (pinfunction "VSS_USB_37") (pintype "power_in"))
    )
    (net (code "129") (name "V_5V0") (class "Default")
      (node (ref "C14") (pin "1") (pinfunction "1_1") (pintype "passive"))
      (node (ref "C15") (pin "1") (pinfunction "1_1") (pintype "passive"))
      (node (ref "C16") (pin "1") (pinfunction "1_1") (pintype "passive"))
      (node (ref "C20") (pin "1") (pinfunction "1_1") (pintype "passive"))
      (node (ref "C21") (pin "1") (pinfunction "1_1") (pintype "passive"))
      (node (ref "C24") (pin "1") (pinfunction "1_1") (pintype "passive"))
      (node (ref "D11") (pin "1") (pinfunction "C_1") (pintype "passive"))
      (node (ref "IC1") (pin "8") (pinfunction "VCC_8") (pintype "bidirectional"))
      (node (ref "IC6") (pin "3") (pinfunction "VIN_3") (pintype "power_in"))
      (node (ref "L1") (pin "2") (pinfunction "P$2_2") (pintype "bidirectional"))
      (node (ref "R45") (pin "2") (pinfunction "2_2") (pintype "passive"))
      (node (ref "R68") (pin "1") (pinfunction "1_1") (pintype "passive"))
      (node (ref "R85") (pin "2") (pinfunction "2_2") (pintype "passive"))
      (node (ref "X13") (pin "11") (pinfunction "S_11") (pintype "passive"))
    )
    (net (code "130") (name "V_5V0_HMI") (class "Default")
      (node (ref "C26") (pin "2") (pinfunction "2_2") (pintype "passive"))
      (node (ref "C27") (pin "2") (pinfunction "2_2") (pintype "passive"))
      (node (ref "C28") (pin "2") (pinfunction "2_2") (pintype "passive"))
      (node (ref "Q12") (pin "3") (pinfunction "SOURCE_3") (pintype "passive"))
      (node (ref "Q14") (pin "3") (pinfunction "SOURCE_3") (pintype "passive"))
      (node (ref "Q16") (pin "3") (pinfunction "SOURCE_3") (pintype "passive"))
      (node (ref "R59") (pin "2") (pinfunction "2_2") (pintype "passive"))
      (node (ref "R63") (pin "2") (pinfunction "2_2") (pintype "passive"))
      (node (ref "R67") (pin "2") (pinfunction "2_2") (pintype "passive"))
      (node (ref "R68") (pin "2") (pinfunction "2_2") (pintype "passive"))
    )
    (net (code "131") (name "V_24V0") (class "Default")
      (node (ref "C49") (pin "1") (pinfunction "1_1") (pintype "passive"))
      (node (ref "SW1") (pin "1") (pinfunction "1_1") (pintype "passive"))
      (node (ref "X1") (pin "1") (pinfunction "1_1") (pintype "bidirectional"))
    )
    (net (code "132") (name "V_24V0_P") (class "Default")
      (node (ref "C18") (pin "1") (pinfunction "+_1") (pintype "passive"))
      (node (ref "D3") (pin "3") (pinfunction "C_3") (pintype "passive"))
      (node (ref "IC8") (pin "3") (pinfunction "IN_3") (pintype "power_in"))
      (node (ref "Q1") (pin "3") (pinfunction "SOURCE_3") (pintype "passive"))
      (node (ref "Q3") (pin "3") (pinfunction "SOURCE_3") (pintype "passive"))
      (node (ref "Q5") (pin "3") (pinfunction "SOURCE_3") (pintype "passive"))
      (node (ref "Q6") (pin "3") (pinfunction "SOURCE_3") (pintype "passive"))
      (node (ref "Q8") (pin "3") (pinfunction "SOURCE_3") (pintype "passive"))
      (node (ref "R10") (pin "2") (pinfunction "2_2") (pintype "passive"))
      (node (ref "R2") (pin "2") (pinfunction "2_2") (pintype "passive"))
      (node (ref "R24") (pin "2") (pinfunction "2_2") (pintype "passive"))
      (node (ref "R32") (pin "2") (pinfunction "2_2") (pintype "passive"))
      (node (ref "R40") (pin "2") (pinfunction "2_2") (pintype "passive"))
    )
    (net (code "133") (name "V_CONDUCTIV") (class "Default")
      (node (ref "C7") (pin "2") (pinfunction "2_2") (pintype "passive"))
      (node (ref "D6") (pin "2") (pinfunction "C2_2") (pintype "passive"))
      (node (ref "R21") (pin "2") (pinfunction "2_2") (pintype "passive"))
      (node (ref "R22") (pin "2") (pinfunction "2_2") (pintype "passive"))
      (node (ref "X3") (pin "3") (pinfunction "3_3") (pintype "bidirectional"))
    )
    (net (code "134") (name "V_PH") (class "Default")
      (node (ref "C6") (pin "2") (pinfunction "2_2") (pintype "passive"))
      (node (ref "D4") (pin "2") (pinfunction "C2_2") (pintype "passive"))
      (node (ref "R18") (pin "2") (pinfunction "2_2") (pintype "passive"))
      (node (ref "R19") (pin "2") (pinfunction "2_2") (pintype "passive"))
      (node (ref "X4") (pin "3") (pinfunction "3_3") (pintype "bidirectional"))
    )
    (net (code "135") (name "unconnected-(D4-A-Pad3)") (class "Default")
      (node (ref "D4") (pin "3") (pinfunction "A_3") (pintype "passive"))
    )
    (net (code "136") (name "unconnected-(D6-A-Pad3)") (class "Default")
      (node (ref "D6") (pin "3") (pinfunction "A_3") (pintype "passive"))
    )
    (net (code "137") (name "unconnected-(FID1-PadP$1)") (class "Default")
      (node (ref "FID1") (pin "P$1") (pinfunction "P$1_P$1") (pintype "bidirectional"))
    )
    (net (code "138") (name "unconnected-(FID2-PadP$1)") (class "Default")
      (node (ref "FID2") (pin "P$1") (pinfunction "P$1_P$1") (pintype "bidirectional"))
    )
    (net (code "139") (name "unconnected-(H1-MOUNT-PadB3,0)") (class "Default")
      (node (ref "H1") (pin "B3,0") (pinfunction "MOUNT_B3,0") (pintype "passive"))
    )
    (net (code "140") (name "unconnected-(H2-MOUNT-PadB3,0)") (class "Default")
      (node (ref "H2") (pin "B3,0") (pinfunction "MOUNT_B3,0") (pintype "passive"))
    )
    (net (code "141") (name "unconnected-(H3-MOUNT-PadB3,0)") (class "Default")
      (node (ref "H3") (pin "B3,0") (pinfunction "MOUNT_B3,0") (pintype "passive"))
    )
    (net (code "142") (name "unconnected-(H4-MOUNT-PadB3,0)") (class "Default")
      (node (ref "H4") (pin "B3,0") (pinfunction "MOUNT_B3,0") (pintype "passive"))
    )
    (net (code "143") (name "unconnected-(J1-FLASH_CLK-PadJ2_3)") (class "Default")
      (node (ref "J1") (pin "J2_3") (pinfunction "FLASH_CLK_J2_3") (pintype "bidirectional"))
    )
    (net (code "144") (name "unconnected-(J1-FLASH_CS-PadJ3_1)") (class "Default")
      (node (ref "J1") (pin "J3_1") (pinfunction "FLASH_CS_J3_1") (pintype "bidirectional"))
    )
    (net (code "145") (name "unconnected-(J1-FLASH_SD0-PadJ3_2)") (class "Default")
      (node (ref "J1") (pin "J3_2") (pinfunction "FLASH_SD0_J3_2") (pintype "bidirectional"))
    )
    (net (code "146") (name "unconnected-(J1-FLASH_SD1-PadJ2_1)") (class "Default")
      (node (ref "J1") (pin "J2_1") (pinfunction "FLASH_SD1_J2_1") (pintype "bidirectional"))
    )
    (net (code "147") (name "unconnected-(J1-FLASH_SD2-PadJ3_3)") (class "Default")
      (node (ref "J1") (pin "J3_3") (pinfunction "FLASH_SD2_J3_3") (pintype "bidirectional"))
    )
    (net (code "148") (name "unconnected-(J1-FLASH_SD3-PadJ2_2)") (class "Default")
      (node (ref "J1") (pin "J2_2") (pinfunction "FLASH_SD3_J2_2") (pintype "bidirectional"))
    )
    (net (code "149") (name "unconnected-(J1-IO0-PadJ3_17)") (class "Default")
      (node (ref "J1") (pin "J3_17") (pinfunction "IO0_J3_17") (pintype "bidirectional"))
    )
    (net (code "150") (name "unconnected-(J1-IO2-PadJ3_15)") (class "Default")
      (node (ref "J1") (pin "J3_15") (pinfunction "IO2_J3_15") (pintype "bidirectional"))
    )
    (net (code "151") (name "unconnected-(J1-IO4-PadJ3_16)") (class "Default")
      (node (ref "J1") (pin "J3_16") (pinfunction "IO4_J3_16") (pintype "bidirectional"))
    )
    (net (code "152") (name "unconnected-(J1-IO5-PadJ2_9)") (class "Default")
      (node (ref "J1") (pin "J2_9") (pinfunction "IO5_J2_9") (pintype "bidirectional"))
    )
    (net (code "153") (name "unconnected-(J1-IO9-PadJ2_11)") (class "Default")
      (node (ref "J1") (pin "J2_11") (pinfunction "IO9_J2_11") (pintype "bidirectional"))
    )
    (net (code "154") (name "unconnected-(J1-IO10-PadJ2_10)") (class "Default")
      (node (ref "J1") (pin "J2_10") (pinfunction "IO10_J2_10") (pintype "bidirectional"))
    )
    (net (code "155") (name "unconnected-(J1-IO12-PadJ3_12)") (class "Default")
      (node (ref "J1") (pin "J3_12") (pinfunction "IO12_J3_12") (pintype "bidirectional"))
    )
    (net (code "156") (name "unconnected-(J1-IO13-PadJ3_13)") (class "Default")
      (node (ref "J1") (pin "J3_13") (pinfunction "IO13_J3_13") (pintype "bidirectional"))
    )
    (net (code "157") (name "unconnected-(J1-IO14-PadJ3_11)") (class "Default")
      (node (ref "J1") (pin "J3_11") (pinfunction "IO14_J3_11") (pintype "bidirectional"))
    )
    (net (code "158") (name "unconnected-(J1-IO15-PadJ3_14)") (class "Default")
      (node (ref "J1") (pin "J3_14") (pinfunction "IO15_J3_14") (pintype "bidirectional"))
    )
    (net (code "159") (name "unconnected-(J1-IO18-PadJ2_8)") (class "Default")
      (node (ref "J1") (pin "J2_8") (pinfunction "IO18_J2_8") (pintype "bidirectional"))
    )
    (net (code "160") (name "unconnected-(J1-IO19-PadJ2_6)") (class "Default")
      (node (ref "J1") (pin "J2_6") (pinfunction "IO19_J2_6") (pintype "bidirectional"))
    )
    (net (code "161") (name "unconnected-(J1-IO21-PadJ2_4)") (class "Default")
      (node (ref "J1") (pin "J2_4") (pinfunction "IO21_J2_4") (pintype "bidirectional"))
    )
    (net (code "162") (name "unconnected-(J1-IO22-PadJ2_5)") (class "Default")
      (node (ref "J1") (pin "J2_5") (pinfunction "IO22_J2_5") (pintype "bidirectional"))
    )
    (net (code "163") (name "unconnected-(J1-IO23-PadJ2_7)") (class "Default")
      (node (ref "J1") (pin "J2_7") (pinfunction "IO23_J2_7") (pintype "bidirectional"))
    )
    (net (code "164") (name "unconnected-(J1-IO25-PadJ3_6)") (class "Default")
      (node (ref "J1") (pin "J3_6") (pinfunction "IO25_J3_6") (pintype "bidirectional"))
    )
    (net (code "165") (name "unconnected-(J1-IO26-PadJ3_7)") (class "Default")
      (node (ref "J1") (pin "J3_7") (pinfunction "IO26_J3_7") (pintype "bidirectional"))
    )
    (net (code "166") (name "unconnected-(J1-IO27-PadJ3_10)") (class "Default")
      (node (ref "J1") (pin "J3_10") (pinfunction "IO27_J3_10") (pintype "bidirectional"))
    )
    (net (code "167") (name "unconnected-(J1-IO32-PadJ3_8)") (class "Default")
      (node (ref "J1") (pin "J3_8") (pinfunction "IO32_J3_8") (pintype "bidirectional"))
    )
    (net (code "168") (name "unconnected-(J1-IO33-PadJ3_9)") (class "Default")
      (node (ref "J1") (pin "J3_9") (pinfunction "IO33_J3_9") (pintype "bidirectional"))
    )
    (net (code "169") (name "unconnected-(J1-IO34-PadJ2_15)") (class "Default")
      (node (ref "J1") (pin "J2_15") (pinfunction "IO34_J2_15") (pintype "input"))
    )
    (net (code "170") (name "unconnected-(J1-IO35-PadJ2_14)") (class "Default")
      (node (ref "J1") (pin "J2_14") (pinfunction "IO35_J2_14") (pintype "input"))
    )
    (net (code "171") (name "unconnected-(J1-IO37-PadJ2_17)") (class "Default")
      (node (ref "J1") (pin "J2_17") (pinfunction "IO37_J2_17") (pintype "input"))
    )
    (net (code "172") (name "unconnected-(J1-IO38-PadJ2_16)") (class "Default")
      (node (ref "J1") (pin "J2_16") (pinfunction "IO38_J2_16") (pintype "input"))
    )
    (net (code "173") (name "unconnected-(J1-SENSOR_VN-PadJ3_5)") (class "Default")
      (node (ref "J1") (pin "J3_5") (pinfunction "SENSOR_VN_J3_5") (pintype "input"))
    )
    (net (code "174") (name "unconnected-(J1-SENSOR_VP-PadJ3_4)") (class "Default")
      (node (ref "J1") (pin "J3_4") (pinfunction "SENSOR_VP_J3_4") (pintype "input"))
    )
    (net (code "175") (name "unconnected-(U2A-P200-Pad57)") (class "Default")
      (node (ref "U2") (pin "57") (pinfunction "P200_57") (pintype "bidirectional"))
    )
    (net (code "176") (name "unconnected-(U2A-P201{slash}MD-Pad56)") (class "Default")
      (node (ref "U2") (pin "56") (pinfunction "P201/MD_56") (pintype "bidirectional"))
    )
    (net (code "177") (name "unconnected-(U2A-P202-Pad46)") (class "Default")
      (node (ref "U2") (pin "46") (pinfunction "P202_46") (pintype "bidirectional"))
    )
    (net (code "178") (name "unconnected-(U2A-P203-Pad45)") (class "Default")
      (node (ref "U2") (pin "45") (pinfunction "P203_45") (pintype "bidirectional"))
    )
    (net (code "179") (name "unconnected-(U2A-P204-Pad44)") (class "Default")
      (node (ref "U2") (pin "44") (pinfunction "P204_44") (pintype "bidirectional"))
    )
    (net (code "180") (name "unconnected-(U2A-P205-Pad43)") (class "Default")
      (node (ref "U2") (pin "43") (pinfunction "P205_43") (pintype "bidirectional"))
    )
    (net (code "181") (name "unconnected-(U2A-P206-Pad42)") (class "Default")
      (node (ref "U2") (pin "42") (pinfunction "P206_42") (pintype "bidirectional"))
    )
    (net (code "182") (name "unconnected-(U2A-P207-Pad41)") (class "Default")
      (node (ref "U2") (pin "41") (pinfunction "P207_41") (pintype "bidirectional"))
    )
    (net (code "183") (name "unconnected-(U2A-P208-Pad54)") (class "Default")
      (node (ref "U2") (pin "54") (pinfunction "P208_54") (pintype "bidirectional"))
    )
    (net (code "184") (name "unconnected-(U2A-P209-Pad53)") (class "Default")
      (node (ref "U2") (pin "53") (pinfunction "P209_53") (pintype "bidirectional"))
    )
    (net (code "185") (name "unconnected-(U2A-P210-Pad52)") (class "Default")
      (node (ref "U2") (pin "52") (pinfunction "P210_52") (pintype "bidirectional"))
    )
    (net (code "186") (name "unconnected-(U2A-P211-Pad51)") (class "Default")
      (node (ref "U2") (pin "51") (pinfunction "P211_51") (pintype "bidirectional"))
    )
    (net (code "187") (name "unconnected-(U2A-P214-Pad50)") (class "Default")
      (node (ref "U2") (pin "50") (pinfunction "P214_50") (pintype "bidirectional"))
    )
    (net (code "188") (name "unconnected-(U2A-P304-Pad66)") (class "Default")
      (node (ref "U2") (pin "66") (pinfunction "P304_66") (pintype "bidirectional"))
    )
    (net (code "189") (name "unconnected-(U2A-P305-Pad65)") (class "Default")
      (node (ref "U2") (pin "65") (pinfunction "P305_65") (pintype "bidirectional"))
    )
    (net (code "190") (name "unconnected-(U2A-P306-Pad64)") (class "Default")
      (node (ref "U2") (pin "64") (pinfunction "P306_64") (pintype "bidirectional"))
    )
    (net (code "191") (name "unconnected-(U2A-P307-Pad63)") (class "Default")
      (node (ref "U2") (pin "63") (pinfunction "P307_63") (pintype "bidirectional"))
    )
    (net (code "192") (name "unconnected-(U2A-P308-Pad62)") (class "Default")
      (node (ref "U2") (pin "62") (pinfunction "P308_62") (pintype "bidirectional"))
    )
    (net (code "193") (name "unconnected-(U2A-P309-Pad61)") (class "Default")
      (node (ref "U2") (pin "61") (pinfunction "P309_61") (pintype "bidirectional"))
    )
    (net (code "194") (name "unconnected-(U2A-P310-Pad60)") (class "Default")
      (node (ref "U2") (pin "60") (pinfunction "P310_60") (pintype "bidirectional"))
    )
    (net (code "195") (name "unconnected-(U2A-P311-Pad59)") (class "Default")
      (node (ref "U2") (pin "59") (pinfunction "P311_59") (pintype "bidirectional"))
    )
    (net (code "196") (name "unconnected-(U2A-P312-Pad58)") (class "Default")
      (node (ref "U2") (pin "58") (pinfunction "P312_58") (pintype "bidirectional"))
    )
    (net (code "197") (name "unconnected-(U2A-P313-Pad47)") (class "Default")
      (node (ref "U2") (pin "47") (pinfunction "P313_47") (pintype "bidirectional"))
    )
    (net (code "198") (name "unconnected-(U2A-P407-Pad36)") (class "Default")
      (node (ref "U2") (pin "36") (pinfunction "P407_36") (pintype "bidirectional"))
    )
    (net (code "199") (name "unconnected-(U2A-P413-Pad30)") (class "Default")
      (node (ref "U2") (pin "30") (pinfunction "P413_30") (pintype "bidirectional"))
    )
    (net (code "200") (name "unconnected-(U2A-P414-Pad29)") (class "Default")
      (node (ref "U2") (pin "29") (pinfunction "P414_29") (pintype "bidirectional"))
    )
    (net (code "201") (name "unconnected-(U2A-P415-Pad28)") (class "Default")
      (node (ref "U2") (pin "28") (pinfunction "P415_28") (pintype "bidirectional"))
    )
    (net (code "202") (name "unconnected-(U2A-P703-Pad11)") (class "Default")
      (node (ref "U2") (pin "11") (pinfunction "P703_11") (pintype "bidirectional"))
    )
    (net (code "203") (name "unconnected-(U2A-P704-Pad12)") (class "Default")
      (node (ref "U2") (pin "12") (pinfunction "P704_12") (pintype "bidirectional"))
    )
    (net (code "204") (name "unconnected-(U2A-P705-Pad13)") (class "Default")
      (node (ref "U2") (pin "13") (pinfunction "P705_13") (pintype "bidirectional"))
    )
    (net (code "205") (name "unconnected-(U2A-P708-Pad27)") (class "Default")
      (node (ref "U2") (pin "27") (pinfunction "P708_27") (pintype "bidirectional"))
    )
    (net (code "206") (name "unconnected-(U2A-P709-Pad26)") (class "Default")
      (node (ref "U2") (pin "26") (pinfunction "P709_26") (pintype "bidirectional"))
    )
    (net (code "207") (name "unconnected-(U2A-P710-Pad25)") (class "Default")
      (node (ref "U2") (pin "25") (pinfunction "P710_25") (pintype "bidirectional"))
    )
    (net (code "208") (name "unconnected-(U2A-P711-Pad24)") (class "Default")
      (node (ref "U2") (pin "24") (pinfunction "P711_24") (pintype "bidirectional"))
    )
    (net (code "209") (name "unconnected-(U2A-P712-Pad23)") (class "Default")
      (node (ref "U2") (pin "23") (pinfunction "P712_23") (pintype "bidirectional"))
    )
    (net (code "210") (name "unconnected-(U2A-P713-Pad22)") (class "Default")
      (node (ref "U2") (pin "22") (pinfunction "P713_22") (pintype "bidirectional"))
    )
    (net (code "211") (name "unconnected-(U2A-USB_DM-Pad38)") (class "Default")
      (node (ref "U2") (pin "38") (pinfunction "USB_DM_38") (pintype "bidirectional"))
    )
    (net (code "212") (name "unconnected-(U2A-USB_DP-Pad39)") (class "Default")
      (node (ref "U2") (pin "39") (pinfunction "USB_DP_39") (pintype "bidirectional"))
    )
    (net (code "213") (name "unconnected-(U2A-XCIN-Pad16)") (class "Default")
      (node (ref "U2") (pin "16") (pinfunction "XCIN_16") (pintype "input"))
    )
    (net (code "214") (name "unconnected-(U2A-XCOUT-Pad17)") (class "Default")
      (node (ref "U2") (pin "17") (pinfunction "XCOUT_17") (pintype "output"))
    )
    (net (code "215") (name "unconnected-(U2B-P000-Pad140)") (class "Default")
      (node (ref "U2") (pin "140") (pinfunction "P000_140") (pintype "bidirectional"))
    )
    (net (code "216") (name "unconnected-(U2B-P001-Pad139)") (class "Default")
      (node (ref "U2") (pin "139") (pinfunction "P001_139") (pintype "bidirectional"))
    )
    (net (code "217") (name "unconnected-(U2B-P002-Pad138)") (class "Default")
      (node (ref "U2") (pin "138") (pinfunction "P002_138") (pintype "bidirectional"))
    )
    (net (code "218") (name "unconnected-(U2B-P003-Pad137)") (class "Default")
      (node (ref "U2") (pin "137") (pinfunction "P003_137") (pintype "bidirectional"))
    )
    (net (code "219") (name "unconnected-(U2B-P004-Pad136)") (class "Default")
      (node (ref "U2") (pin "136") (pinfunction "P004_136") (pintype "bidirectional"))
    )
    (net (code "220") (name "unconnected-(U2B-P005-Pad135)") (class "Default")
      (node (ref "U2") (pin "135") (pinfunction "P005_135") (pintype "bidirectional"))
    )
    (net (code "221") (name "unconnected-(U2B-P006-Pad134)") (class "Default")
      (node (ref "U2") (pin "134") (pinfunction "P006_134") (pintype "bidirectional"))
    )
    (net (code "222") (name "unconnected-(U2B-P007-Pad133)") (class "Default")
      (node (ref "U2") (pin "133") (pinfunction "P007_133") (pintype "bidirectional"))
    )
    (net (code "223") (name "unconnected-(U2B-P008-Pad132)") (class "Default")
      (node (ref "U2") (pin "132") (pinfunction "P008_132") (pintype "bidirectional"))
    )
    (net (code "224") (name "unconnected-(U2B-P009-Pad131)") (class "Default")
      (node (ref "U2") (pin "131") (pinfunction "P009_131") (pintype "bidirectional"))
    )
    (net (code "225") (name "unconnected-(U2B-P014-Pad124)") (class "Default")
      (node (ref "U2") (pin "124") (pinfunction "P014_124") (pintype "bidirectional"))
    )
    (net (code "226") (name "unconnected-(U2B-P015-Pad123)") (class "Default")
      (node (ref "U2") (pin "123") (pinfunction "P015_123") (pintype "bidirectional"))
    )
    (net (code "227") (name "unconnected-(U2B-P106-Pad102)") (class "Default")
      (node (ref "U2") (pin "102") (pinfunction "P106_102") (pintype "bidirectional"))
    )
    (net (code "228") (name "unconnected-(U2B-P107-Pad101)") (class "Default")
      (node (ref "U2") (pin "101") (pinfunction "P107_101") (pintype "bidirectional"))
    )
    (net (code "229") (name "unconnected-(U2B-P112-Pad77)") (class "Default")
      (node (ref "U2") (pin "77") (pinfunction "P112_77") (pintype "bidirectional"))
    )
    (net (code "230") (name "unconnected-(U2B-P113-Pad78)") (class "Default")
      (node (ref "U2") (pin "78") (pinfunction "P113_78") (pintype "bidirectional"))
    )
    (net (code "231") (name "unconnected-(U2B-P114-Pad79)") (class "Default")
      (node (ref "U2") (pin "79") (pinfunction "P114_79") (pintype "bidirectional"))
    )
    (net (code "232") (name "unconnected-(U2B-P115-Pad80)") (class "Default")
      (node (ref "U2") (pin "80") (pinfunction "P115_80") (pintype "bidirectional"))
    )
    (net (code "233") (name "unconnected-(U2B-P505-Pad118)") (class "Default")
      (node (ref "U2") (pin "118") (pinfunction "P505_118") (pintype "bidirectional"))
    )
    (net (code "234") (name "unconnected-(U2B-P506-Pad119)") (class "Default")
      (node (ref "U2") (pin "119") (pinfunction "P506_119") (pintype "bidirectional"))
    )
    (net (code "235") (name "unconnected-(U2B-P507-Pad120)") (class "Default")
      (node (ref "U2") (pin "120") (pinfunction "P507_120") (pintype "bidirectional"))
    )
    (net (code "236") (name "unconnected-(U2B-P511-Pad144)") (class "Default")
      (node (ref "U2") (pin "144") (pinfunction "P511_144") (pintype "bidirectional"))
    )
    (net (code "237") (name "unconnected-(U2B-P512-Pad143)") (class "Default")
      (node (ref "U2") (pin "143") (pinfunction "P512_143") (pintype "bidirectional"))
    )
    (net (code "238") (name "unconnected-(U2B-P600-Pad98)") (class "Default")
      (node (ref "U2") (pin "98") (pinfunction "P600_98") (pintype "bidirectional"))
    )
    (net (code "239") (name "unconnected-(U2B-P601-Pad97)") (class "Default")
      (node (ref "U2") (pin "97") (pinfunction "P601_97") (pintype "bidirectional"))
    )
    (net (code "240") (name "unconnected-(U2B-P602-Pad96)") (class "Default")
      (node (ref "U2") (pin "96") (pinfunction "P602_96") (pintype "bidirectional"))
    )
    (net (code "241") (name "unconnected-(U2B-P603-Pad95)") (class "Default")
      (node (ref "U2") (pin "95") (pinfunction "P603_95") (pintype "bidirectional"))
    )
    (net (code "242") (name "unconnected-(U2B-P604-Pad94)") (class "Default")
      (node (ref "U2") (pin "94") (pinfunction "P604_94") (pintype "bidirectional"))
    )
    (net (code "243") (name "unconnected-(U2B-P605-Pad93)") (class "Default")
      (node (ref "U2") (pin "93") (pinfunction "P605_93") (pintype "bidirectional"))
    )
    (net (code "244") (name "unconnected-(U2B-P608-Pad83)") (class "Default")
      (node (ref "U2") (pin "83") (pinfunction "P608_83") (pintype "bidirectional"))
    )
    (net (code "245") (name "unconnected-(U2B-P609-Pad84)") (class "Default")
      (node (ref "U2") (pin "84") (pinfunction "P609_84") (pintype "bidirectional"))
    )
    (net (code "246") (name "unconnected-(U2B-P610-Pad85)") (class "Default")
      (node (ref "U2") (pin "85") (pinfunction "P610_85") (pintype "bidirectional"))
    )
    (net (code "247") (name "unconnected-(U2B-P611-Pad86)") (class "Default")
      (node (ref "U2") (pin "86") (pinfunction "P611_86") (pintype "bidirectional"))
    )
    (net (code "248") (name "unconnected-(U2B-P612-Pad87)") (class "Default")
      (node (ref "U2") (pin "87") (pinfunction "P612_87") (pintype "bidirectional"))
    )
    (net (code "249") (name "unconnected-(U2B-P613-Pad88)") (class "Default")
      (node (ref "U2") (pin "88") (pinfunction "P613_88") (pintype "bidirectional"))
    )
    (net (code "250") (name "unconnected-(U2B-P614-Pad89)") (class "Default")
      (node (ref "U2") (pin "89") (pinfunction "P614_89") (pintype "bidirectional"))
    )
    (net (code "251") (name "unconnected-(U2B-P800-Pad109)") (class "Default")
      (node (ref "U2") (pin "109") (pinfunction "P800_109") (pintype "bidirectional"))
    )
    (net (code "252") (name "unconnected-(U2B-P801-Pad110)") (class "Default")
      (node (ref "U2") (pin "110") (pinfunction "P801_110") (pintype "bidirectional"))
    )
    (net (code "253") (name "unconnected-(X2-Pad7)") (class "Default")
      (node (ref "X2") (pin "7") (pinfunction "7_7") (pintype "bidirectional"))
    )
    (net (code "254") (name "unconnected-(X2-Pad8)") (class "Default")
      (node (ref "X2") (pin "8") (pinfunction "8_8") (pintype "bidirectional"))
    )
    (net (code "255") (name "unconnected-(X12-Pad3)") (class "Default")
      (node (ref "X12") (pin "3") (pinfunction "3_3") (pintype "passive"))
    )
    (net (code "256") (name "unconnected-(X12-Pad4)") (class "Default")
      (node (ref "X12") (pin "4") (pinfunction "4_4") (pintype "passive"))
    )
    (net (code "257") (name "unconnected-(X12-Pad5)") (class "Default")
      (node (ref "X12") (pin "5") (pinfunction "5_5") (pintype "passive"))
    )
    (net (code "258") (name "unconnected-(X12-Pad6)") (class "Default")
      (node (ref "X12") (pin "6") (pinfunction "6_6") (pintype "passive"))
    )
    (net (code "259") (name "unconnected-(X12-Pad7)") (class "Default")
      (node (ref "X12") (pin "7") (pinfunction "7_7") (pintype "passive"))
    )
    (net (code "260") (name "unconnected-(X12-Pad8)") (class "Default")
      (node (ref "X12") (pin "8") (pinfunction "8_8") (pintype "passive"))
    )
    (net (code "261") (name "unconnected-(X14-Pad3)") (class "Default")
      (node (ref "X14") (pin "3") (pinfunction "3_3") (pintype "passive"))
    )
    (net (code "262") (name "unconnected-(X14-Pad4)") (class "Default")
      (node (ref "X14") (pin "4") (pinfunction "4_4") (pintype "passive"))
    )
    (net (code "263") (name "unconnected-(X14-Pad5)") (class "Default")
      (node (ref "X14") (pin "5") (pinfunction "5_5") (pintype "passive"))
    )
    (net (code "264") (name "unconnected-(X14-Pad6)") (class "Default")
      (node (ref "X14") (pin "6") (pinfunction "6_6") (pintype "passive"))
    )
    (net (code "265") (name "unconnected-(X14-Pad7)") (class "Default")
      (node (ref "X14") (pin "7") (pinfunction "7_7") (pintype "passive"))
    )
    (net (code "266") (name "unconnected-(X14-Pad8)") (class "Default")
      (node (ref "X14") (pin "8") (pinfunction "8_8") (pintype "passive"))
    )
    (net (code "267") (name "{slash}CONDUCTIV_PUMP_LED_ON") (class "Default")
      (node (ref "C35") (pin "2") (pinfunction "2_2") (pintype "passive"))
      (node (ref "Q23") (pin "3") (pinfunction "C_3") (pintype "passive"))
      (node (ref "X13") (pin "3") (pinfunction "S_3") (pintype "passive"))
    )
    (net (code "268") (name "{slash}CONDUCTIV_SENSOR_LED_ON") (class "Default")
      (node (ref "C33") (pin "2") (pinfunction "2_2") (pintype "passive"))
      (node (ref "Q21") (pin "3") (pinfunction "C_3") (pintype "passive"))
      (node (ref "X13") (pin "4") (pinfunction "S_4") (pintype "passive"))
    )
    (net (code "269") (name "{slash}DOSING_DIS") (class "Default")
      (node (ref "C25") (pin "2") (pinfunction "2_2") (pintype "passive"))
      (node (ref "R51") (pin "2") (pinfunction "2_2") (pintype "passive"))
      (node (ref "R52") (pin "2") (pinfunction "2_2") (pintype "passive"))
      (node (ref "X11") (pin "1") (pinfunction "1_1") (pintype "bidirectional"))
    )
    (net (code "270") (name "{slash}DO_COMM_RX_EN") (class "Default")
      (node (ref "R16") (pin "2") (pinfunction "2_2") (pintype "passive"))
      (node (ref "U2") (pin "32") (pinfunction "P411_32") (pintype "bidirectional"))
    )
    (net (code "271") (name "{slash}PH_PUMP_LED_ON") (class "Default")
      (node (ref "C34") (pin "2") (pinfunction "2_2") (pintype "passive"))
      (node (ref "Q22") (pin "3") (pinfunction "C_3") (pintype "passive"))
      (node (ref "X13") (pin "1") (pinfunction "S_1") (pintype "passive"))
    )
    (net (code "272") (name "{slash}PH_SENSOR_LED_ON") (class "Default")
      (node (ref "C32") (pin "2") (pinfunction "2_2") (pintype "passive"))
      (node (ref "Q20") (pin "3") (pinfunction "C_3") (pintype "passive"))
      (node (ref "X13") (pin "2") (pinfunction "S_2") (pintype "passive"))
    )
    (net (code "273") (name "{slash}STATUS_LED_G") (class "Default")
      (node (ref "C30") (pin "2") (pinfunction "2_2") (pintype "passive"))
      (node (ref "Q18") (pin "3") (pinfunction "C_3") (pintype "passive"))
      (node (ref "X13") (pin "6") (pinfunction "S_6") (pintype "passive"))
    )
    (net (code "274") (name "{slash}STATUS_LED_R") (class "Default")
      (node (ref "C31") (pin "2") (pinfunction "2_2") (pintype "passive"))
      (node (ref "Q19") (pin "3") (pinfunction "C_3") (pintype "passive"))
      (node (ref "X13") (pin "5") (pinfunction "S_5") (pintype "passive"))
    )
    (net (code "275") (name "{slash}STATUS_LED_Y") (class "Default")
      (node (ref "C29") (pin "2") (pinfunction "2_2") (pintype "passive"))
      (node (ref "Q17") (pin "3") (pinfunction "C_3") (pintype "passive"))
      (node (ref "X13") (pin "7") (pinfunction "S_7") (pintype "passive"))
    )
  )
)
